# RF08ind.net
KiCad netlist of a schematic drawn in EAGLE
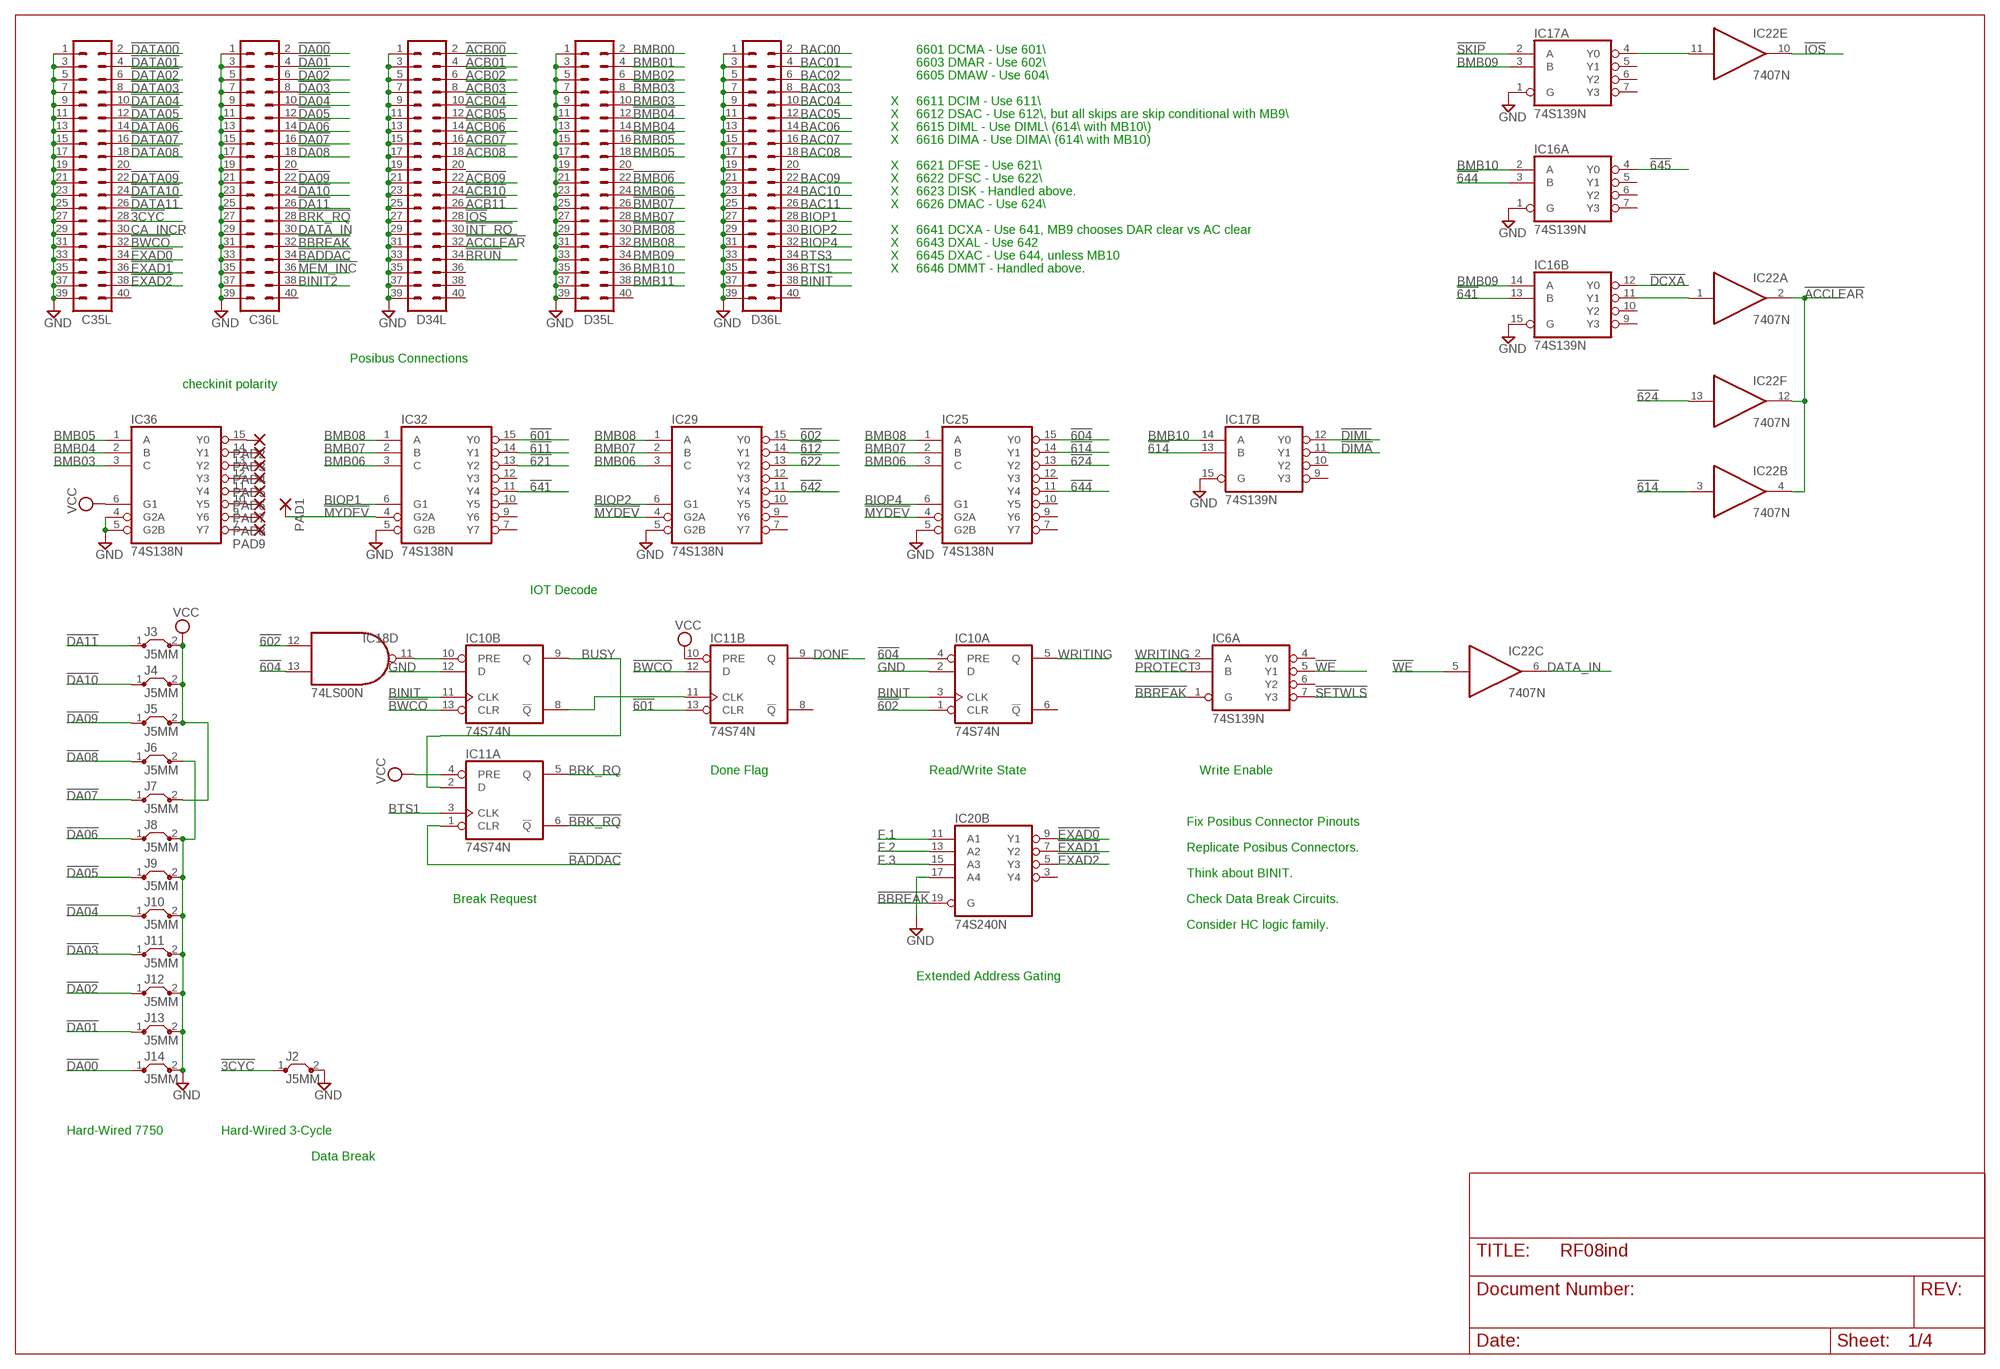
[diagram p0: schematic, sheet 1]
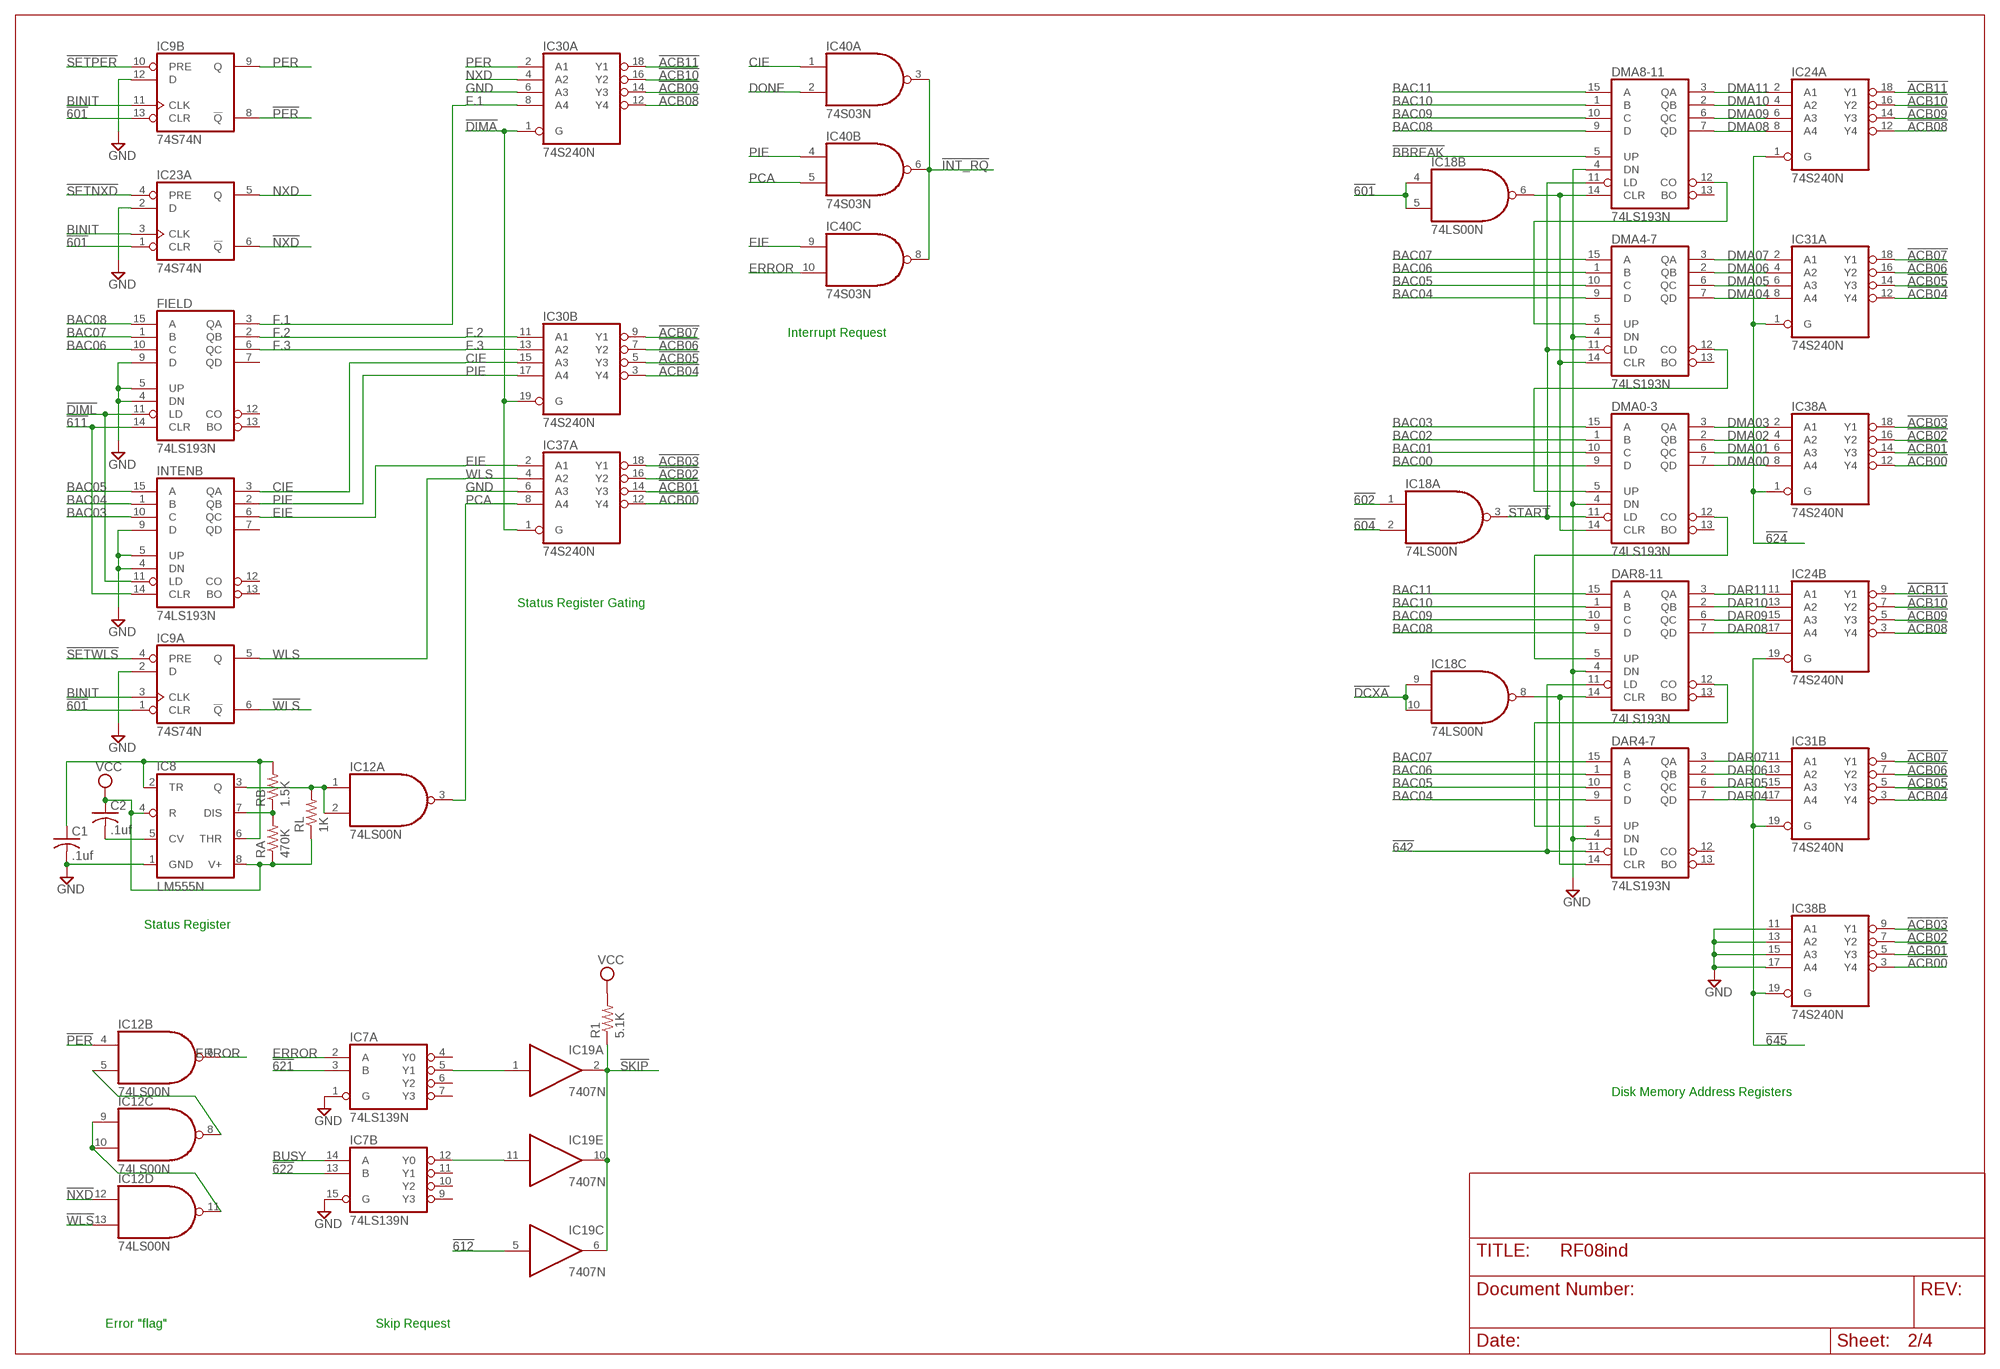
[diagram p1: schematic, sheet 2]
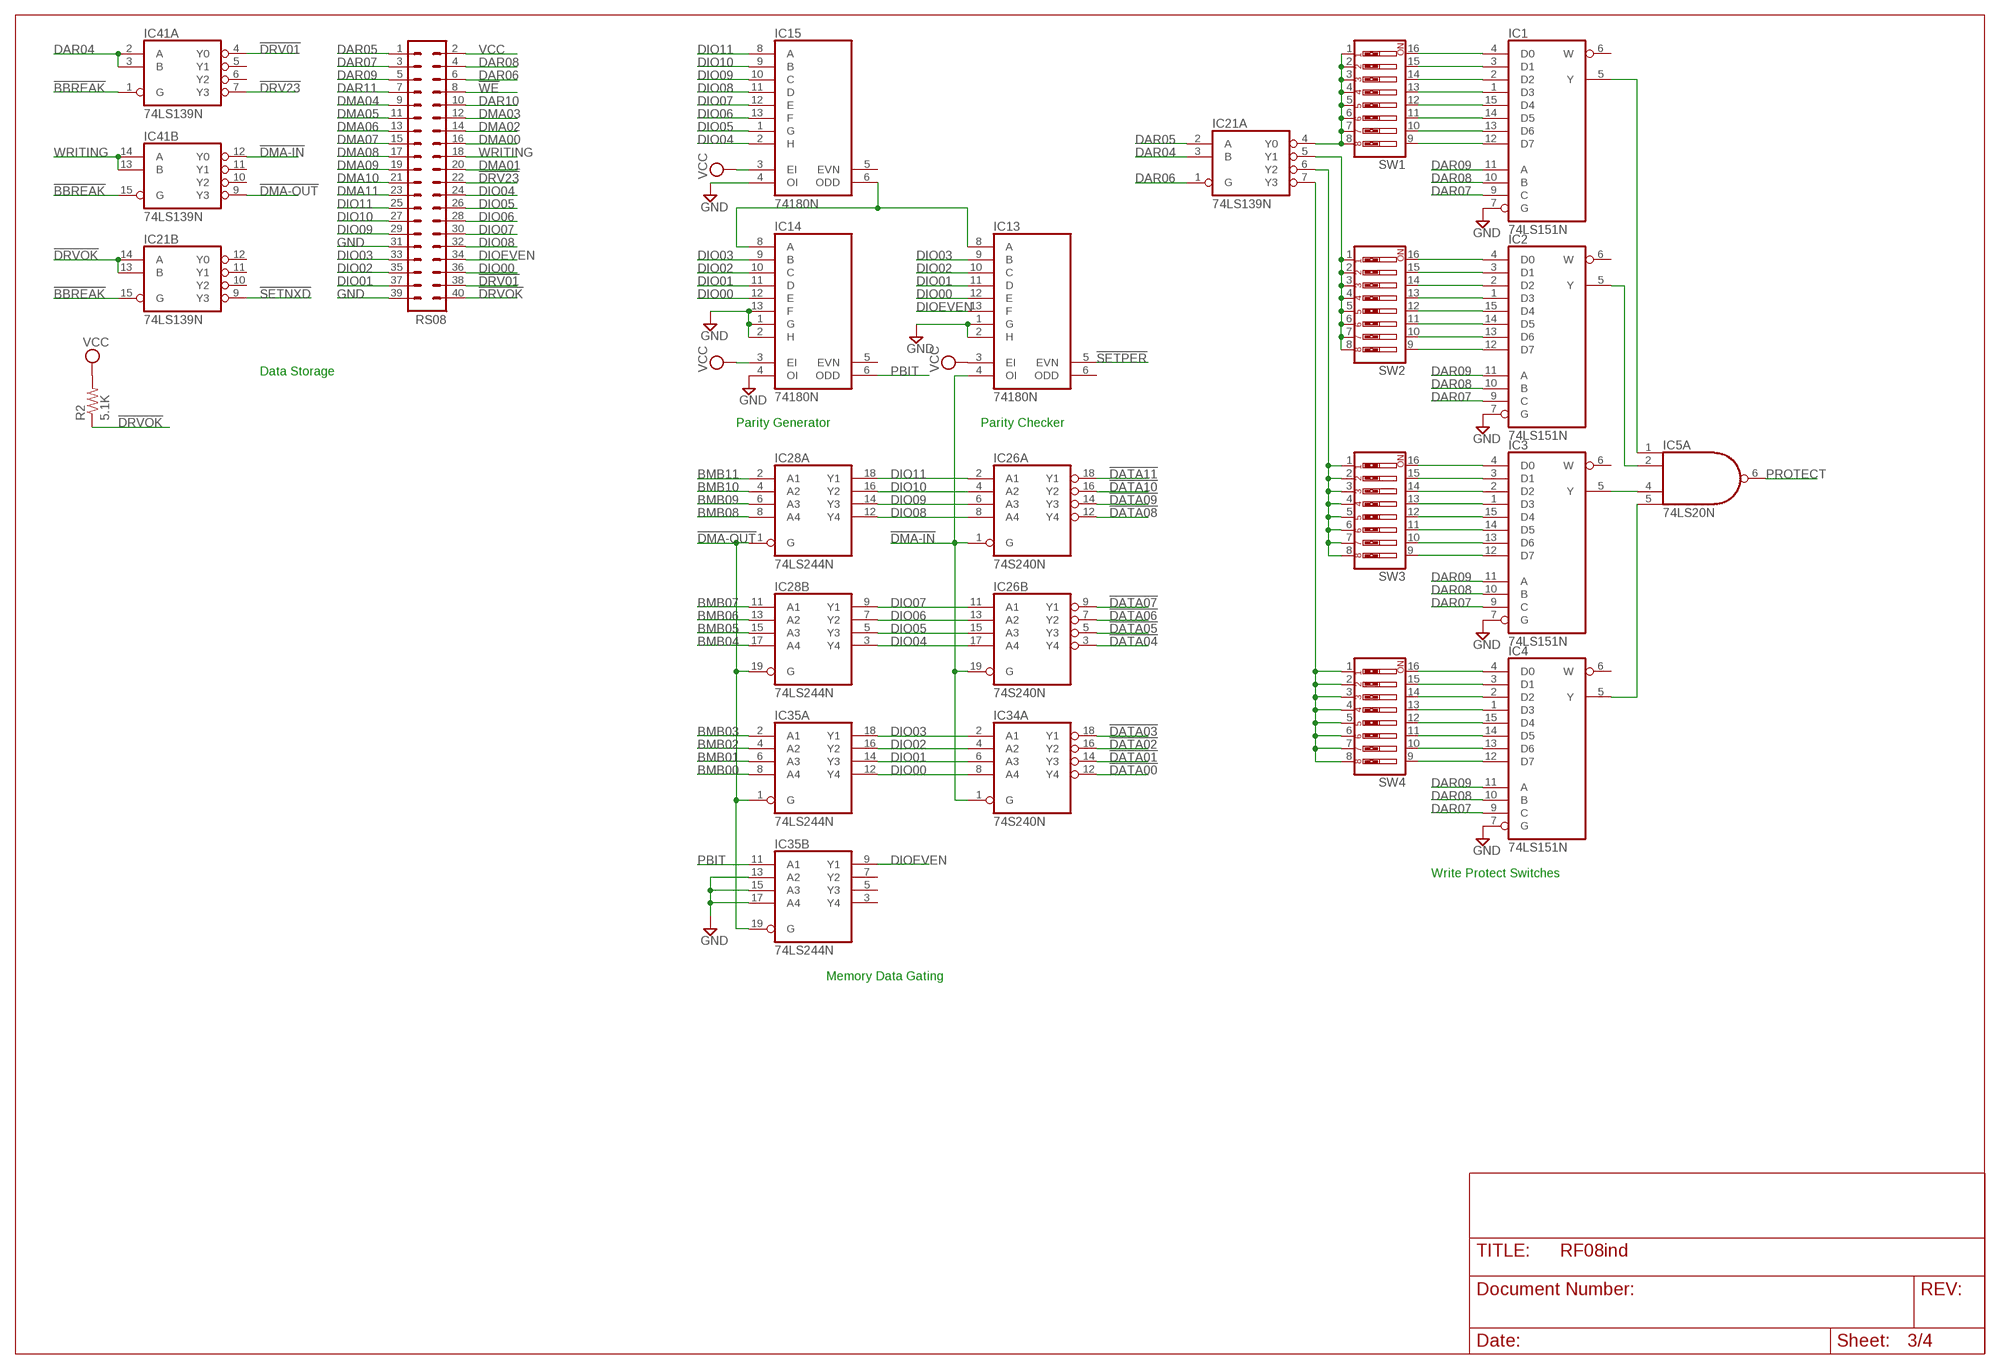
[diagram p2: schematic, sheet 3]
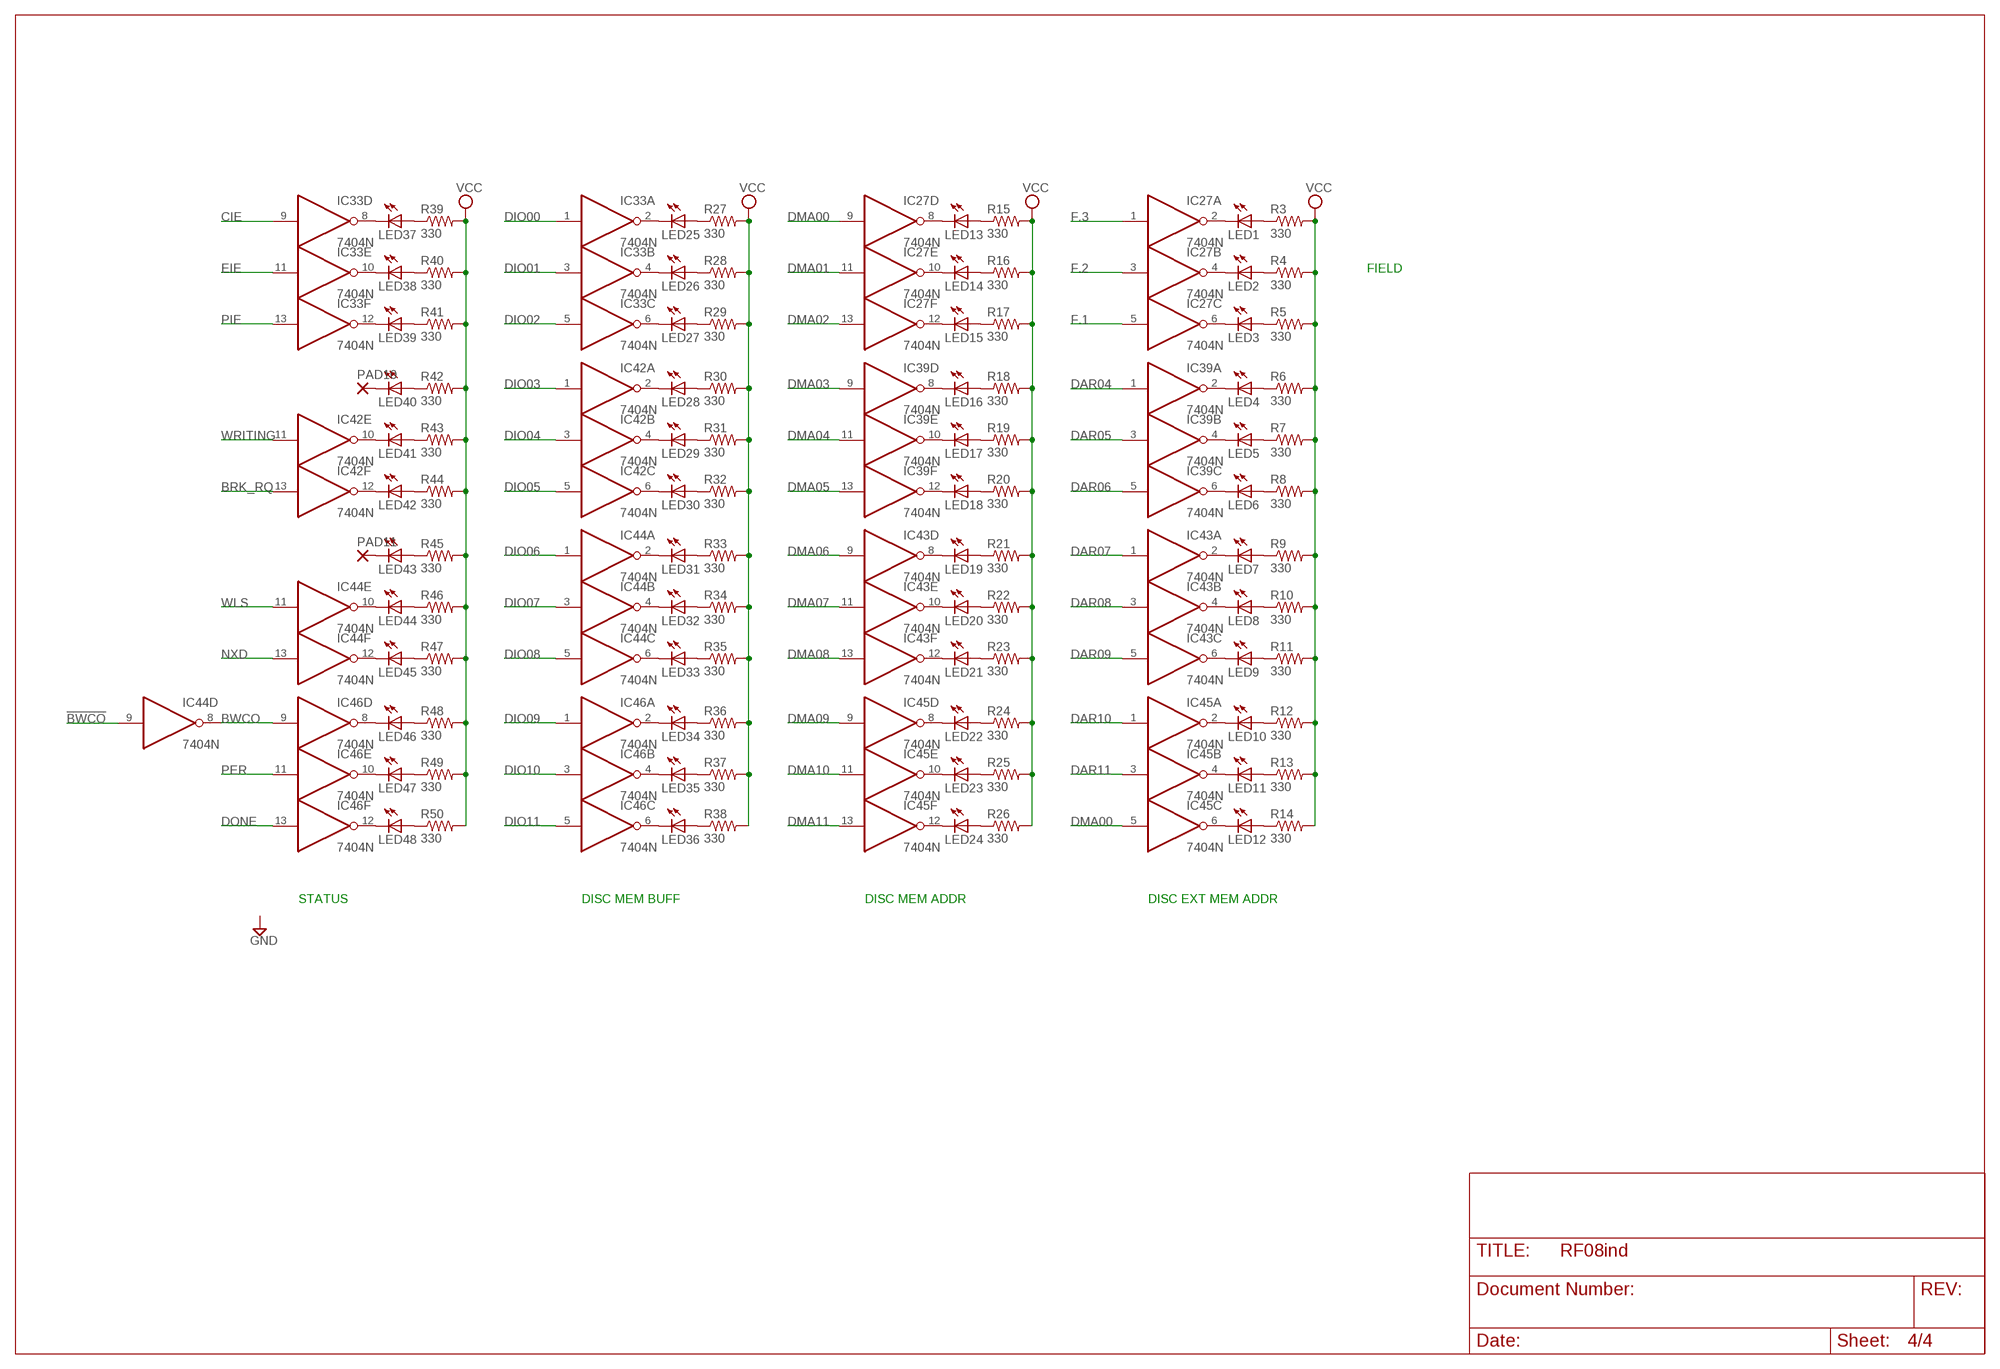
[diagram p3: schematic, sheet 4]

(export (version "E")
  (design (tool "Eeschema 10.0.6"))
  (components
    (comp (ref "IC27")
      (value "7404N")
      (footprint "eagle-import:DIL14")
      (libsource (lib "eagle-import") (part "7404N"))
    )
    (comp (ref "IC33")
      (value "7404N")
      (footprint "eagle-import:DIL14")
      (libsource (lib "eagle-import") (part "7404N"))
    )
    (comp (ref "IC39")
      (value "7404N")
      (footprint "eagle-import:DIL14")
      (libsource (lib "eagle-import") (part "7404N"))
    )
    (comp (ref "IC42")
      (value "7404N")
      (footprint "eagle-import:DIL14")
      (libsource (lib "eagle-import") (part "7404N"))
    )
    (comp (ref "IC43")
      (value "7404N")
      (footprint "eagle-import:DIL14")
      (libsource (lib "eagle-import") (part "7404N"))
    )
    (comp (ref "IC44")
      (value "7404N")
      (footprint "eagle-import:DIL14")
      (libsource (lib "eagle-import") (part "7404N"))
    )
    (comp (ref "IC45")
      (value "7404N")
      (footprint "eagle-import:DIL14")
      (libsource (lib "eagle-import") (part "7404N"))
    )
    (comp (ref "IC46")
      (value "7404N")
      (footprint "eagle-import:DIL14")
      (libsource (lib "eagle-import") (part "7404N"))
    )
    (comp (ref "LED1")
      (value "LED5MM")
      (footprint "eagle-import:LED5MM")
      (libsource (lib "eagle-import") (part "LED5MM"))
    )
    (comp (ref "LED2")
      (value "LED5MM")
      (footprint "eagle-import:LED5MM")
      (libsource (lib "eagle-import") (part "LED5MM"))
    )
    (comp (ref "LED3")
      (value "LED5MM")
      (footprint "eagle-import:LED5MM")
      (libsource (lib "eagle-import") (part "LED5MM"))
    )
    (comp (ref "LED4")
      (value "LED5MM")
      (footprint "eagle-import:LED5MM")
      (libsource (lib "eagle-import") (part "LED5MM"))
    )
    (comp (ref "LED5")
      (value "LED5MM")
      (footprint "eagle-import:LED5MM")
      (libsource (lib "eagle-import") (part "LED5MM"))
    )
    (comp (ref "LED6")
      (value "LED5MM")
      (footprint "eagle-import:LED5MM")
      (libsource (lib "eagle-import") (part "LED5MM"))
    )
    (comp (ref "LED7")
      (value "LED5MM")
      (footprint "eagle-import:LED5MM")
      (libsource (lib "eagle-import") (part "LED5MM"))
    )
    (comp (ref "LED8")
      (value "LED5MM")
      (footprint "eagle-import:LED5MM")
      (libsource (lib "eagle-import") (part "LED5MM"))
    )
    (comp (ref "LED9")
      (value "LED5MM")
      (footprint "eagle-import:LED5MM")
      (libsource (lib "eagle-import") (part "LED5MM"))
    )
    (comp (ref "LED10")
      (value "LED5MM")
      (footprint "eagle-import:LED5MM")
      (libsource (lib "eagle-import") (part "LED5MM"))
    )
    (comp (ref "LED11")
      (value "LED5MM")
      (footprint "eagle-import:LED5MM")
      (libsource (lib "eagle-import") (part "LED5MM"))
    )
    (comp (ref "LED12")
      (value "LED5MM")
      (footprint "eagle-import:LED5MM")
      (libsource (lib "eagle-import") (part "LED5MM"))
    )
    (comp (ref "LED13")
      (value "LED5MM")
      (footprint "eagle-import:LED5MM")
      (libsource (lib "eagle-import") (part "LED5MM"))
    )
    (comp (ref "LED14")
      (value "LED5MM")
      (footprint "eagle-import:LED5MM")
      (libsource (lib "eagle-import") (part "LED5MM"))
    )
    (comp (ref "LED15")
      (value "LED5MM")
      (footprint "eagle-import:LED5MM")
      (libsource (lib "eagle-import") (part "LED5MM"))
    )
    (comp (ref "LED16")
      (value "LED5MM")
      (footprint "eagle-import:LED5MM")
      (libsource (lib "eagle-import") (part "LED5MM"))
    )
    (comp (ref "LED17")
      (value "LED5MM")
      (footprint "eagle-import:LED5MM")
      (libsource (lib "eagle-import") (part "LED5MM"))
    )
    (comp (ref "LED18")
      (value "LED5MM")
      (footprint "eagle-import:LED5MM")
      (libsource (lib "eagle-import") (part "LED5MM"))
    )
    (comp (ref "LED19")
      (value "LED5MM")
      (footprint "eagle-import:LED5MM")
      (libsource (lib "eagle-import") (part "LED5MM"))
    )
    (comp (ref "LED20")
      (value "LED5MM")
      (footprint "eagle-import:LED5MM")
      (libsource (lib "eagle-import") (part "LED5MM"))
    )
    (comp (ref "LED21")
      (value "LED5MM")
      (footprint "eagle-import:LED5MM")
      (libsource (lib "eagle-import") (part "LED5MM"))
    )
    (comp (ref "LED22")
      (value "LED5MM")
      (footprint "eagle-import:LED5MM")
      (libsource (lib "eagle-import") (part "LED5MM"))
    )
    (comp (ref "LED23")
      (value "LED5MM")
      (footprint "eagle-import:LED5MM")
      (libsource (lib "eagle-import") (part "LED5MM"))
    )
    (comp (ref "LED24")
      (value "LED5MM")
      (footprint "eagle-import:LED5MM")
      (libsource (lib "eagle-import") (part "LED5MM"))
    )
    (comp (ref "LED25")
      (value "LED5MM")
      (footprint "eagle-import:LED5MM")
      (libsource (lib "eagle-import") (part "LED5MM"))
    )
    (comp (ref "LED26")
      (value "LED5MM")
      (footprint "eagle-import:LED5MM")
      (libsource (lib "eagle-import") (part "LED5MM"))
    )
    (comp (ref "LED27")
      (value "LED5MM")
      (footprint "eagle-import:LED5MM")
      (libsource (lib "eagle-import") (part "LED5MM"))
    )
    (comp (ref "LED28")
      (value "LED5MM")
      (footprint "eagle-import:LED5MM")
      (libsource (lib "eagle-import") (part "LED5MM"))
    )
    (comp (ref "LED29")
      (value "LED5MM")
      (footprint "eagle-import:LED5MM")
      (libsource (lib "eagle-import") (part "LED5MM"))
    )
    (comp (ref "LED30")
      (value "LED5MM")
      (footprint "eagle-import:LED5MM")
      (libsource (lib "eagle-import") (part "LED5MM"))
    )
    (comp (ref "LED31")
      (value "LED5MM")
      (footprint "eagle-import:LED5MM")
      (libsource (lib "eagle-import") (part "LED5MM"))
    )
    (comp (ref "LED32")
      (value "LED5MM")
      (footprint "eagle-import:LED5MM")
      (libsource (lib "eagle-import") (part "LED5MM"))
    )
    (comp (ref "LED33")
      (value "LED5MM")
      (footprint "eagle-import:LED5MM")
      (libsource (lib "eagle-import") (part "LED5MM"))
    )
    (comp (ref "LED34")
      (value "LED5MM")
      (footprint "eagle-import:LED5MM")
      (libsource (lib "eagle-import") (part "LED5MM"))
    )
    (comp (ref "LED35")
      (value "LED5MM")
      (footprint "eagle-import:LED5MM")
      (libsource (lib "eagle-import") (part "LED5MM"))
    )
    (comp (ref "LED36")
      (value "LED5MM")
      (footprint "eagle-import:LED5MM")
      (libsource (lib "eagle-import") (part "LED5MM"))
    )
    (comp (ref "LED37")
      (value "LED5MM")
      (footprint "eagle-import:LED5MM")
      (libsource (lib "eagle-import") (part "LED5MM"))
    )
    (comp (ref "LED38")
      (value "LED5MM")
      (footprint "eagle-import:LED5MM")
      (libsource (lib "eagle-import") (part "LED5MM"))
    )
    (comp (ref "LED39")
      (value "LED5MM")
      (footprint "eagle-import:LED5MM")
      (libsource (lib "eagle-import") (part "LED5MM"))
    )
    (comp (ref "LED40")
      (value "LED5MM")
      (footprint "eagle-import:LED5MM")
      (libsource (lib "eagle-import") (part "LED5MM"))
    )
    (comp (ref "LED41")
      (value "LED5MM")
      (footprint "eagle-import:LED5MM")
      (libsource (lib "eagle-import") (part "LED5MM"))
    )
    (comp (ref "LED42")
      (value "LED5MM")
      (footprint "eagle-import:LED5MM")
      (libsource (lib "eagle-import") (part "LED5MM"))
    )
    (comp (ref "LED43")
      (value "LED5MM")
      (footprint "eagle-import:LED5MM")
      (libsource (lib "eagle-import") (part "LED5MM"))
    )
    (comp (ref "LED44")
      (value "LED5MM")
      (footprint "eagle-import:LED5MM")
      (libsource (lib "eagle-import") (part "LED5MM"))
    )
    (comp (ref "LED45")
      (value "LED5MM")
      (footprint "eagle-import:LED5MM")
      (libsource (lib "eagle-import") (part "LED5MM"))
    )
    (comp (ref "LED46")
      (value "LED5MM")
      (footprint "eagle-import:LED5MM")
      (libsource (lib "eagle-import") (part "LED5MM"))
    )
    (comp (ref "LED47")
      (value "LED5MM")
      (footprint "eagle-import:LED5MM")
      (libsource (lib "eagle-import") (part "LED5MM"))
    )
    (comp (ref "LED48")
      (value "LED5MM")
      (footprint "eagle-import:LED5MM")
      (libsource (lib "eagle-import") (part "LED5MM"))
    )
    (comp (ref "PAD10")
      (value "1,6/0,8")
      (footprint "eagle-import:1,6_0,8")
      (libsource (lib "eagle-import") (part "1,6/0,8"))
    )
    (comp (ref "PAD11")
      (value "1,6/0,8")
      (footprint "eagle-import:1,6_0,8")
      (libsource (lib "eagle-import") (part "1,6/0,8"))
    )
    (comp (ref "R3")
      (value "330")
      (footprint "eagle-import:0207_10")
      (libsource (lib "eagle-import") (part "R-US_0207/10"))
    )
    (comp (ref "R4")
      (value "330")
      (footprint "eagle-import:0207_10")
      (libsource (lib "eagle-import") (part "R-US_0207/10"))
    )
    (comp (ref "R5")
      (value "330")
      (footprint "eagle-import:0207_10")
      (libsource (lib "eagle-import") (part "R-US_0207/10"))
    )
    (comp (ref "R6")
      (value "330")
      (footprint "eagle-import:0207_10")
      (libsource (lib "eagle-import") (part "R-US_0207/10"))
    )
    (comp (ref "R7")
      (value "330")
      (footprint "eagle-import:0207_10")
      (libsource (lib "eagle-import") (part "R-US_0207/10"))
    )
    (comp (ref "R8")
      (value "330")
      (footprint "eagle-import:0207_10")
      (libsource (lib "eagle-import") (part "R-US_0207/10"))
    )
    (comp (ref "R9")
      (value "330")
      (footprint "eagle-import:0207_10")
      (libsource (lib "eagle-import") (part "R-US_0207/10"))
    )
    (comp (ref "R10")
      (value "330")
      (footprint "eagle-import:0207_10")
      (libsource (lib "eagle-import") (part "R-US_0207/10"))
    )
    (comp (ref "R11")
      (value "330")
      (footprint "eagle-import:0207_10")
      (libsource (lib "eagle-import") (part "R-US_0207/10"))
    )
    (comp (ref "R12")
      (value "330")
      (footprint "eagle-import:0207_10")
      (libsource (lib "eagle-import") (part "R-US_0207/10"))
    )
    (comp (ref "R13")
      (value "330")
      (footprint "eagle-import:0207_10")
      (libsource (lib "eagle-import") (part "R-US_0207/10"))
    )
    (comp (ref "R14")
      (value "330")
      (footprint "eagle-import:0207_10")
      (libsource (lib "eagle-import") (part "R-US_0207/10"))
    )
    (comp (ref "R15")
      (value "330")
      (footprint "eagle-import:0207_10")
      (libsource (lib "eagle-import") (part "R-US_0207/10"))
    )
    (comp (ref "R16")
      (value "330")
      (footprint "eagle-import:0207_10")
      (libsource (lib "eagle-import") (part "R-US_0207/10"))
    )
    (comp (ref "R17")
      (value "330")
      (footprint "eagle-import:0207_10")
      (libsource (lib "eagle-import") (part "R-US_0207/10"))
    )
    (comp (ref "R18")
      (value "330")
      (footprint "eagle-import:0207_10")
      (libsource (lib "eagle-import") (part "R-US_0207/10"))
    )
    (comp (ref "R19")
      (value "330")
      (footprint "eagle-import:0207_10")
      (libsource (lib "eagle-import") (part "R-US_0207/10"))
    )
    (comp (ref "R20")
      (value "330")
      (footprint "eagle-import:0207_10")
      (libsource (lib "eagle-import") (part "R-US_0207/10"))
    )
    (comp (ref "R21")
      (value "330")
      (footprint "eagle-import:0207_10")
      (libsource (lib "eagle-import") (part "R-US_0207/10"))
    )
    (comp (ref "R22")
      (value "330")
      (footprint "eagle-import:0207_10")
      (libsource (lib "eagle-import") (part "R-US_0207/10"))
    )
    (comp (ref "R23")
      (value "330")
      (footprint "eagle-import:0207_10")
      (libsource (lib "eagle-import") (part "R-US_0207/10"))
    )
    (comp (ref "R24")
      (value "330")
      (footprint "eagle-import:0207_10")
      (libsource (lib "eagle-import") (part "R-US_0207/10"))
    )
    (comp (ref "R25")
      (value "330")
      (footprint "eagle-import:0207_10")
      (libsource (lib "eagle-import") (part "R-US_0207/10"))
    )
    (comp (ref "R26")
      (value "330")
      (footprint "eagle-import:0207_10")
      (libsource (lib "eagle-import") (part "R-US_0207/10"))
    )
    (comp (ref "R27")
      (value "330")
      (footprint "eagle-import:0207_10")
      (libsource (lib "eagle-import") (part "R-US_0207/10"))
    )
    (comp (ref "R28")
      (value "330")
      (footprint "eagle-import:0207_10")
      (libsource (lib "eagle-import") (part "R-US_0207/10"))
    )
    (comp (ref "R29")
      (value "330")
      (footprint "eagle-import:0207_10")
      (libsource (lib "eagle-import") (part "R-US_0207/10"))
    )
    (comp (ref "R30")
      (value "330")
      (footprint "eagle-import:0207_10")
      (libsource (lib "eagle-import") (part "R-US_0207/10"))
    )
    (comp (ref "R31")
      (value "330")
      (footprint "eagle-import:0207_10")
      (libsource (lib "eagle-import") (part "R-US_0207/10"))
    )
    (comp (ref "R32")
      (value "330")
      (footprint "eagle-import:0207_10")
      (libsource (lib "eagle-import") (part "R-US_0207/10"))
    )
    (comp (ref "R33")
      (value "330")
      (footprint "eagle-import:0207_10")
      (libsource (lib "eagle-import") (part "R-US_0207/10"))
    )
    (comp (ref "R34")
      (value "330")
      (footprint "eagle-import:0207_10")
      (libsource (lib "eagle-import") (part "R-US_0207/10"))
    )
    (comp (ref "R35")
      (value "330")
      (footprint "eagle-import:0207_10")
      (libsource (lib "eagle-import") (part "R-US_0207/10"))
    )
    (comp (ref "R36")
      (value "330")
      (footprint "eagle-import:0207_10")
      (libsource (lib "eagle-import") (part "R-US_0207/10"))
    )
    (comp (ref "R37")
      (value "330")
      (footprint "eagle-import:0207_10")
      (libsource (lib "eagle-import") (part "R-US_0207/10"))
    )
    (comp (ref "R38")
      (value "330")
      (footprint "eagle-import:0207_10")
      (libsource (lib "eagle-import") (part "R-US_0207/10"))
    )
    (comp (ref "R39")
      (value "330")
      (footprint "eagle-import:0207_10")
      (libsource (lib "eagle-import") (part "R-US_0207/10"))
    )
    (comp (ref "R40")
      (value "330")
      (footprint "eagle-import:0207_10")
      (libsource (lib "eagle-import") (part "R-US_0207/10"))
    )
    (comp (ref "R41")
      (value "330")
      (footprint "eagle-import:0207_10")
      (libsource (lib "eagle-import") (part "R-US_0207/10"))
    )
    (comp (ref "R42")
      (value "330")
      (footprint "eagle-import:0207_10")
      (libsource (lib "eagle-import") (part "R-US_0207/10"))
    )
    (comp (ref "R43")
      (value "330")
      (footprint "eagle-import:0207_10")
      (libsource (lib "eagle-import") (part "R-US_0207/10"))
    )
    (comp (ref "R44")
      (value "330")
      (footprint "eagle-import:0207_10")
      (libsource (lib "eagle-import") (part "R-US_0207/10"))
    )
    (comp (ref "R45")
      (value "330")
      (footprint "eagle-import:0207_10")
      (libsource (lib "eagle-import") (part "R-US_0207/10"))
    )
    (comp (ref "R46")
      (value "330")
      (footprint "eagle-import:0207_10")
      (libsource (lib "eagle-import") (part "R-US_0207/10"))
    )
    (comp (ref "R47")
      (value "330")
      (footprint "eagle-import:0207_10")
      (libsource (lib "eagle-import") (part "R-US_0207/10"))
    )
    (comp (ref "R48")
      (value "330")
      (footprint "eagle-import:0207_10")
      (libsource (lib "eagle-import") (part "R-US_0207/10"))
    )
    (comp (ref "R49")
      (value "330")
      (footprint "eagle-import:0207_10")
      (libsource (lib "eagle-import") (part "R-US_0207/10"))
    )
    (comp (ref "R50")
      (value "330")
      (footprint "eagle-import:0207_10")
      (libsource (lib "eagle-import") (part "R-US_0207/10"))
    )
    (comp (ref "IC1")
      (value "74LS151N")
      (footprint "eagle-import:DIL16")
      (libsource (lib "eagle-import") (part "74151NLS"))
    )
    (comp (ref "IC2")
      (value "74LS151N")
      (footprint "eagle-import:DIL16")
      (libsource (lib "eagle-import") (part "74151NLS"))
    )
    (comp (ref "IC3")
      (value "74LS151N")
      (footprint "eagle-import:DIL16")
      (libsource (lib "eagle-import") (part "74151NLS"))
    )
    (comp (ref "IC4")
      (value "74LS151N")
      (footprint "eagle-import:DIL16")
      (libsource (lib "eagle-import") (part "74151NLS"))
    )
    (comp (ref "IC5")
      (value "74LS20N")
      (footprint "eagle-import:DIL14")
      (libsource (lib "eagle-import") (part "7420NLS"))
    )
    (comp (ref "IC13")
      (value "74180N")
      (footprint "eagle-import:DIL14")
      (libsource (lib "eagle-import") (part "74180N"))
    )
    (comp (ref "IC14")
      (value "74180N")
      (footprint "eagle-import:DIL14")
      (libsource (lib "eagle-import") (part "74180N"))
    )
    (comp (ref "IC15")
      (value "74180N")
      (footprint "eagle-import:DIL14")
      (libsource (lib "eagle-import") (part "74180N"))
    )
    (comp (ref "IC21")
      (value "74LS139N")
      (footprint "eagle-import:DIL16")
      (libsource (lib "eagle-import") (part "74139NLS"))
    )
    (comp (ref "IC26")
      (value "74S240N")
      (footprint "eagle-import:DIL20")
      (libsource (lib "eagle-import") (part "74240NS"))
    )
    (comp (ref "IC28")
      (value "74LS244N")
      (footprint "eagle-import:DIL20")
      (libsource (lib "eagle-import") (part "74244NLS"))
    )
    (comp (ref "IC34")
      (value "74S240N")
      (footprint "eagle-import:DIL20")
      (libsource (lib "eagle-import") (part "74240NS"))
    )
    (comp (ref "IC35")
      (value "74LS244N")
      (footprint "eagle-import:DIL20")
      (libsource (lib "eagle-import") (part "74244NLS"))
    )
    (comp (ref "IC41")
      (value "74LS139N")
      (footprint "eagle-import:DIL16")
      (libsource (lib "eagle-import") (part "74139NLS"))
    )
    (comp (ref "R2")
      (value "5.1K")
      (footprint "eagle-import:0207_10")
      (libsource (lib "eagle-import") (part "R-US_0207/10"))
    )
    (comp (ref "RS08")
      (value "MA20-2")
      (footprint "eagle-import:MA20-2")
      (libsource (lib "eagle-import") (part "MA20-2"))
    )
    (comp (ref "SW1")
      (value "SW_DIP-8")
      (footprint "eagle-import:EDG-08")
      (libsource (lib "eagle-import") (part "SW_DIP-8"))
    )
    (comp (ref "SW2")
      (value "SW_DIP-8")
      (footprint "eagle-import:EDG-08")
      (libsource (lib "eagle-import") (part "SW_DIP-8"))
    )
    (comp (ref "SW3")
      (value "SW_DIP-8")
      (footprint "eagle-import:EDG-08")
      (libsource (lib "eagle-import") (part "SW_DIP-8"))
    )
    (comp (ref "SW4")
      (value "SW_DIP-8")
      (footprint "eagle-import:EDG-08")
      (libsource (lib "eagle-import") (part "SW_DIP-8"))
    )
    (comp (ref "C35L")
      (value "MA20-2")
      (footprint "eagle-import:MA20-2")
      (libsource (lib "eagle-import") (part "MA20-2"))
    )
    (comp (ref "C36L")
      (value "MA20-2")
      (footprint "eagle-import:MA20-2")
      (libsource (lib "eagle-import") (part "MA20-2"))
    )
    (comp (ref "D34L")
      (value "MA20-2")
      (footprint "eagle-import:MA20-2")
      (libsource (lib "eagle-import") (part "MA20-2"))
    )
    (comp (ref "D35L")
      (value "MA20-2")
      (footprint "eagle-import:MA20-2")
      (libsource (lib "eagle-import") (part "MA20-2"))
    )
    (comp (ref "D36L")
      (value "MA20-2")
      (footprint "eagle-import:MA20-2")
      (libsource (lib "eagle-import") (part "MA20-2"))
    )
    (comp (ref "IC6")
      (value "74S139N")
      (footprint "eagle-import:DIL16")
      (libsource (lib "eagle-import") (part "74139NS"))
    )
    (comp (ref "IC10")
      (value "74S74N")
      (footprint "eagle-import:DIL14")
      (libsource (lib "eagle-import") (part "7474NS"))
    )
    (comp (ref "IC11")
      (value "74S74N")
      (footprint "eagle-import:DIL14")
      (libsource (lib "eagle-import") (part "7474NS"))
    )
    (comp (ref "IC16")
      (value "74S139N")
      (footprint "eagle-import:DIL16")
      (libsource (lib "eagle-import") (part "74139NS"))
    )
    (comp (ref "IC17")
      (value "74S139N")
      (footprint "eagle-import:DIL16")
      (libsource (lib "eagle-import") (part "74139NS"))
    )
    (comp (ref "IC18")
      (value "74LS00N")
      (footprint "eagle-import:DIL14")
      (libsource (lib "eagle-import") (part "7400NLS"))
    )
    (comp (ref "IC20")
      (value "74S240N")
      (footprint "eagle-import:DIL20")
      (libsource (lib "eagle-import") (part "74240NS"))
    )
    (comp (ref "IC22")
      (value "7407N")
      (footprint "eagle-import:DIL14")
      (libsource (lib "eagle-import") (part "7407N"))
    )
    (comp (ref "IC25")
      (value "74S138N")
      (footprint "eagle-import:DIL16")
      (libsource (lib "eagle-import") (part "74138NS"))
    )
    (comp (ref "IC29")
      (value "74S138N")
      (footprint "eagle-import:DIL16")
      (libsource (lib "eagle-import") (part "74138NS"))
    )
    (comp (ref "IC32")
      (value "74S138N")
      (footprint "eagle-import:DIL16")
      (libsource (lib "eagle-import") (part "74138NS"))
    )
    (comp (ref "IC36")
      (value "74S138N")
      (footprint "eagle-import:DIL16")
      (libsource (lib "eagle-import") (part "74138NS"))
    )
    (comp (ref "J2")
      (value "J5MM")
      (footprint "eagle-import:05")
      (libsource (lib "eagle-import") (part "J5MM"))
    )
    (comp (ref "J3")
      (value "J5MM")
      (footprint "eagle-import:05")
      (libsource (lib "eagle-import") (part "J5MM"))
    )
    (comp (ref "J4")
      (value "J5MM")
      (footprint "eagle-import:05")
      (libsource (lib "eagle-import") (part "J5MM"))
    )
    (comp (ref "J5")
      (value "J5MM")
      (footprint "eagle-import:05")
      (libsource (lib "eagle-import") (part "J5MM"))
    )
    (comp (ref "J6")
      (value "J5MM")
      (footprint "eagle-import:05")
      (libsource (lib "eagle-import") (part "J5MM"))
    )
    (comp (ref "J7")
      (value "J5MM")
      (footprint "eagle-import:05")
      (libsource (lib "eagle-import") (part "J5MM"))
    )
    (comp (ref "J8")
      (value "J5MM")
      (footprint "eagle-import:05")
      (libsource (lib "eagle-import") (part "J5MM"))
    )
    (comp (ref "J9")
      (value "J5MM")
      (footprint "eagle-import:05")
      (libsource (lib "eagle-import") (part "J5MM"))
    )
    (comp (ref "J10")
      (value "J5MM")
      (footprint "eagle-import:05")
      (libsource (lib "eagle-import") (part "J5MM"))
    )
    (comp (ref "J11")
      (value "J5MM")
      (footprint "eagle-import:05")
      (libsource (lib "eagle-import") (part "J5MM"))
    )
    (comp (ref "J12")
      (value "J5MM")
      (footprint "eagle-import:05")
      (libsource (lib "eagle-import") (part "J5MM"))
    )
    (comp (ref "J13")
      (value "J5MM")
      (footprint "eagle-import:05")
      (libsource (lib "eagle-import") (part "J5MM"))
    )
    (comp (ref "J14")
      (value "J5MM")
      (footprint "eagle-import:05")
      (libsource (lib "eagle-import") (part "J5MM"))
    )
    (comp (ref "PAD1")
      (value "1,6/0,8")
      (footprint "eagle-import:1,6_0,8")
      (libsource (lib "eagle-import") (part "1,6/0,8"))
    )
    (comp (ref "PAD2")
      (value "1,6/0,8")
      (footprint "eagle-import:1,6_0,8")
      (libsource (lib "eagle-import") (part "1,6/0,8"))
    )
    (comp (ref "PAD3")
      (value "1,6/0,8")
      (footprint "eagle-import:1,6_0,8")
      (libsource (lib "eagle-import") (part "1,6/0,8"))
    )
    (comp (ref "PAD4")
      (value "1,6/0,8")
      (footprint "eagle-import:1,6_0,8")
      (libsource (lib "eagle-import") (part "1,6/0,8"))
    )
    (comp (ref "PAD5")
      (value "1,6/0,8")
      (footprint "eagle-import:1,6_0,8")
      (libsource (lib "eagle-import") (part "1,6/0,8"))
    )
    (comp (ref "PAD6")
      (value "1,6/0,8")
      (footprint "eagle-import:1,6_0,8")
      (libsource (lib "eagle-import") (part "1,6/0,8"))
    )
    (comp (ref "PAD7")
      (value "1,6/0,8")
      (footprint "eagle-import:1,6_0,8")
      (libsource (lib "eagle-import") (part "1,6/0,8"))
    )
    (comp (ref "PAD8")
      (value "1,6/0,8")
      (footprint "eagle-import:1,6_0,8")
      (libsource (lib "eagle-import") (part "1,6/0,8"))
    )
    (comp (ref "PAD9")
      (value "1,6/0,8")
      (footprint "eagle-import:1,6_0,8")
      (libsource (lib "eagle-import") (part "1,6/0,8"))
    )
    (comp (ref "C1")
      (value ".1uf")
      (footprint "eagle-import:C050-025X075")
      (libsource (lib "eagle-import") (part "C-US050-025X075"))
    )
    (comp (ref "C2")
      (value ".1uf")
      (footprint "eagle-import:C050-025X075")
      (libsource (lib "eagle-import") (part "C-US050-025X075"))
    )
    (comp (ref "DAR4-7")
      (value "74LS193N")
      (footprint "eagle-import:DIL16")
      (libsource (lib "eagle-import") (part "74192NLS"))
    )
    (comp (ref "DAR8-11")
      (value "74LS193N")
      (footprint "eagle-import:DIL16")
      (libsource (lib "eagle-import") (part "74192NLS"))
    )
    (comp (ref "DMA0-3")
      (value "74LS193N")
      (footprint "eagle-import:DIL16")
      (libsource (lib "eagle-import") (part "74192NLS"))
    )
    (comp (ref "DMA4-7")
      (value "74LS193N")
      (footprint "eagle-import:DIL16")
      (libsource (lib "eagle-import") (part "74192NLS"))
    )
    (comp (ref "DMA8-11")
      (value "74LS193N")
      (footprint "eagle-import:DIL16")
      (libsource (lib "eagle-import") (part "74192NLS"))
    )
    (comp (ref "FIELD")
      (value "74LS193N")
      (footprint "eagle-import:DIL16")
      (libsource (lib "eagle-import") (part "74192NLS"))
    )
    (comp (ref "IC7")
      (value "74LS139N")
      (footprint "eagle-import:DIL16")
      (libsource (lib "eagle-import") (part "74139NLS"))
    )
    (comp (ref "IC8")
      (value "LM555N")
      (footprint "eagle-import:DIL08")
      (libsource (lib "eagle-import") (part "555NLM"))
    )
    (comp (ref "IC9")
      (value "74S74N")
      (footprint "eagle-import:DIL14")
      (libsource (lib "eagle-import") (part "7474NS"))
    )
    (comp (ref "IC12")
      (value "74LS00N")
      (footprint "eagle-import:DIL14")
      (libsource (lib "eagle-import") (part "7400NLS"))
    )
    (comp (ref "IC19")
      (value "7407N")
      (footprint "eagle-import:DIL14")
      (libsource (lib "eagle-import") (part "7407N"))
    )
    (comp (ref "IC23")
      (value "74S74N")
      (footprint "eagle-import:DIL14")
      (libsource (lib "eagle-import") (part "7474NS"))
    )
    (comp (ref "IC24")
      (value "74S240N")
      (footprint "eagle-import:DIL20")
      (libsource (lib "eagle-import") (part "74240NS"))
    )
    (comp (ref "IC30")
      (value "74S240N")
      (footprint "eagle-import:DIL20")
      (libsource (lib "eagle-import") (part "74240NS"))
    )
    (comp (ref "IC31")
      (value "74S240N")
      (footprint "eagle-import:DIL20")
      (libsource (lib "eagle-import") (part "74240NS"))
    )
    (comp (ref "IC37")
      (value "74S240N")
      (footprint "eagle-import:DIL20")
      (libsource (lib "eagle-import") (part "74240NS"))
    )
    (comp (ref "IC38")
      (value "74S240N")
      (footprint "eagle-import:DIL20")
      (libsource (lib "eagle-import") (part "74240NS"))
    )
    (comp (ref "IC40")
      (value "74S03N")
      (footprint "eagle-import:DIL14")
      (libsource (lib "eagle-import") (part "7403NS"))
    )
    (comp (ref "INTENB")
      (value "74LS193N")
      (footprint "eagle-import:DIL16")
      (libsource (lib "eagle-import") (part "74192NLS"))
    )
    (comp (ref "R1")
      (value "5.1K")
      (footprint "eagle-import:0207_10")
      (libsource (lib "eagle-import") (part "R-US_0207/10"))
    )
    (comp (ref "RA")
      (value "470K")
      (footprint "eagle-import:0207_10")
      (libsource (lib "eagle-import") (part "R-US_0207/10"))
    )
    (comp (ref "RB")
      (value "1.5K")
      (footprint "eagle-import:0207_10")
      (libsource (lib "eagle-import") (part "R-US_0207/10"))
    )
    (comp (ref "RL")
      (value "1K")
      (footprint "eagle-import:0207_10")
      (libsource (lib "eagle-import") (part "R-US_0207/10"))
    )
  )
  (nets
    (net (code "1") (name "BAC00") (class "Default")
      (node (ref "D36L") (pin "2") (pinfunction "2_2") (pintype "passive"))
      (node (ref "DMA0-3") (pin "9") (pinfunction "D_9") (pintype "input"))
    )
    (net (code "2") (name "BAC01") (class "Default")
      (node (ref "D36L") (pin "4") (pinfunction "4_4") (pintype "passive"))
      (node (ref "DMA0-3") (pin "10") (pinfunction "C_10") (pintype "input"))
    )
    (net (code "3") (name "BAC02") (class "Default")
      (node (ref "D36L") (pin "6") (pinfunction "6_6") (pintype "passive"))
      (node (ref "DMA0-3") (pin "1") (pinfunction "B_1") (pintype "input"))
    )
    (net (code "4") (name "BAC03") (class "Default")
      (node (ref "D36L") (pin "8") (pinfunction "8_8") (pintype "passive"))
      (node (ref "DMA0-3") (pin "15") (pinfunction "A_15") (pintype "input"))
      (node (ref "INTENB") (pin "10") (pinfunction "C_10") (pintype "input"))
    )
    (net (code "5") (name "BAC04") (class "Default")
      (node (ref "D36L") (pin "10") (pinfunction "10_10") (pintype "passive"))
      (node (ref "DAR4-7") (pin "9") (pinfunction "D_9") (pintype "input"))
      (node (ref "DMA4-7") (pin "9") (pinfunction "D_9") (pintype "input"))
      (node (ref "INTENB") (pin "1") (pinfunction "B_1") (pintype "input"))
    )
    (net (code "6") (name "BAC05") (class "Default")
      (node (ref "D36L") (pin "12") (pinfunction "12_12") (pintype "passive"))
      (node (ref "DAR4-7") (pin "10") (pinfunction "C_10") (pintype "input"))
      (node (ref "DMA4-7") (pin "10") (pinfunction "C_10") (pintype "input"))
      (node (ref "INTENB") (pin "15") (pinfunction "A_15") (pintype "input"))
    )
    (net (code "7") (name "BAC06") (class "Default")
      (node (ref "D36L") (pin "14") (pinfunction "14_14") (pintype "passive"))
      (node (ref "DAR4-7") (pin "1") (pinfunction "B_1") (pintype "input"))
      (node (ref "DMA4-7") (pin "1") (pinfunction "B_1") (pintype "input"))
      (node (ref "FIELD") (pin "10") (pinfunction "C_10") (pintype "input"))
    )
    (net (code "8") (name "BAC07") (class "Default")
      (node (ref "D36L") (pin "16") (pinfunction "16_16") (pintype "passive"))
      (node (ref "DAR4-7") (pin "15") (pinfunction "A_15") (pintype "input"))
      (node (ref "DMA4-7") (pin "15") (pinfunction "A_15") (pintype "input"))
      (node (ref "FIELD") (pin "1") (pinfunction "B_1") (pintype "input"))
    )
    (net (code "9") (name "BAC08") (class "Default")
      (node (ref "D36L") (pin "18") (pinfunction "18_18") (pintype "passive"))
      (node (ref "DAR8-11") (pin "9") (pinfunction "D_9") (pintype "input"))
      (node (ref "DMA8-11") (pin "9") (pinfunction "D_9") (pintype "input"))
      (node (ref "FIELD") (pin "15") (pinfunction "A_15") (pintype "input"))
    )
    (net (code "10") (name "BAC09") (class "Default")
      (node (ref "D36L") (pin "22") (pinfunction "22_22") (pintype "passive"))
      (node (ref "DAR8-11") (pin "10") (pinfunction "C_10") (pintype "input"))
      (node (ref "DMA8-11") (pin "10") (pinfunction "C_10") (pintype "input"))
    )
    (net (code "11") (name "BAC10") (class "Default")
      (node (ref "D36L") (pin "24") (pinfunction "24_24") (pintype "passive"))
      (node (ref "DAR8-11") (pin "1") (pinfunction "B_1") (pintype "input"))
      (node (ref "DMA8-11") (pin "1") (pinfunction "B_1") (pintype "input"))
    )
    (net (code "12") (name "BAC11") (class "Default")
      (node (ref "D36L") (pin "26") (pinfunction "26_26") (pintype "passive"))
      (node (ref "DAR8-11") (pin "15") (pinfunction "A_15") (pintype "input"))
      (node (ref "DMA8-11") (pin "15") (pinfunction "A_15") (pintype "input"))
    )
    (net (code "13") (name "BINIT") (class "Default")
      (node (ref "D36L") (pin "38") (pinfunction "38_38") (pintype "passive"))
      (node (ref "IC10") (pin "11") (pinfunction "CLK_11") (pintype "input"))
      (node (ref "IC10") (pin "3") (pinfunction "CLK_3") (pintype "input"))
      (node (ref "IC23") (pin "3") (pinfunction "CLK_3") (pintype "input"))
      (node (ref "IC9") (pin "11") (pinfunction "CLK_11") (pintype "input"))
      (node (ref "IC9") (pin "3") (pinfunction "CLK_3") (pintype "input"))
    )
    (net (code "14") (name "BINIT2") (class "Default")
      (node (ref "C36L") (pin "38") (pinfunction "38_38") (pintype "passive"))
    )
    (net (code "15") (name "BIOP1") (class "Default")
      (node (ref "D36L") (pin "28") (pinfunction "28_28") (pintype "passive"))
      (node (ref "IC32") (pin "6") (pinfunction "G1_6") (pintype "input"))
    )
    (net (code "16") (name "BIOP2") (class "Default")
      (node (ref "D36L") (pin "30") (pinfunction "30_30") (pintype "passive"))
      (node (ref "IC29") (pin "6") (pinfunction "G1_6") (pintype "input"))
    )
    (net (code "17") (name "BIOP4") (class "Default")
      (node (ref "D36L") (pin "32") (pinfunction "32_32") (pintype "passive"))
      (node (ref "IC25") (pin "6") (pinfunction "G1_6") (pintype "input"))
    )
    (net (code "18") (name "BMB00") (class "Default")
      (node (ref "D35L") (pin "2") (pinfunction "2_2") (pintype "passive"))
      (node (ref "IC35") (pin "8") (pinfunction "A4_8") (pintype "input"))
    )
    (net (code "19") (name "BMB01") (class "Default")
      (node (ref "D35L") (pin "4") (pinfunction "4_4") (pintype "passive"))
      (node (ref "IC35") (pin "6") (pinfunction "A3_6") (pintype "input"))
    )
    (net (code "20") (name "BMB02") (class "Default")
      (node (ref "D35L") (pin "6") (pinfunction "6_6") (pintype "passive"))
      (node (ref "IC35") (pin "4") (pinfunction "A2_4") (pintype "input"))
    )
    (net (code "21") (name "BMB03") (class "Default")
      (node (ref "D35L") (pin "10") (pinfunction "10_10") (pintype "passive"))
      (node (ref "IC35") (pin "2") (pinfunction "A1_2") (pintype "input"))
      (node (ref "IC36") (pin "3") (pinfunction "C_3") (pintype "input"))
    )
    (net (code "22") (name "BMB04") (class "Default")
      (node (ref "D35L") (pin "14") (pinfunction "14_14") (pintype "passive"))
      (node (ref "IC28") (pin "17") (pinfunction "A4_17") (pintype "input"))
      (node (ref "IC36") (pin "2") (pinfunction "B_2") (pintype "input"))
    )
    (net (code "23") (name "BMB05") (class "Default")
      (node (ref "D35L") (pin "18") (pinfunction "18_18") (pintype "passive"))
      (node (ref "IC28") (pin "15") (pinfunction "A3_15") (pintype "input"))
      (node (ref "IC36") (pin "1") (pinfunction "A_1") (pintype "input"))
    )
    (net (code "24") (name "BMB06") (class "Default")
      (node (ref "D35L") (pin "24") (pinfunction "24_24") (pintype "passive"))
      (node (ref "IC25") (pin "3") (pinfunction "C_3") (pintype "input"))
      (node (ref "IC28") (pin "13") (pinfunction "A2_13") (pintype "input"))
      (node (ref "IC29") (pin "3") (pinfunction "C_3") (pintype "input"))
      (node (ref "IC32") (pin "3") (pinfunction "C_3") (pintype "input"))
    )
    (net (code "25") (name "BMB07") (class "Default")
      (node (ref "D35L") (pin "28") (pinfunction "28_28") (pintype "passive"))
      (node (ref "IC25") (pin "2") (pinfunction "B_2") (pintype "input"))
      (node (ref "IC28") (pin "11") (pinfunction "A1_11") (pintype "input"))
      (node (ref "IC29") (pin "2") (pinfunction "B_2") (pintype "input"))
      (node (ref "IC32") (pin "2") (pinfunction "B_2") (pintype "input"))
    )
    (net (code "26") (name "BMB08") (class "Default")
      (node (ref "D35L") (pin "32") (pinfunction "32_32") (pintype "passive"))
      (node (ref "IC25") (pin "1") (pinfunction "A_1") (pintype "input"))
      (node (ref "IC28") (pin "8") (pinfunction "A4_8") (pintype "input"))
      (node (ref "IC29") (pin "1") (pinfunction "A_1") (pintype "input"))
      (node (ref "IC32") (pin "1") (pinfunction "A_1") (pintype "input"))
    )
    (net (code "27") (name "BMB09") (class "Default")
      (node (ref "D35L") (pin "34") (pinfunction "34_34") (pintype "passive"))
      (node (ref "IC16") (pin "14") (pinfunction "A_14") (pintype "input"))
      (node (ref "IC17") (pin "3") (pinfunction "B_3") (pintype "input"))
      (node (ref "IC28") (pin "6") (pinfunction "A3_6") (pintype "input"))
    )
    (net (code "28") (name "BMB10") (class "Default")
      (node (ref "D35L") (pin "36") (pinfunction "36_36") (pintype "passive"))
      (node (ref "IC16") (pin "2") (pinfunction "A_2") (pintype "input"))
      (node (ref "IC17") (pin "14") (pinfunction "A_14") (pintype "input"))
      (node (ref "IC28") (pin "4") (pinfunction "A2_4") (pintype "input"))
    )
    (net (code "29") (name "BMB11") (class "Default")
      (node (ref "D35L") (pin "38") (pinfunction "38_38") (pintype "passive"))
      (node (ref "IC28") (pin "2") (pinfunction "A1_2") (pintype "input"))
    )
    (net (code "30") (name "BRK_RQ") (class "Default")
      (node (ref "IC11") (pin "5") (pinfunction "Q_5") (pintype "output"))
      (node (ref "IC42") (pin "13") (pinfunction "I_13") (pintype "input"))
    )
    (net (code "31") (name "BTS1") (class "Default")
      (node (ref "D36L") (pin "36") (pinfunction "36_36") (pintype "passive"))
      (node (ref "IC11") (pin "3") (pinfunction "CLK_3") (pintype "input"))
    )
    (net (code "32") (name "BTS3") (class "Default")
      (node (ref "D36L") (pin "34") (pinfunction "34_34") (pintype "passive"))
    )
    (net (code "33") (name "BUSY") (class "Default")
      (node (ref "IC10") (pin "9") (pinfunction "Q_9") (pintype "output"))
      (node (ref "IC11") (pin "2") (pinfunction "D_2") (pintype "input"))
      (node (ref "IC7") (pin "14") (pinfunction "A_14") (pintype "input"))
    )
    (net (code "34") (name "BWCO") (class "Default")
      (node (ref "IC44") (pin "8") (pinfunction "O_8") (pintype "output"))
      (node (ref "IC46") (pin "9") (pinfunction "I_9") (pintype "input"))
    )
    (net (code "35") (name "CA_INCR") (class "Default")
      (node (ref "C35L") (pin "30") (pinfunction "30_30") (pintype "passive"))
    )
    (net (code "36") (name "CIE") (class "Default")
      (node (ref "IC30") (pin "15") (pinfunction "A3_15") (pintype "input"))
      (node (ref "IC33") (pin "9") (pinfunction "I_9") (pintype "input"))
      (node (ref "IC40") (pin "1") (pinfunction "I0_1") (pintype "input"))
      (node (ref "INTENB") (pin "3") (pinfunction "QA_3") (pintype "output"))
    )
    (net (code "37") (name "DAR04") (class "Default")
      (node (ref "DAR4-7") (pin "7") (pinfunction "QD_7") (pintype "output"))
      (node (ref "IC21") (pin "3") (pinfunction "B_3") (pintype "input"))
      (node (ref "IC31") (pin "17") (pinfunction "A4_17") (pintype "input"))
      (node (ref "IC39") (pin "1") (pinfunction "I_1") (pintype "input"))
      (node (ref "IC41") (pin "2") (pinfunction "A_2") (pintype "input"))
      (node (ref "IC41") (pin "3") (pinfunction "B_3") (pintype "input"))
    )
    (net (code "38") (name "DAR05") (class "Default")
      (node (ref "DAR4-7") (pin "6") (pinfunction "QC_6") (pintype "output"))
      (node (ref "IC21") (pin "2") (pinfunction "A_2") (pintype "input"))
      (node (ref "IC31") (pin "15") (pinfunction "A3_15") (pintype "input"))
      (node (ref "IC39") (pin "3") (pinfunction "I_3") (pintype "input"))
      (node (ref "RS08") (pin "1") (pinfunction "1_1") (pintype "passive"))
    )
    (net (code "39") (name "DAR06") (class "Default")
      (node (ref "DAR4-7") (pin "2") (pinfunction "QB_2") (pintype "output"))
      (node (ref "IC21") (pin "1") (pinfunction "G_1") (pintype "input"))
      (node (ref "IC31") (pin "13") (pinfunction "A2_13") (pintype "input"))
      (node (ref "IC39") (pin "5") (pinfunction "I_5") (pintype "input"))
      (node (ref "RS08") (pin "6") (pinfunction "6_6") (pintype "passive"))
    )
    (net (code "40") (name "DAR07") (class "Default")
      (node (ref "DAR4-7") (pin "3") (pinfunction "QA_3") (pintype "output"))
      (node (ref "IC1") (pin "9") (pinfunction "C_9") (pintype "input"))
      (node (ref "IC2") (pin "9") (pinfunction "C_9") (pintype "input"))
      (node (ref "IC3") (pin "9") (pinfunction "C_9") (pintype "input"))
      (node (ref "IC31") (pin "11") (pinfunction "A1_11") (pintype "input"))
      (node (ref "IC4") (pin "9") (pinfunction "C_9") (pintype "input"))
      (node (ref "IC43") (pin "1") (pinfunction "I_1") (pintype "input"))
      (node (ref "RS08") (pin "3") (pinfunction "3_3") (pintype "passive"))
    )
    (net (code "41") (name "DAR08") (class "Default")
      (node (ref "DAR8-11") (pin "7") (pinfunction "QD_7") (pintype "output"))
      (node (ref "IC1") (pin "10") (pinfunction "B_10") (pintype "input"))
      (node (ref "IC2") (pin "10") (pinfunction "B_10") (pintype "input"))
      (node (ref "IC24") (pin "17") (pinfunction "A4_17") (pintype "input"))
      (node (ref "IC3") (pin "10") (pinfunction "B_10") (pintype "input"))
      (node (ref "IC4") (pin "10") (pinfunction "B_10") (pintype "input"))
      (node (ref "IC43") (pin "3") (pinfunction "I_3") (pintype "input"))
      (node (ref "RS08") (pin "4") (pinfunction "4_4") (pintype "passive"))
    )
    (net (code "42") (name "DAR09") (class "Default")
      (node (ref "DAR8-11") (pin "6") (pinfunction "QC_6") (pintype "output"))
      (node (ref "IC1") (pin "11") (pinfunction "A_11") (pintype "input"))
      (node (ref "IC2") (pin "11") (pinfunction "A_11") (pintype "input"))
      (node (ref "IC24") (pin "15") (pinfunction "A3_15") (pintype "input"))
      (node (ref "IC3") (pin "11") (pinfunction "A_11") (pintype "input"))
      (node (ref "IC4") (pin "11") (pinfunction "A_11") (pintype "input"))
      (node (ref "IC43") (pin "5") (pinfunction "I_5") (pintype "input"))
      (node (ref "RS08") (pin "5") (pinfunction "5_5") (pintype "passive"))
    )
    (net (code "43") (name "DAR10") (class "Default")
      (node (ref "DAR8-11") (pin "2") (pinfunction "QB_2") (pintype "output"))
      (node (ref "IC24") (pin "13") (pinfunction "A2_13") (pintype "input"))
      (node (ref "IC45") (pin "1") (pinfunction "I_1") (pintype "input"))
      (node (ref "RS08") (pin "10") (pinfunction "10_10") (pintype "passive"))
    )
    (net (code "44") (name "DAR11") (class "Default")
      (node (ref "DAR8-11") (pin "3") (pinfunction "QA_3") (pintype "output"))
      (node (ref "IC24") (pin "11") (pinfunction "A1_11") (pintype "input"))
      (node (ref "IC45") (pin "3") (pinfunction "I_3") (pintype "input"))
      (node (ref "RS08") (pin "7") (pinfunction "7_7") (pintype "passive"))
    )
    (net (code "45") (name "DATA_IN") (class "Default")
      (node (ref "C36L") (pin "30") (pinfunction "30_30") (pintype "passive"))
      (node (ref "IC22") (pin "6") (pinfunction "O_6") (pintype "open_collector"))
    )
    (net (code "46") (name "DIO00") (class "Default")
      (node (ref "IC13") (pin "12") (pinfunction "E_12") (pintype "input"))
      (node (ref "IC14") (pin "12") (pinfunction "E_12") (pintype "input"))
      (node (ref "IC33") (pin "1") (pinfunction "I_1") (pintype "input"))
      (node (ref "IC34") (pin "8") (pinfunction "A4_8") (pintype "input"))
      (node (ref "IC35") (pin "12") (pinfunction "Y4_12") (pintype "tri_state"))
      (node (ref "RS08") (pin "36") (pinfunction "36_36") (pintype "passive"))
    )
    (net (code "47") (name "DIO01") (class "Default")
      (node (ref "IC13") (pin "11") (pinfunction "D_11") (pintype "input"))
      (node (ref "IC14") (pin "11") (pinfunction "D_11") (pintype "input"))
      (node (ref "IC33") (pin "3") (pinfunction "I_3") (pintype "input"))
      (node (ref "IC34") (pin "6") (pinfunction "A3_6") (pintype "input"))
      (node (ref "IC35") (pin "14") (pinfunction "Y3_14") (pintype "tri_state"))
      (node (ref "RS08") (pin "37") (pinfunction "37_37") (pintype "passive"))
    )
    (net (code "48") (name "DIO02") (class "Default")
      (node (ref "IC13") (pin "10") (pinfunction "C_10") (pintype "input"))
      (node (ref "IC14") (pin "10") (pinfunction "C_10") (pintype "input"))
      (node (ref "IC33") (pin "5") (pinfunction "I_5") (pintype "input"))
      (node (ref "IC34") (pin "4") (pinfunction "A2_4") (pintype "input"))
      (node (ref "IC35") (pin "16") (pinfunction "Y2_16") (pintype "tri_state"))
      (node (ref "RS08") (pin "35") (pinfunction "35_35") (pintype "passive"))
    )
    (net (code "49") (name "DIO03") (class "Default")
      (node (ref "IC13") (pin "9") (pinfunction "B_9") (pintype "input"))
      (node (ref "IC14") (pin "9") (pinfunction "B_9") (pintype "input"))
      (node (ref "IC34") (pin "2") (pinfunction "A1_2") (pintype "input"))
      (node (ref "IC35") (pin "18") (pinfunction "Y1_18") (pintype "tri_state"))
      (node (ref "IC42") (pin "1") (pinfunction "I_1") (pintype "input"))
      (node (ref "RS08") (pin "33") (pinfunction "33_33") (pintype "passive"))
    )
    (net (code "50") (name "DIO04") (class "Default")
      (node (ref "IC15") (pin "2") (pinfunction "H_2") (pintype "input"))
      (node (ref "IC26") (pin "17") (pinfunction "A4_17") (pintype "input"))
      (node (ref "IC28") (pin "3") (pinfunction "Y4_3") (pintype "tri_state"))
      (node (ref "IC42") (pin "3") (pinfunction "I_3") (pintype "input"))
      (node (ref "RS08") (pin "24") (pinfunction "24_24") (pintype "passive"))
    )
    (net (code "51") (name "DIO05") (class "Default")
      (node (ref "IC15") (pin "1") (pinfunction "G_1") (pintype "input"))
      (node (ref "IC26") (pin "15") (pinfunction "A3_15") (pintype "input"))
      (node (ref "IC28") (pin "5") (pinfunction "Y3_5") (pintype "tri_state"))
      (node (ref "IC42") (pin "5") (pinfunction "I_5") (pintype "input"))
      (node (ref "RS08") (pin "26") (pinfunction "26_26") (pintype "passive"))
    )
    (net (code "52") (name "DIO06") (class "Default")
      (node (ref "IC15") (pin "13") (pinfunction "F_13") (pintype "input"))
      (node (ref "IC26") (pin "13") (pinfunction "A2_13") (pintype "input"))
      (node (ref "IC28") (pin "7") (pinfunction "Y2_7") (pintype "tri_state"))
      (node (ref "IC44") (pin "1") (pinfunction "I_1") (pintype "input"))
      (node (ref "RS08") (pin "28") (pinfunction "28_28") (pintype "passive"))
    )
    (net (code "53") (name "DIO07") (class "Default")
      (node (ref "IC15") (pin "12") (pinfunction "E_12") (pintype "input"))
      (node (ref "IC26") (pin "11") (pinfunction "A1_11") (pintype "input"))
      (node (ref "IC28") (pin "9") (pinfunction "Y1_9") (pintype "tri_state"))
      (node (ref "IC44") (pin "3") (pinfunction "I_3") (pintype "input"))
      (node (ref "RS08") (pin "30") (pinfunction "30_30") (pintype "passive"))
    )
    (net (code "54") (name "DIO08") (class "Default")
      (node (ref "IC15") (pin "11") (pinfunction "D_11") (pintype "input"))
      (node (ref "IC26") (pin "8") (pinfunction "A4_8") (pintype "input"))
      (node (ref "IC28") (pin "12") (pinfunction "Y4_12") (pintype "tri_state"))
      (node (ref "IC44") (pin "5") (pinfunction "I_5") (pintype "input"))
      (node (ref "RS08") (pin "32") (pinfunction "32_32") (pintype "passive"))
    )
    (net (code "55") (name "DIO09") (class "Default")
      (node (ref "IC15") (pin "10") (pinfunction "C_10") (pintype "input"))
      (node (ref "IC26") (pin "6") (pinfunction "A3_6") (pintype "input"))
      (node (ref "IC28") (pin "14") (pinfunction "Y3_14") (pintype "tri_state"))
      (node (ref "IC46") (pin "1") (pinfunction "I_1") (pintype "input"))
      (node (ref "RS08") (pin "29") (pinfunction "29_29") (pintype "passive"))
    )
    (net (code "56") (name "DIO10") (class "Default")
      (node (ref "IC15") (pin "9") (pinfunction "B_9") (pintype "input"))
      (node (ref "IC26") (pin "4") (pinfunction "A2_4") (pintype "input"))
      (node (ref "IC28") (pin "16") (pinfunction "Y2_16") (pintype "tri_state"))
      (node (ref "IC46") (pin "3") (pinfunction "I_3") (pintype "input"))
      (node (ref "RS08") (pin "27") (pinfunction "27_27") (pintype "passive"))
    )
    (net (code "57") (name "DIO11") (class "Default")
      (node (ref "IC15") (pin "8") (pinfunction "A_8") (pintype "input"))
      (node (ref "IC26") (pin "2") (pinfunction "A1_2") (pintype "input"))
      (node (ref "IC28") (pin "18") (pinfunction "Y1_18") (pintype "tri_state"))
      (node (ref "IC46") (pin "5") (pinfunction "I_5") (pintype "input"))
      (node (ref "RS08") (pin "25") (pinfunction "25_25") (pintype "passive"))
    )
    (net (code "58") (name "DIOEVEN") (class "Default")
      (node (ref "IC13") (pin "13") (pinfunction "F_13") (pintype "input"))
      (node (ref "IC35") (pin "9") (pinfunction "Y1_9") (pintype "tri_state"))
      (node (ref "RS08") (pin "34") (pinfunction "34_34") (pintype "passive"))
    )
    (net (code "59") (name "DMA00") (class "Default")
      (node (ref "DMA0-3") (pin "7") (pinfunction "QD_7") (pintype "output"))
      (node (ref "IC27") (pin "9") (pinfunction "I_9") (pintype "input"))
      (node (ref "IC38") (pin "8") (pinfunction "A4_8") (pintype "input"))
      (node (ref "IC45") (pin "5") (pinfunction "I_5") (pintype "input"))
      (node (ref "RS08") (pin "16") (pinfunction "16_16") (pintype "passive"))
    )
    (net (code "60") (name "DMA01") (class "Default")
      (node (ref "DMA0-3") (pin "6") (pinfunction "QC_6") (pintype "output"))
      (node (ref "IC27") (pin "11") (pinfunction "I_11") (pintype "input"))
      (node (ref "IC38") (pin "6") (pinfunction "A3_6") (pintype "input"))
      (node (ref "RS08") (pin "20") (pinfunction "20_20") (pintype "passive"))
    )
    (net (code "61") (name "DMA02") (class "Default")
      (node (ref "DMA0-3") (pin "2") (pinfunction "QB_2") (pintype "output"))
      (node (ref "IC27") (pin "13") (pinfunction "I_13") (pintype "input"))
      (node (ref "IC38") (pin "4") (pinfunction "A2_4") (pintype "input"))
      (node (ref "RS08") (pin "14") (pinfunction "14_14") (pintype "passive"))
    )
    (net (code "62") (name "DMA03") (class "Default")
      (node (ref "DMA0-3") (pin "3") (pinfunction "QA_3") (pintype "output"))
      (node (ref "IC38") (pin "2") (pinfunction "A1_2") (pintype "input"))
      (node (ref "IC39") (pin "9") (pinfunction "I_9") (pintype "input"))
      (node (ref "RS08") (pin "12") (pinfunction "12_12") (pintype "passive"))
    )
    (net (code "63") (name "DMA04") (class "Default")
      (node (ref "DMA4-7") (pin "7") (pinfunction "QD_7") (pintype "output"))
      (node (ref "IC31") (pin "8") (pinfunction "A4_8") (pintype "input"))
      (node (ref "IC39") (pin "11") (pinfunction "I_11") (pintype "input"))
      (node (ref "RS08") (pin "9") (pinfunction "9_9") (pintype "passive"))
    )
    (net (code "64") (name "DMA05") (class "Default")
      (node (ref "DMA4-7") (pin "6") (pinfunction "QC_6") (pintype "output"))
      (node (ref "IC31") (pin "6") (pinfunction "A3_6") (pintype "input"))
      (node (ref "IC39") (pin "13") (pinfunction "I_13") (pintype "input"))
      (node (ref "RS08") (pin "11") (pinfunction "11_11") (pintype "passive"))
    )
    (net (code "65") (name "DMA06") (class "Default")
      (node (ref "DMA4-7") (pin "2") (pinfunction "QB_2") (pintype "output"))
      (node (ref "IC31") (pin "4") (pinfunction "A2_4") (pintype "input"))
      (node (ref "IC43") (pin "9") (pinfunction "I_9") (pintype "input"))
      (node (ref "RS08") (pin "13") (pinfunction "13_13") (pintype "passive"))
    )
    (net (code "66") (name "DMA07") (class "Default")
      (node (ref "DMA4-7") (pin "3") (pinfunction "QA_3") (pintype "output"))
      (node (ref "IC31") (pin "2") (pinfunction "A1_2") (pintype "input"))
      (node (ref "IC43") (pin "11") (pinfunction "I_11") (pintype "input"))
      (node (ref "RS08") (pin "15") (pinfunction "15_15") (pintype "passive"))
    )
    (net (code "67") (name "DMA08") (class "Default")
      (node (ref "DMA8-11") (pin "7") (pinfunction "QD_7") (pintype "output"))
      (node (ref "IC24") (pin "8") (pinfunction "A4_8") (pintype "input"))
      (node (ref "IC43") (pin "13") (pinfunction "I_13") (pintype "input"))
      (node (ref "RS08") (pin "17") (pinfunction "17_17") (pintype "passive"))
    )
    (net (code "68") (name "DMA09") (class "Default")
      (node (ref "DMA8-11") (pin "6") (pinfunction "QC_6") (pintype "output"))
      (node (ref "IC24") (pin "6") (pinfunction "A3_6") (pintype "input"))
      (node (ref "IC45") (pin "9") (pinfunction "I_9") (pintype "input"))
      (node (ref "RS08") (pin "19") (pinfunction "19_19") (pintype "passive"))
    )
    (net (code "69") (name "DMA10") (class "Default")
      (node (ref "DMA8-11") (pin "2") (pinfunction "QB_2") (pintype "output"))
      (node (ref "IC24") (pin "4") (pinfunction "A2_4") (pintype "input"))
      (node (ref "IC45") (pin "11") (pinfunction "I_11") (pintype "input"))
      (node (ref "RS08") (pin "21") (pinfunction "21_21") (pintype "passive"))
    )
    (net (code "70") (name "DMA11") (class "Default")
      (node (ref "DMA8-11") (pin "3") (pinfunction "QA_3") (pintype "output"))
      (node (ref "IC24") (pin "2") (pinfunction "A1_2") (pintype "input"))
      (node (ref "IC45") (pin "13") (pinfunction "I_13") (pintype "input"))
      (node (ref "RS08") (pin "23") (pinfunction "23_23") (pintype "passive"))
    )
    (net (code "71") (name "DONE") (class "Default")
      (node (ref "IC11") (pin "9") (pinfunction "Q_9") (pintype "output"))
      (node (ref "IC40") (pin "2") (pinfunction "I1_2") (pintype "input"))
      (node (ref "IC46") (pin "13") (pinfunction "I_13") (pintype "input"))
    )
    (net (code "72") (name "EIE") (class "Default")
      (node (ref "IC33") (pin "11") (pinfunction "I_11") (pintype "input"))
      (node (ref "IC37") (pin "2") (pinfunction "A1_2") (pintype "input"))
      (node (ref "IC40") (pin "9") (pinfunction "I0_9") (pintype "input"))
      (node (ref "INTENB") (pin "6") (pinfunction "QC_6") (pintype "output"))
    )
    (net (code "73") (name "ERROR") (class "Default")
      (node (ref "IC12") (pin "6") (pinfunction "O_6") (pintype "output"))
      (node (ref "IC40") (pin "10") (pinfunction "I1_10") (pintype "input"))
      (node (ref "IC7") (pin "2") (pinfunction "A_2") (pintype "input"))
    )
    (net (code "74") (name "F.1") (class "Default")
      (node (ref "FIELD") (pin "3") (pinfunction "QA_3") (pintype "output"))
      (node (ref "IC20") (pin "11") (pinfunction "A1_11") (pintype "input"))
      (node (ref "IC27") (pin "5") (pinfunction "I_5") (pintype "input"))
      (node (ref "IC30") (pin "8") (pinfunction "A4_8") (pintype "input"))
    )
    (net (code "75") (name "F.2") (class "Default")
      (node (ref "FIELD") (pin "2") (pinfunction "QB_2") (pintype "output"))
      (node (ref "IC20") (pin "13") (pinfunction "A2_13") (pintype "input"))
      (node (ref "IC27") (pin "3") (pinfunction "I_3") (pintype "input"))
      (node (ref "IC30") (pin "11") (pinfunction "A1_11") (pintype "input"))
    )
    (net (code "76") (name "F.3") (class "Default")
      (node (ref "FIELD") (pin "6") (pinfunction "QC_6") (pintype "output"))
      (node (ref "IC20") (pin "15") (pinfunction "A3_15") (pintype "input"))
      (node (ref "IC27") (pin "1") (pinfunction "I_1") (pintype "input"))
      (node (ref "IC30") (pin "13") (pinfunction "A2_13") (pintype "input"))
    )
    (net (code "77") (name "GND") (class "Default")
      (node (ref "C1") (pin "2") (pinfunction "2_2") (pintype "passive"))
      (node (ref "C35L") (pin "1") (pinfunction "1_1") (pintype "passive"))
      (node (ref "C35L") (pin "11") (pinfunction "11_11") (pintype "passive"))
      (node (ref "C35L") (pin "13") (pinfunction "13_13") (pintype "passive"))
      (node (ref "C35L") (pin "15") (pinfunction "15_15") (pintype "passive"))
      (node (ref "C35L") (pin "17") (pinfunction "17_17") (pintype "passive"))
      (node (ref "C35L") (pin "19") (pinfunction "19_19") (pintype "passive"))
      (node (ref "C35L") (pin "21") (pinfunction "21_21") (pintype "passive"))
      (node (ref "C35L") (pin "23") (pinfunction "23_23") (pintype "passive"))
      (node (ref "C35L") (pin "25") (pinfunction "25_25") (pintype "passive"))
      (node (ref "C35L") (pin "27") (pinfunction "27_27") (pintype "passive"))
      (node (ref "C35L") (pin "29") (pinfunction "29_29") (pintype "passive"))
      (node (ref "C35L") (pin "3") (pinfunction "3_3") (pintype "passive"))
      (node (ref "C35L") (pin "31") (pinfunction "31_31") (pintype "passive"))
      (node (ref "C35L") (pin "33") (pinfunction "33_33") (pintype "passive"))
      (node (ref "C35L") (pin "35") (pinfunction "35_35") (pintype "passive"))
      (node (ref "C35L") (pin "37") (pinfunction "37_37") (pintype "passive"))
      (node (ref "C35L") (pin "39") (pinfunction "39_39") (pintype "passive"))
      (node (ref "C35L") (pin "5") (pinfunction "5_5") (pintype "passive"))
      (node (ref "C35L") (pin "7") (pinfunction "7_7") (pintype "passive"))
      (node (ref "C35L") (pin "9") (pinfunction "9_9") (pintype "passive"))
      (node (ref "C36L") (pin "1") (pinfunction "1_1") (pintype "passive"))
      (node (ref "C36L") (pin "11") (pinfunction "11_11") (pintype "passive"))
      (node (ref "C36L") (pin "13") (pinfunction "13_13") (pintype "passive"))
      (node (ref "C36L") (pin "15") (pinfunction "15_15") (pintype "passive"))
      (node (ref "C36L") (pin "17") (pinfunction "17_17") (pintype "passive"))
      (node (ref "C36L") (pin "19") (pinfunction "19_19") (pintype "passive"))
      (node (ref "C36L") (pin "21") (pinfunction "21_21") (pintype "passive"))
      (node (ref "C36L") (pin "23") (pinfunction "23_23") (pintype "passive"))
      (node (ref "C36L") (pin "25") (pinfunction "25_25") (pintype "passive"))
      (node (ref "C36L") (pin "27") (pinfunction "27_27") (pintype "passive"))
      (node (ref "C36L") (pin "29") (pinfunction "29_29") (pintype "passive"))
      (node (ref "C36L") (pin "3") (pinfunction "3_3") (pintype "passive"))
      (node (ref "C36L") (pin "31") (pinfunction "31_31") (pintype "passive"))
      (node (ref "C36L") (pin "33") (pinfunction "33_33") (pintype "passive"))
      (node (ref "C36L") (pin "35") (pinfunction "35_35") (pintype "passive"))
      (node (ref "C36L") (pin "37") (pinfunction "37_37") (pintype "passive"))
      (node (ref "C36L") (pin "39") (pinfunction "39_39") (pintype "passive"))
      (node (ref "C36L") (pin "5") (pinfunction "5_5") (pintype "passive"))
      (node (ref "C36L") (pin "7") (pinfunction "7_7") (pintype "passive"))
      (node (ref "C36L") (pin "9") (pinfunction "9_9") (pintype "passive"))
      (node (ref "D34L") (pin "1") (pinfunction "1_1") (pintype "passive"))
      (node (ref "D34L") (pin "11") (pinfunction "11_11") (pintype "passive"))
      (node (ref "D34L") (pin "13") (pinfunction "13_13") (pintype "passive"))
      (node (ref "D34L") (pin "15") (pinfunction "15_15") (pintype "passive"))
      (node (ref "D34L") (pin "17") (pinfunction "17_17") (pintype "passive"))
      (node (ref "D34L") (pin "19") (pinfunction "19_19") (pintype "passive"))
      (node (ref "D34L") (pin "21") (pinfunction "21_21") (pintype "passive"))
      (node (ref "D34L") (pin "23") (pinfunction "23_23") (pintype "passive"))
      (node (ref "D34L") (pin "25") (pinfunction "25_25") (pintype "passive"))
      (node (ref "D34L") (pin "27") (pinfunction "27_27") (pintype "passive"))
      (node (ref "D34L") (pin "29") (pinfunction "29_29") (pintype "passive"))
      (node (ref "D34L") (pin "3") (pinfunction "3_3") (pintype "passive"))
      (node (ref "D34L") (pin "31") (pinfunction "31_31") (pintype "passive"))
      (node (ref "D34L") (pin "33") (pinfunction "33_33") (pintype "passive"))
      (node (ref "D34L") (pin "35") (pinfunction "35_35") (pintype "passive"))
      (node (ref "D34L") (pin "37") (pinfunction "37_37") (pintype "passive"))
      (node (ref "D34L") (pin "39") (pinfunction "39_39") (pintype "passive"))
      (node (ref "D34L") (pin "5") (pinfunction "5_5") (pintype "passive"))
      (node (ref "D34L") (pin "7") (pinfunction "7_7") (pintype "passive"))
      (node (ref "D34L") (pin "9") (pinfunction "9_9") (pintype "passive"))
      (node (ref "D35L") (pin "1") (pinfunction "1_1") (pintype "passive"))
      (node (ref "D35L") (pin "11") (pinfunction "11_11") (pintype "passive"))
      (node (ref "D35L") (pin "13") (pinfunction "13_13") (pintype "passive"))
      (node (ref "D35L") (pin "15") (pinfunction "15_15") (pintype "passive"))
      (node (ref "D35L") (pin "17") (pinfunction "17_17") (pintype "passive"))
      (node (ref "D35L") (pin "19") (pinfunction "19_19") (pintype "passive"))
      (node (ref "D35L") (pin "21") (pinfunction "21_21") (pintype "passive"))
      (node (ref "D35L") (pin "23") (pinfunction "23_23") (pintype "passive"))
      (node (ref "D35L") (pin "25") (pinfunction "25_25") (pintype "passive"))
      (node (ref "D35L") (pin "27") (pinfunction "27_27") (pintype "passive"))
      (node (ref "D35L") (pin "29") (pinfunction "29_29") (pintype "passive"))
      (node (ref "D35L") (pin "3") (pinfunction "3_3") (pintype "passive"))
      (node (ref "D35L") (pin "31") (pinfunction "31_31") (pintype "passive"))
      (node (ref "D35L") (pin "33") (pinfunction "33_33") (pintype "passive"))
      (node (ref "D35L") (pin "35") (pinfunction "35_35") (pintype "passive"))
      (node (ref "D35L") (pin "37") (pinfunction "37_37") (pintype "passive"))
      (node (ref "D35L") (pin "39") (pinfunction "39_39") (pintype "passive"))
      (node (ref "D35L") (pin "5") (pinfunction "5_5") (pintype "passive"))
      (node (ref "D35L") (pin "7") (pinfunction "7_7") (pintype "passive"))
      (node (ref "D35L") (pin "9") (pinfunction "9_9") (pintype "passive"))
      (node (ref "D36L") (pin "1") (pinfunction "1_1") (pintype "passive"))
      (node (ref "D36L") (pin "11") (pinfunction "11_11") (pintype "passive"))
      (node (ref "D36L") (pin "13") (pinfunction "13_13") (pintype "passive"))
      (node (ref "D36L") (pin "15") (pinfunction "15_15") (pintype "passive"))
      (node (ref "D36L") (pin "17") (pinfunction "17_17") (pintype "passive"))
      (node (ref "D36L") (pin "19") (pinfunction "19_19") (pintype "passive"))
      (node (ref "D36L") (pin "21") (pinfunction "21_21") (pintype "passive"))
      (node (ref "D36L") (pin "23") (pinfunction "23_23") (pintype "passive"))
      (node (ref "D36L") (pin "25") (pinfunction "25_25") (pintype "passive"))
      (node (ref "D36L") (pin "27") (pinfunction "27_27") (pintype "passive"))
      (node (ref "D36L") (pin "29") (pinfunction "29_29") (pintype "passive"))
      (node (ref "D36L") (pin "3") (pinfunction "3_3") (pintype "passive"))
      (node (ref "D36L") (pin "31") (pinfunction "31_31") (pintype "passive"))
      (node (ref "D36L") (pin "33") (pinfunction "33_33") (pintype "passive"))
      (node (ref "D36L") (pin "35") (pinfunction "35_35") (pintype "passive"))
      (node (ref "D36L") (pin "37") (pinfunction "37_37") (pintype "passive"))
      (node (ref "D36L") (pin "39") (pinfunction "39_39") (pintype "passive"))
      (node (ref "D36L") (pin "5") (pinfunction "5_5") (pintype "passive"))
      (node (ref "D36L") (pin "7") (pinfunction "7_7") (pintype "passive"))
      (node (ref "D36L") (pin "9") (pinfunction "9_9") (pintype "passive"))
      (node (ref "DAR4-7") (pin "4") (pinfunction "DN_4") (pintype "input"))
      (node (ref "DAR8-11") (pin "4") (pinfunction "DN_4") (pintype "input"))
      (node (ref "DMA0-3") (pin "4") (pinfunction "DN_4") (pintype "input"))
      (node (ref "DMA4-7") (pin "4") (pinfunction "DN_4") (pintype "input"))
      (node (ref "DMA8-11") (pin "4") (pinfunction "DN_4") (pintype "input"))
      (node (ref "FIELD") (pin "4") (pinfunction "DN_4") (pintype "input"))
      (node (ref "FIELD") (pin "5") (pinfunction "UP_5") (pintype "input"))
      (node (ref "FIELD") (pin "9") (pinfunction "D_9") (pintype "input"))
      (node (ref "IC1") (pin "7") (pinfunction "G_7") (pintype "input"))
      (node (ref "IC10") (pin "12") (pinfunction "D_12") (pintype "input"))
      (node (ref "IC10") (pin "2") (pinfunction "D_2") (pintype "input"))
      (node (ref "IC13") (pin "1") (pinfunction "G_1") (pintype "input"))
      (node (ref "IC13") (pin "2") (pinfunction "H_2") (pintype "input"))
      (node (ref "IC14") (pin "1") (pinfunction "G_1") (pintype "input"))
      (node (ref "IC14") (pin "13") (pinfunction "F_13") (pintype "input"))
      (node (ref "IC14") (pin "2") (pinfunction "H_2") (pintype "input"))
      (node (ref "IC14") (pin "4") (pinfunction "OI_4") (pintype "input"))
      (node (ref "IC15") (pin "4") (pinfunction "OI_4") (pintype "input"))
      (node (ref "IC16") (pin "1") (pinfunction "G_1") (pintype "input"))
      (node (ref "IC16") (pin "15") (pinfunction "G_15") (pintype "input"))
      (node (ref "IC17") (pin "1") (pinfunction "G_1") (pintype "input"))
      (node (ref "IC17") (pin "15") (pinfunction "G_15") (pintype "input"))
      (node (ref "IC2") (pin "7") (pinfunction "G_7") (pintype "input"))
      (node (ref "IC20") (pin "17") (pinfunction "A4_17") (pintype "input"))
      (node (ref "IC23") (pin "2") (pinfunction "D_2") (pintype "input"))
      (node (ref "IC25") (pin "5") (pinfunction "G2B_5") (pintype "input"))
      (node (ref "IC29") (pin "5") (pinfunction "G2B_5") (pintype "input"))
      (node (ref "IC3") (pin "7") (pinfunction "G_7") (pintype "input"))
      (node (ref "IC30") (pin "6") (pinfunction "A3_6") (pintype "input"))
      (node (ref "IC32") (pin "5") (pinfunction "G2B_5") (pintype "input"))
      (node (ref "IC35") (pin "13") (pinfunction "A2_13") (pintype "input"))
      (node (ref "IC35") (pin "15") (pinfunction "A3_15") (pintype "input"))
      (node (ref "IC35") (pin "17") (pinfunction "A4_17") (pintype "input"))
      (node (ref "IC36") (pin "4") (pinfunction "G2A_4") (pintype "input"))
      (node (ref "IC36") (pin "5") (pinfunction "G2B_5") (pintype "input"))
      (node (ref "IC37") (pin "6") (pinfunction "A3_6") (pintype "input"))
      (node (ref "IC38") (pin "11") (pinfunction "A1_11") (pintype "input"))
      (node (ref "IC38") (pin "13") (pinfunction "A2_13") (pintype "input"))
      (node (ref "IC38") (pin "15") (pinfunction "A3_15") (pintype "input"))
      (node (ref "IC38") (pin "17") (pinfunction "A4_17") (pintype "input"))
      (node (ref "IC4") (pin "7") (pinfunction "G_7") (pintype "input"))
      (node (ref "IC7") (pin "1") (pinfunction "G_1") (pintype "input"))
      (node (ref "IC7") (pin "15") (pinfunction "G_15") (pintype "input"))
      (node (ref "IC8") (pin "1") (pinfunction "GND_1") (pintype "power_in"))
      (node (ref "IC9") (pin "12") (pinfunction "D_12") (pintype "input"))
      (node (ref "IC9") (pin "2") (pinfunction "D_2") (pintype "input"))
      (node (ref "INTENB") (pin "4") (pinfunction "DN_4") (pintype "input"))
      (node (ref "INTENB") (pin "5") (pinfunction "UP_5") (pintype "input"))
      (node (ref "INTENB") (pin "9") (pinfunction "D_9") (pintype "input"))
      (node (ref "J10") (pin "2") (pinfunction "2_2") (pintype "passive"))
      (node (ref "J11") (pin "2") (pinfunction "2_2") (pintype "passive"))
      (node (ref "J12") (pin "2") (pinfunction "2_2") (pintype "passive"))
      (node (ref "J13") (pin "2") (pinfunction "2_2") (pintype "passive"))
      (node (ref "J14") (pin "2") (pinfunction "2_2") (pintype "passive"))
      (node (ref "J2") (pin "2") (pinfunction "2_2") (pintype "passive"))
      (node (ref "J6") (pin "2") (pinfunction "2_2") (pintype "passive"))
      (node (ref "J8") (pin "2") (pinfunction "2_2") (pintype "passive"))
      (node (ref "J9") (pin "2") (pinfunction "2_2") (pintype "passive"))
      (node (ref "RS08") (pin "31") (pinfunction "31_31") (pintype "passive"))
      (node (ref "RS08") (pin "39") (pinfunction "39_39") (pintype "passive"))
    )
    (net (code "78") (name "NXD") (class "Default")
      (node (ref "IC23") (pin "5") (pinfunction "Q_5") (pintype "output"))
      (node (ref "IC30") (pin "4") (pinfunction "A2_4") (pintype "input"))
      (node (ref "IC44") (pin "13") (pinfunction "I_13") (pintype "input"))
    )
    (net (code "79") (name "Net-(DAR4-7A-CLR)") (class "Default")
      (node (ref "DAR4-7") (pin "14") (pinfunction "CLR_14") (pintype "input"))
      (node (ref "DAR8-11") (pin "14") (pinfunction "CLR_14") (pintype "input"))
      (node (ref "IC18") (pin "8") (pinfunction "O_8") (pintype "output"))
    )
    (net (code "80") (name "Net-(DAR4-7A-UP)") (class "Default")
      (node (ref "DAR4-7") (pin "5") (pinfunction "UP_5") (pintype "input"))
      (node (ref "DAR8-11") (pin "12") (pinfunction "CO_12") (pintype "output"))
    )
    (net (code "81") (name "Net-(DAR8-11A-UP)") (class "Default")
      (node (ref "DAR8-11") (pin "5") (pinfunction "UP_5") (pintype "input"))
      (node (ref "DMA0-3") (pin "12") (pinfunction "CO_12") (pintype "output"))
    )
    (net (code "82") (name "Net-(DMA0-3A-CLR)") (class "Default")
      (node (ref "DMA0-3") (pin "14") (pinfunction "CLR_14") (pintype "input"))
      (node (ref "DMA4-7") (pin "14") (pinfunction "CLR_14") (pintype "input"))
      (node (ref "DMA8-11") (pin "14") (pinfunction "CLR_14") (pintype "input"))
      (node (ref "IC18") (pin "6") (pinfunction "O_6") (pintype "output"))
    )
    (net (code "83") (name "Net-(DMA0-3A-UP)") (class "Default")
      (node (ref "DMA0-3") (pin "5") (pinfunction "UP_5") (pintype "input"))
      (node (ref "DMA4-7") (pin "12") (pinfunction "CO_12") (pintype "output"))
    )
    (net (code "84") (name "Net-(DMA4-7A-UP)") (class "Default")
      (node (ref "DMA4-7") (pin "5") (pinfunction "UP_5") (pintype "input"))
      (node (ref "DMA8-11") (pin "12") (pinfunction "CO_12") (pintype "output"))
    )
    (net (code "85") (name "Net-(IC1A-D0)") (class "Default")
      (node (ref "IC1") (pin "4") (pinfunction "D0_4") (pintype "input"))
      (node (ref "SW1") (pin "16") (pinfunction "16_16") (pintype "passive"))
    )
    (net (code "86") (name "Net-(IC1A-D1)") (class "Default")
      (node (ref "IC1") (pin "3") (pinfunction "D1_3") (pintype "input"))
      (node (ref "SW1") (pin "15") (pinfunction "15_15") (pintype "passive"))
    )
    (net (code "87") (name "Net-(IC1A-D2)") (class "Default")
      (node (ref "IC1") (pin "2") (pinfunction "D2_2") (pintype "input"))
      (node (ref "SW1") (pin "14") (pinfunction "14_14") (pintype "passive"))
    )
    (net (code "88") (name "Net-(IC1A-D3)") (class "Default")
      (node (ref "IC1") (pin "1") (pinfunction "D3_1") (pintype "input"))
      (node (ref "SW1") (pin "13") (pinfunction "13_13") (pintype "passive"))
    )
    (net (code "89") (name "Net-(IC1A-D4)") (class "Default")
      (node (ref "IC1") (pin "15") (pinfunction "D4_15") (pintype "input"))
      (node (ref "SW1") (pin "12") (pinfunction "12_12") (pintype "passive"))
    )
    (net (code "90") (name "Net-(IC1A-D5)") (class "Default")
      (node (ref "IC1") (pin "14") (pinfunction "D5_14") (pintype "input"))
      (node (ref "SW1") (pin "11") (pinfunction "11_11") (pintype "passive"))
    )
    (net (code "91") (name "Net-(IC1A-D6)") (class "Default")
      (node (ref "IC1") (pin "13") (pinfunction "D6_13") (pintype "input"))
      (node (ref "SW1") (pin "10") (pinfunction "10_10") (pintype "passive"))
    )
    (net (code "92") (name "Net-(IC1A-D7)") (class "Default")
      (node (ref "IC1") (pin "12") (pinfunction "D7_12") (pintype "input"))
      (node (ref "SW1") (pin "9") (pinfunction "9_9") (pintype "passive"))
    )
    (net (code "93") (name "Net-(IC1A-Y)") (class "Default")
      (node (ref "IC1") (pin "5") (pinfunction "Y_5") (pintype "output"))
      (node (ref "IC5") (pin "1") (pinfunction "I0_1") (pintype "input"))
    )
    (net (code "94") (name "Net-(IC2A-D0)") (class "Default")
      (node (ref "IC2") (pin "4") (pinfunction "D0_4") (pintype "input"))
      (node (ref "SW2") (pin "16") (pinfunction "16_16") (pintype "passive"))
    )
    (net (code "95") (name "Net-(IC2A-D1)") (class "Default")
      (node (ref "IC2") (pin "3") (pinfunction "D1_3") (pintype "input"))
      (node (ref "SW2") (pin "15") (pinfunction "15_15") (pintype "passive"))
    )
    (net (code "96") (name "Net-(IC2A-D2)") (class "Default")
      (node (ref "IC2") (pin "2") (pinfunction "D2_2") (pintype "input"))
      (node (ref "SW2") (pin "14") (pinfunction "14_14") (pintype "passive"))
    )
    (net (code "97") (name "Net-(IC2A-D3)") (class "Default")
      (node (ref "IC2") (pin "1") (pinfunction "D3_1") (pintype "input"))
      (node (ref "SW2") (pin "13") (pinfunction "13_13") (pintype "passive"))
    )
    (net (code "98") (name "Net-(IC2A-D4)") (class "Default")
      (node (ref "IC2") (pin "15") (pinfunction "D4_15") (pintype "input"))
      (node (ref "SW2") (pin "12") (pinfunction "12_12") (pintype "passive"))
    )
    (net (code "99") (name "Net-(IC2A-D5)") (class "Default")
      (node (ref "IC2") (pin "14") (pinfunction "D5_14") (pintype "input"))
      (node (ref "SW2") (pin "11") (pinfunction "11_11") (pintype "passive"))
    )
    (net (code "100") (name "Net-(IC2A-D6)") (class "Default")
      (node (ref "IC2") (pin "13") (pinfunction "D6_13") (pintype "input"))
      (node (ref "SW2") (pin "10") (pinfunction "10_10") (pintype "passive"))
    )
    (net (code "101") (name "Net-(IC2A-D7)") (class "Default")
      (node (ref "IC2") (pin "12") (pinfunction "D7_12") (pintype "input"))
      (node (ref "SW2") (pin "9") (pinfunction "9_9") (pintype "passive"))
    )
    (net (code "102") (name "Net-(IC2A-Y)") (class "Default")
      (node (ref "IC2") (pin "5") (pinfunction "Y_5") (pintype "output"))
      (node (ref "IC5") (pin "2") (pinfunction "I1_2") (pintype "input"))
    )
    (net (code "103") (name "Net-(IC3A-D0)") (class "Default")
      (node (ref "IC3") (pin "4") (pinfunction "D0_4") (pintype "input"))
      (node (ref "SW3") (pin "16") (pinfunction "16_16") (pintype "passive"))
    )
    (net (code "104") (name "Net-(IC3A-D1)") (class "Default")
      (node (ref "IC3") (pin "3") (pinfunction "D1_3") (pintype "input"))
      (node (ref "SW3") (pin "15") (pinfunction "15_15") (pintype "passive"))
    )
    (net (code "105") (name "Net-(IC3A-D2)") (class "Default")
      (node (ref "IC3") (pin "2") (pinfunction "D2_2") (pintype "input"))
      (node (ref "SW3") (pin "14") (pinfunction "14_14") (pintype "passive"))
    )
    (net (code "106") (name "Net-(IC3A-D3)") (class "Default")
      (node (ref "IC3") (pin "1") (pinfunction "D3_1") (pintype "input"))
      (node (ref "SW3") (pin "13") (pinfunction "13_13") (pintype "passive"))
    )
    (net (code "107") (name "Net-(IC3A-D4)") (class "Default")
      (node (ref "IC3") (pin "15") (pinfunction "D4_15") (pintype "input"))
      (node (ref "SW3") (pin "12") (pinfunction "12_12") (pintype "passive"))
    )
    (net (code "108") (name "Net-(IC3A-D5)") (class "Default")
      (node (ref "IC3") (pin "14") (pinfunction "D5_14") (pintype "input"))
      (node (ref "SW3") (pin "11") (pinfunction "11_11") (pintype "passive"))
    )
    (net (code "109") (name "Net-(IC3A-D6)") (class "Default")
      (node (ref "IC3") (pin "13") (pinfunction "D6_13") (pintype "input"))
      (node (ref "SW3") (pin "10") (pinfunction "10_10") (pintype "passive"))
    )
    (net (code "110") (name "Net-(IC3A-D7)") (class "Default")
      (node (ref "IC3") (pin "12") (pinfunction "D7_12") (pintype "input"))
      (node (ref "SW3") (pin "9") (pinfunction "9_9") (pintype "passive"))
    )
    (net (code "111") (name "Net-(IC3A-Y)") (class "Default")
      (node (ref "IC3") (pin "5") (pinfunction "Y_5") (pintype "output"))
      (node (ref "IC5") (pin "4") (pinfunction "I2_4") (pintype "input"))
    )
    (net (code "112") (name "Net-(IC4A-D0)") (class "Default")
      (node (ref "IC4") (pin "4") (pinfunction "D0_4") (pintype "input"))
      (node (ref "SW4") (pin "16") (pinfunction "16_16") (pintype "passive"))
    )
    (net (code "113") (name "Net-(IC4A-D1)") (class "Default")
      (node (ref "IC4") (pin "3") (pinfunction "D1_3") (pintype "input"))
      (node (ref "SW4") (pin "15") (pinfunction "15_15") (pintype "passive"))
    )
    (net (code "114") (name "Net-(IC4A-D2)") (class "Default")
      (node (ref "IC4") (pin "2") (pinfunction "D2_2") (pintype "input"))
      (node (ref "SW4") (pin "14") (pinfunction "14_14") (pintype "passive"))
    )
    (net (code "115") (name "Net-(IC4A-D3)") (class "Default")
      (node (ref "IC4") (pin "1") (pinfunction "D3_1") (pintype "input"))
      (node (ref "SW4") (pin "13") (pinfunction "13_13") (pintype "passive"))
    )
    (net (code "116") (name "Net-(IC4A-D4)") (class "Default")
      (node (ref "IC4") (pin "15") (pinfunction "D4_15") (pintype "input"))
      (node (ref "SW4") (pin "12") (pinfunction "12_12") (pintype "passive"))
    )
    (net (code "117") (name "Net-(IC4A-D5)") (class "Default")
      (node (ref "IC4") (pin "14") (pinfunction "D5_14") (pintype "input"))
      (node (ref "SW4") (pin "11") (pinfunction "11_11") (pintype "passive"))
    )
    (net (code "118") (name "Net-(IC4A-D6)") (class "Default")
      (node (ref "IC4") (pin "13") (pinfunction "D6_13") (pintype "input"))
      (node (ref "SW4") (pin "10") (pinfunction "10_10") (pintype "passive"))
    )
    (net (code "119") (name "Net-(IC4A-D7)") (class "Default")
      (node (ref "IC4") (pin "12") (pinfunction "D7_12") (pintype "input"))
      (node (ref "SW4") (pin "9") (pinfunction "9_9") (pintype "passive"))
    )
    (net (code "120") (name "Net-(IC4A-Y)") (class "Default")
      (node (ref "IC4") (pin "5") (pinfunction "Y_5") (pintype "output"))
      (node (ref "IC5") (pin "5") (pinfunction "I3_5") (pintype "input"))
    )
    (net (code "121") (name "Net-(IC8-CV)") (class "Default")
      (node (ref "C2") (pin "2") (pinfunction "2_2") (pintype "passive"))
      (node (ref "IC8") (pin "5") (pinfunction "CV_5") (pintype "input"))
    )
    (net (code "122") (name "Net-(IC8-DIS)") (class "Default")
      (node (ref "IC8") (pin "7") (pinfunction "DIS_7") (pintype "input"))
      (node (ref "RA") (pin "2") (pinfunction "2_2") (pintype "passive"))
      (node (ref "RB") (pin "1") (pinfunction "1_1") (pintype "passive"))
    )
    (net (code "123") (name "Net-(IC8-THR)") (class "Default")
      (node (ref "C1") (pin "1") (pinfunction "1_1") (pintype "passive"))
      (node (ref "IC8") (pin "2") (pinfunction "TR_2") (pintype "input"))
      (node (ref "IC8") (pin "6") (pinfunction "THR_6") (pintype "input"))
      (node (ref "RB") (pin "2") (pinfunction "2_2") (pintype "passive"))
    )
    (net (code "124") (name "Net-(IC10B-PRE)") (class "Default")
      (node (ref "IC10") (pin "10") (pinfunction "PRE_10") (pintype "input"))
      (node (ref "IC18") (pin "11") (pinfunction "O_11") (pintype "output"))
    )
    (net (code "125") (name "Net-(IC10B-~{Q})") (class "Default")
      (node (ref "IC10") (pin "8") (pinfunction "~{Q}_8") (pintype "output"))
      (node (ref "IC11") (pin "11") (pinfunction "CLK_11") (pintype "input"))
    )
    (net (code "126") (name "Net-(IC12A-I0)") (class "Default")
      (node (ref "IC12") (pin "1") (pinfunction "I0_1") (pintype "input"))
      (node (ref "IC12") (pin "2") (pinfunction "I1_2") (pintype "input"))
      (node (ref "IC8") (pin "3") (pinfunction "Q_3") (pintype "output"))
      (node (ref "RL") (pin "2") (pinfunction "2_2") (pintype "passive"))
    )
    (net (code "127") (name "Net-(IC12B-I1)") (class "Default")
      (node (ref "IC12") (pin "5") (pinfunction "I1_5") (pintype "input"))
      (node (ref "IC12") (pin "8") (pinfunction "O_8") (pintype "output"))
    )
    (net (code "128") (name "Net-(IC12C-I0)") (class "Default")
      (node (ref "IC12") (pin "10") (pinfunction "I1_10") (pintype "input"))
      (node (ref "IC12") (pin "11") (pinfunction "O_11") (pintype "output"))
      (node (ref "IC12") (pin "9") (pinfunction "I0_9") (pintype "input"))
    )
    (net (code "129") (name "Net-(IC13A-A)") (class "Default")
      (node (ref "IC13") (pin "8") (pinfunction "A_8") (pintype "input"))
      (node (ref "IC14") (pin "8") (pinfunction "A_8") (pintype "input"))
      (node (ref "IC15") (pin "6") (pinfunction "ODD_6") (pintype "output"))
    )
    (net (code "130") (name "Net-(IC16B-Y1)") (class "Default")
      (node (ref "IC16") (pin "11") (pinfunction "Y1_11") (pintype "output"))
      (node (ref "IC22") (pin "1") (pinfunction "I_1") (pintype "input"))
    )
    (net (code "131") (name "Net-(IC17A-Y0)") (class "Default")
      (node (ref "IC17") (pin "4") (pinfunction "Y0_4") (pintype "output"))
      (node (ref "IC22") (pin "11") (pinfunction "I_11") (pintype "input"))
    )
    (net (code "132") (name "Net-(IC19A-I)") (class "Default")
      (node (ref "IC19") (pin "1") (pinfunction "I_1") (pintype "input"))
      (node (ref "IC7") (pin "5") (pinfunction "Y1_5") (pintype "output"))
    )
    (net (code "133") (name "Net-(IC19E-I)") (class "Default")
      (node (ref "IC19") (pin "11") (pinfunction "I_11") (pintype "input"))
      (node (ref "IC7") (pin "12") (pinfunction "Y0_12") (pintype "output"))
    )
    (net (code "134") (name "Net-(IC21A-Y0)") (class "Default")
      (node (ref "IC21") (pin "4") (pinfunction "Y0_4") (pintype "output"))
      (node (ref "SW1") (pin "1") (pinfunction "1_1") (pintype "passive"))
      (node (ref "SW1") (pin "2") (pinfunction "2_2") (pintype "passive"))
      (node (ref "SW1") (pin "3") (pinfunction "3_3") (pintype "passive"))
      (node (ref "SW1") (pin "4") (pinfunction "4_4") (pintype "passive"))
      (node (ref "SW1") (pin "5") (pinfunction "5_5") (pintype "passive"))
      (node (ref "SW1") (pin "6") (pinfunction "6_6") (pintype "passive"))
      (node (ref "SW1") (pin "7") (pinfunction "7_7") (pintype "passive"))
      (node (ref "SW1") (pin "8") (pinfunction "8_8") (pintype "passive"))
    )
    (net (code "135") (name "Net-(IC21A-Y1)") (class "Default")
      (node (ref "IC21") (pin "5") (pinfunction "Y1_5") (pintype "output"))
      (node (ref "SW2") (pin "1") (pinfunction "1_1") (pintype "passive"))
      (node (ref "SW2") (pin "2") (pinfunction "2_2") (pintype "passive"))
      (node (ref "SW2") (pin "3") (pinfunction "3_3") (pintype "passive"))
      (node (ref "SW2") (pin "4") (pinfunction "4_4") (pintype "passive"))
      (node (ref "SW2") (pin "5") (pinfunction "5_5") (pintype "passive"))
      (node (ref "SW2") (pin "6") (pinfunction "6_6") (pintype "passive"))
      (node (ref "SW2") (pin "7") (pinfunction "7_7") (pintype "passive"))
      (node (ref "SW2") (pin "8") (pinfunction "8_8") (pintype "passive"))
    )
    (net (code "136") (name "Net-(IC21A-Y2)") (class "Default")
      (node (ref "IC21") (pin "6") (pinfunction "Y2_6") (pintype "output"))
      (node (ref "SW3") (pin "1") (pinfunction "1_1") (pintype "passive"))
      (node (ref "SW3") (pin "2") (pinfunction "2_2") (pintype "passive"))
      (node (ref "SW3") (pin "3") (pinfunction "3_3") (pintype "passive"))
      (node (ref "SW3") (pin "4") (pinfunction "4_4") (pintype "passive"))
      (node (ref "SW3") (pin "5") (pinfunction "5_5") (pintype "passive"))
      (node (ref "SW3") (pin "6") (pinfunction "6_6") (pintype "passive"))
      (node (ref "SW3") (pin "7") (pinfunction "7_7") (pintype "passive"))
      (node (ref "SW3") (pin "8") (pinfunction "8_8") (pintype "passive"))
    )
    (net (code "137") (name "Net-(IC21A-Y3)") (class "Default")
      (node (ref "IC21") (pin "7") (pinfunction "Y3_7") (pintype "output"))
      (node (ref "SW4") (pin "1") (pinfunction "1_1") (pintype "passive"))
      (node (ref "SW4") (pin "2") (pinfunction "2_2") (pintype "passive"))
      (node (ref "SW4") (pin "3") (pinfunction "3_3") (pintype "passive"))
      (node (ref "SW4") (pin "4") (pinfunction "4_4") (pintype "passive"))
      (node (ref "SW4") (pin "5") (pinfunction "5_5") (pintype "passive"))
      (node (ref "SW4") (pin "6") (pinfunction "6_6") (pintype "passive"))
      (node (ref "SW4") (pin "7") (pinfunction "7_7") (pintype "passive"))
      (node (ref "SW4") (pin "8") (pinfunction "8_8") (pintype "passive"))
    )
    (net (code "138") (name "Net-(IC27A-O)") (class "Default")
      (node (ref "IC27") (pin "2") (pinfunction "O_2") (pintype "output"))
      (node (ref "LED1") (pin "K") (pinfunction "C_K") (pintype "passive"))
    )
    (net (code "139") (name "Net-(IC27B-O)") (class "Default")
      (node (ref "IC27") (pin "4") (pinfunction "O_4") (pintype "output"))
      (node (ref "LED2") (pin "K") (pinfunction "C_K") (pintype "passive"))
    )
    (net (code "140") (name "Net-(IC27C-O)") (class "Default")
      (node (ref "IC27") (pin "6") (pinfunction "O_6") (pintype "output"))
      (node (ref "LED3") (pin "K") (pinfunction "C_K") (pintype "passive"))
    )
    (net (code "141") (name "Net-(IC27D-O)") (class "Default")
      (node (ref "IC27") (pin "8") (pinfunction "O_8") (pintype "output"))
      (node (ref "LED13") (pin "K") (pinfunction "C_K") (pintype "passive"))
    )
    (net (code "142") (name "Net-(IC27E-O)") (class "Default")
      (node (ref "IC27") (pin "10") (pinfunction "O_10") (pintype "output"))
      (node (ref "LED14") (pin "K") (pinfunction "C_K") (pintype "passive"))
    )
    (net (code "143") (name "Net-(IC27F-O)") (class "Default")
      (node (ref "IC27") (pin "12") (pinfunction "O_12") (pintype "output"))
      (node (ref "LED15") (pin "K") (pinfunction "C_K") (pintype "passive"))
    )
    (net (code "144") (name "Net-(IC33A-O)") (class "Default")
      (node (ref "IC33") (pin "2") (pinfunction "O_2") (pintype "output"))
      (node (ref "LED25") (pin "K") (pinfunction "C_K") (pintype "passive"))
    )
    (net (code "145") (name "Net-(IC33B-O)") (class "Default")
      (node (ref "IC33") (pin "4") (pinfunction "O_4") (pintype "output"))
      (node (ref "LED26") (pin "K") (pinfunction "C_K") (pintype "passive"))
    )
    (net (code "146") (name "Net-(IC33C-O)") (class "Default")
      (node (ref "IC33") (pin "6") (pinfunction "O_6") (pintype "output"))
      (node (ref "LED27") (pin "K") (pinfunction "C_K") (pintype "passive"))
    )
    (net (code "147") (name "Net-(IC33D-O)") (class "Default")
      (node (ref "IC33") (pin "8") (pinfunction "O_8") (pintype "output"))
      (node (ref "LED37") (pin "K") (pinfunction "C_K") (pintype "passive"))
    )
    (net (code "148") (name "Net-(IC33E-O)") (class "Default")
      (node (ref "IC33") (pin "10") (pinfunction "O_10") (pintype "output"))
      (node (ref "LED38") (pin "K") (pinfunction "C_K") (pintype "passive"))
    )
    (net (code "149") (name "Net-(IC33F-O)") (class "Default")
      (node (ref "IC33") (pin "12") (pinfunction "O_12") (pintype "output"))
      (node (ref "LED39") (pin "K") (pinfunction "C_K") (pintype "passive"))
    )
    (net (code "150") (name "Net-(IC36A-Y0)") (class "Default")
      (node (ref "IC36") (pin "15") (pinfunction "Y0_15") (pintype "output"))
      (node (ref "PAD2") (pin "1") (pinfunction "P_1") (pintype "passive"))
    )
    (net (code "151") (name "Net-(IC36A-Y1)") (class "Default")
      (node (ref "IC36") (pin "14") (pinfunction "Y1_14") (pintype "output"))
      (node (ref "PAD3") (pin "1") (pinfunction "P_1") (pintype "passive"))
    )
    (net (code "152") (name "Net-(IC36A-Y2)") (class "Default")
      (node (ref "IC36") (pin "13") (pinfunction "Y2_13") (pintype "output"))
      (node (ref "PAD4") (pin "1") (pinfunction "P_1") (pintype "passive"))
    )
    (net (code "153") (name "Net-(IC36A-Y3)") (class "Default")
      (node (ref "IC36") (pin "12") (pinfunction "Y3_12") (pintype "output"))
      (node (ref "PAD5") (pin "1") (pinfunction "P_1") (pintype "passive"))
    )
    (net (code "154") (name "Net-(IC36A-Y4)") (class "Default")
      (node (ref "IC36") (pin "11") (pinfunction "Y4_11") (pintype "output"))
      (node (ref "PAD6") (pin "1") (pinfunction "P_1") (pintype "passive"))
    )
    (net (code "155") (name "Net-(IC36A-Y5)") (class "Default")
      (node (ref "IC36") (pin "10") (pinfunction "Y5_10") (pintype "output"))
      (node (ref "PAD7") (pin "1") (pinfunction "P_1") (pintype "passive"))
    )
    (net (code "156") (name "Net-(IC36A-Y6)") (class "Default")
      (node (ref "IC36") (pin "9") (pinfunction "Y6_9") (pintype "output"))
      (node (ref "PAD8") (pin "1") (pinfunction "P_1") (pintype "passive"))
    )
    (net (code "157") (name "Net-(IC36A-Y7)") (class "Default")
      (node (ref "IC36") (pin "7") (pinfunction "Y7_7") (pintype "output"))
      (node (ref "PAD9") (pin "1") (pinfunction "P_1") (pintype "passive"))
    )
    (net (code "158") (name "Net-(IC39A-O)") (class "Default")
      (node (ref "IC39") (pin "2") (pinfunction "O_2") (pintype "output"))
      (node (ref "LED4") (pin "K") (pinfunction "C_K") (pintype "passive"))
    )
    (net (code "159") (name "Net-(IC39B-O)") (class "Default")
      (node (ref "IC39") (pin "4") (pinfunction "O_4") (pintype "output"))
      (node (ref "LED5") (pin "K") (pinfunction "C_K") (pintype "passive"))
    )
    (net (code "160") (name "Net-(IC39C-O)") (class "Default")
      (node (ref "IC39") (pin "6") (pinfunction "O_6") (pintype "output"))
      (node (ref "LED6") (pin "K") (pinfunction "C_K") (pintype "passive"))
    )
    (net (code "161") (name "Net-(IC39D-O)") (class "Default")
      (node (ref "IC39") (pin "8") (pinfunction "O_8") (pintype "output"))
      (node (ref "LED16") (pin "K") (pinfunction "C_K") (pintype "passive"))
    )
    (net (code "162") (name "Net-(IC39E-O)") (class "Default")
      (node (ref "IC39") (pin "10") (pinfunction "O_10") (pintype "output"))
      (node (ref "LED17") (pin "K") (pinfunction "C_K") (pintype "passive"))
    )
    (net (code "163") (name "Net-(IC39F-O)") (class "Default")
      (node (ref "IC39") (pin "12") (pinfunction "O_12") (pintype "output"))
      (node (ref "LED18") (pin "K") (pinfunction "C_K") (pintype "passive"))
    )
    (net (code "164") (name "Net-(IC42A-O)") (class "Default")
      (node (ref "IC42") (pin "2") (pinfunction "O_2") (pintype "output"))
      (node (ref "LED28") (pin "K") (pinfunction "C_K") (pintype "passive"))
    )
    (net (code "165") (name "Net-(IC42B-O)") (class "Default")
      (node (ref "IC42") (pin "4") (pinfunction "O_4") (pintype "output"))
      (node (ref "LED29") (pin "K") (pinfunction "C_K") (pintype "passive"))
    )
    (net (code "166") (name "Net-(IC42C-O)") (class "Default")
      (node (ref "IC42") (pin "6") (pinfunction "O_6") (pintype "output"))
      (node (ref "LED30") (pin "K") (pinfunction "C_K") (pintype "passive"))
    )
    (net (code "167") (name "Net-(IC42E-O)") (class "Default")
      (node (ref "IC42") (pin "10") (pinfunction "O_10") (pintype "output"))
      (node (ref "LED41") (pin "K") (pinfunction "C_K") (pintype "passive"))
    )
    (net (code "168") (name "Net-(IC42F-O)") (class "Default")
      (node (ref "IC42") (pin "12") (pinfunction "O_12") (pintype "output"))
      (node (ref "LED42") (pin "K") (pinfunction "C_K") (pintype "passive"))
    )
    (net (code "169") (name "Net-(IC43A-O)") (class "Default")
      (node (ref "IC43") (pin "2") (pinfunction "O_2") (pintype "output"))
      (node (ref "LED7") (pin "K") (pinfunction "C_K") (pintype "passive"))
    )
    (net (code "170") (name "Net-(IC43B-O)") (class "Default")
      (node (ref "IC43") (pin "4") (pinfunction "O_4") (pintype "output"))
      (node (ref "LED8") (pin "K") (pinfunction "C_K") (pintype "passive"))
    )
    (net (code "171") (name "Net-(IC43C-O)") (class "Default")
      (node (ref "IC43") (pin "6") (pinfunction "O_6") (pintype "output"))
      (node (ref "LED9") (pin "K") (pinfunction "C_K") (pintype "passive"))
    )
    (net (code "172") (name "Net-(IC43D-O)") (class "Default")
      (node (ref "IC43") (pin "8") (pinfunction "O_8") (pintype "output"))
      (node (ref "LED19") (pin "K") (pinfunction "C_K") (pintype "passive"))
    )
    (net (code "173") (name "Net-(IC43E-O)") (class "Default")
      (node (ref "IC43") (pin "10") (pinfunction "O_10") (pintype "output"))
      (node (ref "LED20") (pin "K") (pinfunction "C_K") (pintype "passive"))
    )
    (net (code "174") (name "Net-(IC43F-O)") (class "Default")
      (node (ref "IC43") (pin "12") (pinfunction "O_12") (pintype "output"))
      (node (ref "LED21") (pin "K") (pinfunction "C_K") (pintype "passive"))
    )
    (net (code "175") (name "Net-(IC44A-O)") (class "Default")
      (node (ref "IC44") (pin "2") (pinfunction "O_2") (pintype "output"))
      (node (ref "LED31") (pin "K") (pinfunction "C_K") (pintype "passive"))
    )
    (net (code "176") (name "Net-(IC44B-O)") (class "Default")
      (node (ref "IC44") (pin "4") (pinfunction "O_4") (pintype "output"))
      (node (ref "LED32") (pin "K") (pinfunction "C_K") (pintype "passive"))
    )
    (net (code "177") (name "Net-(IC44C-O)") (class "Default")
      (node (ref "IC44") (pin "6") (pinfunction "O_6") (pintype "output"))
      (node (ref "LED33") (pin "K") (pinfunction "C_K") (pintype "passive"))
    )
    (net (code "178") (name "Net-(IC44E-O)") (class "Default")
      (node (ref "IC44") (pin "10") (pinfunction "O_10") (pintype "output"))
      (node (ref "LED44") (pin "K") (pinfunction "C_K") (pintype "passive"))
    )
    (net (code "179") (name "Net-(IC44F-O)") (class "Default")
      (node (ref "IC44") (pin "12") (pinfunction "O_12") (pintype "output"))
      (node (ref "LED45") (pin "K") (pinfunction "C_K") (pintype "passive"))
    )
    (net (code "180") (name "Net-(IC45A-O)") (class "Default")
      (node (ref "IC45") (pin "2") (pinfunction "O_2") (pintype "output"))
      (node (ref "LED10") (pin "K") (pinfunction "C_K") (pintype "passive"))
    )
    (net (code "181") (name "Net-(IC45B-O)") (class "Default")
      (node (ref "IC45") (pin "4") (pinfunction "O_4") (pintype "output"))
      (node (ref "LED11") (pin "K") (pinfunction "C_K") (pintype "passive"))
    )
    (net (code "182") (name "Net-(IC45C-O)") (class "Default")
      (node (ref "IC45") (pin "6") (pinfunction "O_6") (pintype "output"))
      (node (ref "LED12") (pin "K") (pinfunction "C_K") (pintype "passive"))
    )
    (net (code "183") (name "Net-(IC45D-O)") (class "Default")
      (node (ref "IC45") (pin "8") (pinfunction "O_8") (pintype "output"))
      (node (ref "LED22") (pin "K") (pinfunction "C_K") (pintype "passive"))
    )
    (net (code "184") (name "Net-(IC45E-O)") (class "Default")
      (node (ref "IC45") (pin "10") (pinfunction "O_10") (pintype "output"))
      (node (ref "LED23") (pin "K") (pinfunction "C_K") (pintype "passive"))
    )
    (net (code "185") (name "Net-(IC45F-O)") (class "Default")
      (node (ref "IC45") (pin "12") (pinfunction "O_12") (pintype "output"))
      (node (ref "LED24") (pin "K") (pinfunction "C_K") (pintype "passive"))
    )
    (net (code "186") (name "Net-(IC46A-O)") (class "Default")
      (node (ref "IC46") (pin "2") (pinfunction "O_2") (pintype "output"))
      (node (ref "LED34") (pin "K") (pinfunction "C_K") (pintype "passive"))
    )
    (net (code "187") (name "Net-(IC46B-O)") (class "Default")
      (node (ref "IC46") (pin "4") (pinfunction "O_4") (pintype "output"))
      (node (ref "LED35") (pin "K") (pinfunction "C_K") (pintype "passive"))
    )
    (net (code "188") (name "Net-(IC46C-O)") (class "Default")
      (node (ref "IC46") (pin "6") (pinfunction "O_6") (pintype "output"))
      (node (ref "LED36") (pin "K") (pinfunction "C_K") (pintype "passive"))
    )
    (net (code "189") (name "Net-(IC46D-O)") (class "Default")
      (node (ref "IC46") (pin "8") (pinfunction "O_8") (pintype "output"))
      (node (ref "LED46") (pin "K") (pinfunction "C_K") (pintype "passive"))
    )
    (net (code "190") (name "Net-(IC46E-O)") (class "Default")
      (node (ref "IC46") (pin "10") (pinfunction "O_10") (pintype "output"))
      (node (ref "LED47") (pin "K") (pinfunction "C_K") (pintype "passive"))
    )
    (net (code "191") (name "Net-(IC46F-O)") (class "Default")
      (node (ref "IC46") (pin "12") (pinfunction "O_12") (pintype "output"))
      (node (ref "LED48") (pin "K") (pinfunction "C_K") (pintype "passive"))
    )
    (net (code "192") (name "Net-(LED1-PadA)") (class "Default")
      (node (ref "LED1") (pin "A") (pinfunction "A_A") (pintype "passive"))
      (node (ref "R3") (pin "1") (pinfunction "1_1") (pintype "passive"))
    )
    (net (code "193") (name "Net-(LED2-PadA)") (class "Default")
      (node (ref "LED2") (pin "A") (pinfunction "A_A") (pintype "passive"))
      (node (ref "R4") (pin "1") (pinfunction "1_1") (pintype "passive"))
    )
    (net (code "194") (name "Net-(LED3-PadA)") (class "Default")
      (node (ref "LED3") (pin "A") (pinfunction "A_A") (pintype "passive"))
      (node (ref "R5") (pin "1") (pinfunction "1_1") (pintype "passive"))
    )
    (net (code "195") (name "Net-(LED4-PadA)") (class "Default")
      (node (ref "LED4") (pin "A") (pinfunction "A_A") (pintype "passive"))
      (node (ref "R6") (pin "1") (pinfunction "1_1") (pintype "passive"))
    )
    (net (code "196") (name "Net-(LED5-PadA)") (class "Default")
      (node (ref "LED5") (pin "A") (pinfunction "A_A") (pintype "passive"))
      (node (ref "R7") (pin "1") (pinfunction "1_1") (pintype "passive"))
    )
    (net (code "197") (name "Net-(LED6-PadA)") (class "Default")
      (node (ref "LED6") (pin "A") (pinfunction "A_A") (pintype "passive"))
      (node (ref "R8") (pin "1") (pinfunction "1_1") (pintype "passive"))
    )
    (net (code "198") (name "Net-(LED7-PadA)") (class "Default")
      (node (ref "LED7") (pin "A") (pinfunction "A_A") (pintype "passive"))
      (node (ref "R9") (pin "1") (pinfunction "1_1") (pintype "passive"))
    )
    (net (code "199") (name "Net-(LED8-PadA)") (class "Default")
      (node (ref "LED8") (pin "A") (pinfunction "A_A") (pintype "passive"))
      (node (ref "R10") (pin "1") (pinfunction "1_1") (pintype "passive"))
    )
    (net (code "200") (name "Net-(LED9-PadA)") (class "Default")
      (node (ref "LED9") (pin "A") (pinfunction "A_A") (pintype "passive"))
      (node (ref "R11") (pin "1") (pinfunction "1_1") (pintype "passive"))
    )
    (net (code "201") (name "Net-(LED10-PadA)") (class "Default")
      (node (ref "LED10") (pin "A") (pinfunction "A_A") (pintype "passive"))
      (node (ref "R12") (pin "1") (pinfunction "1_1") (pintype "passive"))
    )
    (net (code "202") (name "Net-(LED11-PadA)") (class "Default")
      (node (ref "LED11") (pin "A") (pinfunction "A_A") (pintype "passive"))
      (node (ref "R13") (pin "1") (pinfunction "1_1") (pintype "passive"))
    )
    (net (code "203") (name "Net-(LED12-PadA)") (class "Default")
      (node (ref "LED12") (pin "A") (pinfunction "A_A") (pintype "passive"))
      (node (ref "R14") (pin "1") (pinfunction "1_1") (pintype "passive"))
    )
    (net (code "204") (name "Net-(LED13-PadA)") (class "Default")
      (node (ref "LED13") (pin "A") (pinfunction "A_A") (pintype "passive"))
      (node (ref "R15") (pin "1") (pinfunction "1_1") (pintype "passive"))
    )
    (net (code "205") (name "Net-(LED14-PadA)") (class "Default")
      (node (ref "LED14") (pin "A") (pinfunction "A_A") (pintype "passive"))
      (node (ref "R16") (pin "1") (pinfunction "1_1") (pintype "passive"))
    )
    (net (code "206") (name "Net-(LED15-PadA)") (class "Default")
      (node (ref "LED15") (pin "A") (pinfunction "A_A") (pintype "passive"))
      (node (ref "R17") (pin "1") (pinfunction "1_1") (pintype "passive"))
    )
    (net (code "207") (name "Net-(LED16-PadA)") (class "Default")
      (node (ref "LED16") (pin "A") (pinfunction "A_A") (pintype "passive"))
      (node (ref "R18") (pin "1") (pinfunction "1_1") (pintype "passive"))
    )
    (net (code "208") (name "Net-(LED17-PadA)") (class "Default")
      (node (ref "LED17") (pin "A") (pinfunction "A_A") (pintype "passive"))
      (node (ref "R19") (pin "1") (pinfunction "1_1") (pintype "passive"))
    )
    (net (code "209") (name "Net-(LED18-PadA)") (class "Default")
      (node (ref "LED18") (pin "A") (pinfunction "A_A") (pintype "passive"))
      (node (ref "R20") (pin "1") (pinfunction "1_1") (pintype "passive"))
    )
    (net (code "210") (name "Net-(LED19-PadA)") (class "Default")
      (node (ref "LED19") (pin "A") (pinfunction "A_A") (pintype "passive"))
      (node (ref "R21") (pin "1") (pinfunction "1_1") (pintype "passive"))
    )
    (net (code "211") (name "Net-(LED20-PadA)") (class "Default")
      (node (ref "LED20") (pin "A") (pinfunction "A_A") (pintype "passive"))
      (node (ref "R22") (pin "1") (pinfunction "1_1") (pintype "passive"))
    )
    (net (code "212") (name "Net-(LED21-PadA)") (class "Default")
      (node (ref "LED21") (pin "A") (pinfunction "A_A") (pintype "passive"))
      (node (ref "R23") (pin "1") (pinfunction "1_1") (pintype "passive"))
    )
    (net (code "213") (name "Net-(LED22-PadA)") (class "Default")
      (node (ref "LED22") (pin "A") (pinfunction "A_A") (pintype "passive"))
      (node (ref "R24") (pin "1") (pinfunction "1_1") (pintype "passive"))
    )
    (net (code "214") (name "Net-(LED23-PadA)") (class "Default")
      (node (ref "LED23") (pin "A") (pinfunction "A_A") (pintype "passive"))
      (node (ref "R25") (pin "1") (pinfunction "1_1") (pintype "passive"))
    )
    (net (code "215") (name "Net-(LED24-PadA)") (class "Default")
      (node (ref "LED24") (pin "A") (pinfunction "A_A") (pintype "passive"))
      (node (ref "R26") (pin "1") (pinfunction "1_1") (pintype "passive"))
    )
    (net (code "216") (name "Net-(LED25-PadA)") (class "Default")
      (node (ref "LED25") (pin "A") (pinfunction "A_A") (pintype "passive"))
      (node (ref "R27") (pin "1") (pinfunction "1_1") (pintype "passive"))
    )
    (net (code "217") (name "Net-(LED26-PadA)") (class "Default")
      (node (ref "LED26") (pin "A") (pinfunction "A_A") (pintype "passive"))
      (node (ref "R28") (pin "1") (pinfunction "1_1") (pintype "passive"))
    )
    (net (code "218") (name "Net-(LED27-PadA)") (class "Default")
      (node (ref "LED27") (pin "A") (pinfunction "A_A") (pintype "passive"))
      (node (ref "R29") (pin "1") (pinfunction "1_1") (pintype "passive"))
    )
    (net (code "219") (name "Net-(LED28-PadA)") (class "Default")
      (node (ref "LED28") (pin "A") (pinfunction "A_A") (pintype "passive"))
      (node (ref "R30") (pin "1") (pinfunction "1_1") (pintype "passive"))
    )
    (net (code "220") (name "Net-(LED29-PadA)") (class "Default")
      (node (ref "LED29") (pin "A") (pinfunction "A_A") (pintype "passive"))
      (node (ref "R31") (pin "1") (pinfunction "1_1") (pintype "passive"))
    )
    (net (code "221") (name "Net-(LED30-PadA)") (class "Default")
      (node (ref "LED30") (pin "A") (pinfunction "A_A") (pintype "passive"))
      (node (ref "R32") (pin "1") (pinfunction "1_1") (pintype "passive"))
    )
    (net (code "222") (name "Net-(LED31-PadA)") (class "Default")
      (node (ref "LED31") (pin "A") (pinfunction "A_A") (pintype "passive"))
      (node (ref "R33") (pin "1") (pinfunction "1_1") (pintype "passive"))
    )
    (net (code "223") (name "Net-(LED32-PadA)") (class "Default")
      (node (ref "LED32") (pin "A") (pinfunction "A_A") (pintype "passive"))
      (node (ref "R34") (pin "1") (pinfunction "1_1") (pintype "passive"))
    )
    (net (code "224") (name "Net-(LED33-PadA)") (class "Default")
      (node (ref "LED33") (pin "A") (pinfunction "A_A") (pintype "passive"))
      (node (ref "R35") (pin "1") (pinfunction "1_1") (pintype "passive"))
    )
    (net (code "225") (name "Net-(LED34-PadA)") (class "Default")
      (node (ref "LED34") (pin "A") (pinfunction "A_A") (pintype "passive"))
      (node (ref "R36") (pin "1") (pinfunction "1_1") (pintype "passive"))
    )
    (net (code "226") (name "Net-(LED35-PadA)") (class "Default")
      (node (ref "LED35") (pin "A") (pinfunction "A_A") (pintype "passive"))
      (node (ref "R37") (pin "1") (pinfunction "1_1") (pintype "passive"))
    )
    (net (code "227") (name "Net-(LED36-PadA)") (class "Default")
      (node (ref "LED36") (pin "A") (pinfunction "A_A") (pintype "passive"))
      (node (ref "R38") (pin "1") (pinfunction "1_1") (pintype "passive"))
    )
    (net (code "228") (name "Net-(LED37-PadA)") (class "Default")
      (node (ref "LED37") (pin "A") (pinfunction "A_A") (pintype "passive"))
      (node (ref "R39") (pin "1") (pinfunction "1_1") (pintype "passive"))
    )
    (net (code "229") (name "Net-(LED38-PadA)") (class "Default")
      (node (ref "LED38") (pin "A") (pinfunction "A_A") (pintype "passive"))
      (node (ref "R40") (pin "1") (pinfunction "1_1") (pintype "passive"))
    )
    (net (code "230") (name "Net-(LED39-PadA)") (class "Default")
      (node (ref "LED39") (pin "A") (pinfunction "A_A") (pintype "passive"))
      (node (ref "R41") (pin "1") (pinfunction "1_1") (pintype "passive"))
    )
    (net (code "231") (name "Net-(LED40-C)") (class "Default")
      (node (ref "LED40") (pin "K") (pinfunction "C_K") (pintype "passive"))
      (node (ref "PAD10") (pin "1") (pinfunction "P_1") (pintype "passive"))
    )
    (net (code "232") (name "Net-(LED40-PadA)") (class "Default")
      (node (ref "LED40") (pin "A") (pinfunction "A_A") (pintype "passive"))
      (node (ref "R42") (pin "1") (pinfunction "1_1") (pintype "passive"))
    )
    (net (code "233") (name "Net-(LED41-PadA)") (class "Default")
      (node (ref "LED41") (pin "A") (pinfunction "A_A") (pintype "passive"))
      (node (ref "R43") (pin "1") (pinfunction "1_1") (pintype "passive"))
    )
    (net (code "234") (name "Net-(LED42-PadA)") (class "Default")
      (node (ref "LED42") (pin "A") (pinfunction "A_A") (pintype "passive"))
      (node (ref "R44") (pin "1") (pinfunction "1_1") (pintype "passive"))
    )
    (net (code "235") (name "Net-(LED43-C)") (class "Default")
      (node (ref "LED43") (pin "K") (pinfunction "C_K") (pintype "passive"))
      (node (ref "PAD11") (pin "1") (pinfunction "P_1") (pintype "passive"))
    )
    (net (code "236") (name "Net-(LED43-PadA)") (class "Default")
      (node (ref "LED43") (pin "A") (pinfunction "A_A") (pintype "passive"))
      (node (ref "R45") (pin "1") (pinfunction "1_1") (pintype "passive"))
    )
    (net (code "237") (name "Net-(LED44-PadA)") (class "Default")
      (node (ref "LED44") (pin "A") (pinfunction "A_A") (pintype "passive"))
      (node (ref "R46") (pin "1") (pinfunction "1_1") (pintype "passive"))
    )
    (net (code "238") (name "Net-(LED45-PadA)") (class "Default")
      (node (ref "LED45") (pin "A") (pinfunction "A_A") (pintype "passive"))
      (node (ref "R47") (pin "1") (pinfunction "1_1") (pintype "passive"))
    )
    (net (code "239") (name "Net-(LED46-PadA)") (class "Default")
      (node (ref "LED46") (pin "A") (pinfunction "A_A") (pintype "passive"))
      (node (ref "R48") (pin "1") (pinfunction "1_1") (pintype "passive"))
    )
    (net (code "240") (name "Net-(LED47-PadA)") (class "Default")
      (node (ref "LED47") (pin "A") (pinfunction "A_A") (pintype "passive"))
      (node (ref "R49") (pin "1") (pinfunction "1_1") (pintype "passive"))
    )
    (net (code "241") (name "Net-(LED48-PadA)") (class "Default")
      (node (ref "LED48") (pin "A") (pinfunction "A_A") (pintype "passive"))
      (node (ref "R50") (pin "1") (pinfunction "1_1") (pintype "passive"))
    )
    (net (code "242") (name "PBIT") (class "Default")
      (node (ref "IC14") (pin "6") (pinfunction "ODD_6") (pintype "output"))
      (node (ref "IC35") (pin "11") (pinfunction "A1_11") (pintype "input"))
    )
    (net (code "243") (name "PCA") (class "Default")
      (node (ref "IC12") (pin "3") (pinfunction "O_3") (pintype "output"))
      (node (ref "IC37") (pin "8") (pinfunction "A4_8") (pintype "input"))
      (node (ref "IC40") (pin "5") (pinfunction "I1_5") (pintype "input"))
    )
    (net (code "244") (name "PER") (class "Default")
      (node (ref "IC30") (pin "2") (pinfunction "A1_2") (pintype "input"))
      (node (ref "IC46") (pin "11") (pinfunction "I_11") (pintype "input"))
      (node (ref "IC9") (pin "9") (pinfunction "Q_9") (pintype "output"))
    )
    (net (code "245") (name "PIE") (class "Default")
      (node (ref "IC30") (pin "17") (pinfunction "A4_17") (pintype "input"))
      (node (ref "IC33") (pin "13") (pinfunction "I_13") (pintype "input"))
      (node (ref "IC40") (pin "4") (pinfunction "I0_4") (pintype "input"))
      (node (ref "INTENB") (pin "2") (pinfunction "QB_2") (pintype "output"))
    )
    (net (code "246") (name "PROTECT") (class "Default")
      (node (ref "IC5") (pin "6") (pinfunction "O_6") (pintype "output"))
      (node (ref "IC6") (pin "3") (pinfunction "B_3") (pintype "input"))
    )
    (net (code "247") (name "VCC") (class "Default")
      (node (ref "C2") (pin "1") (pinfunction "1_1") (pintype "passive"))
      (node (ref "IC11") (pin "10") (pinfunction "PRE_10") (pintype "input"))
      (node (ref "IC11") (pin "4") (pinfunction "PRE_4") (pintype "input"))
      (node (ref "IC13") (pin "3") (pinfunction "EI_3") (pintype "input"))
      (node (ref "IC14") (pin "3") (pinfunction "EI_3") (pintype "input"))
      (node (ref "IC15") (pin "3") (pinfunction "EI_3") (pintype "input"))
      (node (ref "IC36") (pin "6") (pinfunction "G1_6") (pintype "input"))
      (node (ref "IC8") (pin "4") (pinfunction "R_4") (pintype "input"))
      (node (ref "IC8") (pin "8") (pinfunction "V+_8") (pintype "power_in"))
      (node (ref "J3") (pin "2") (pinfunction "2_2") (pintype "passive"))
      (node (ref "J4") (pin "2") (pinfunction "2_2") (pintype "passive"))
      (node (ref "J5") (pin "2") (pinfunction "2_2") (pintype "passive"))
      (node (ref "J7") (pin "2") (pinfunction "2_2") (pintype "passive"))
      (node (ref "R1") (pin "2") (pinfunction "2_2") (pintype "passive"))
      (node (ref "R10") (pin "2") (pinfunction "2_2") (pintype "passive"))
      (node (ref "R11") (pin "2") (pinfunction "2_2") (pintype "passive"))
      (node (ref "R12") (pin "2") (pinfunction "2_2") (pintype "passive"))
      (node (ref "R13") (pin "2") (pinfunction "2_2") (pintype "passive"))
      (node (ref "R14") (pin "2") (pinfunction "2_2") (pintype "passive"))
      (node (ref "R15") (pin "2") (pinfunction "2_2") (pintype "passive"))
      (node (ref "R16") (pin "2") (pinfunction "2_2") (pintype "passive"))
      (node (ref "R17") (pin "2") (pinfunction "2_2") (pintype "passive"))
      (node (ref "R18") (pin "2") (pinfunction "2_2") (pintype "passive"))
      (node (ref "R19") (pin "2") (pinfunction "2_2") (pintype "passive"))
      (node (ref "R2") (pin "2") (pinfunction "2_2") (pintype "passive"))
      (node (ref "R20") (pin "2") (pinfunction "2_2") (pintype "passive"))
      (node (ref "R21") (pin "2") (pinfunction "2_2") (pintype "passive"))
      (node (ref "R22") (pin "2") (pinfunction "2_2") (pintype "passive"))
      (node (ref "R23") (pin "2") (pinfunction "2_2") (pintype "passive"))
      (node (ref "R24") (pin "2") (pinfunction "2_2") (pintype "passive"))
      (node (ref "R25") (pin "2") (pinfunction "2_2") (pintype "passive"))
      (node (ref "R26") (pin "2") (pinfunction "2_2") (pintype "passive"))
      (node (ref "R27") (pin "2") (pinfunction "2_2") (pintype "passive"))
      (node (ref "R28") (pin "2") (pinfunction "2_2") (pintype "passive"))
      (node (ref "R29") (pin "2") (pinfunction "2_2") (pintype "passive"))
      (node (ref "R3") (pin "2") (pinfunction "2_2") (pintype "passive"))
      (node (ref "R30") (pin "2") (pinfunction "2_2") (pintype "passive"))
      (node (ref "R31") (pin "2") (pinfunction "2_2") (pintype "passive"))
      (node (ref "R32") (pin "2") (pinfunction "2_2") (pintype "passive"))
      (node (ref "R33") (pin "2") (pinfunction "2_2") (pintype "passive"))
      (node (ref "R34") (pin "2") (pinfunction "2_2") (pintype "passive"))
      (node (ref "R35") (pin "2") (pinfunction "2_2") (pintype "passive"))
      (node (ref "R36") (pin "2") (pinfunction "2_2") (pintype "passive"))
      (node (ref "R37") (pin "2") (pinfunction "2_2") (pintype "passive"))
      (node (ref "R38") (pin "2") (pinfunction "2_2") (pintype "passive"))
      (node (ref "R39") (pin "2") (pinfunction "2_2") (pintype "passive"))
      (node (ref "R4") (pin "2") (pinfunction "2_2") (pintype "passive"))
      (node (ref "R40") (pin "2") (pinfunction "2_2") (pintype "passive"))
      (node (ref "R41") (pin "2") (pinfunction "2_2") (pintype "passive"))
      (node (ref "R42") (pin "2") (pinfunction "2_2") (pintype "passive"))
      (node (ref "R43") (pin "2") (pinfunction "2_2") (pintype "passive"))
      (node (ref "R44") (pin "2") (pinfunction "2_2") (pintype "passive"))
      (node (ref "R45") (pin "2") (pinfunction "2_2") (pintype "passive"))
      (node (ref "R46") (pin "2") (pinfunction "2_2") (pintype "passive"))
      (node (ref "R47") (pin "2") (pinfunction "2_2") (pintype "passive"))
      (node (ref "R48") (pin "2") (pinfunction "2_2") (pintype "passive"))
      (node (ref "R49") (pin "2") (pinfunction "2_2") (pintype "passive"))
      (node (ref "R5") (pin "2") (pinfunction "2_2") (pintype "passive"))
      (node (ref "R50") (pin "2") (pinfunction "2_2") (pintype "passive"))
      (node (ref "R6") (pin "2") (pinfunction "2_2") (pintype "passive"))
      (node (ref "R7") (pin "2") (pinfunction "2_2") (pintype "passive"))
      (node (ref "R8") (pin "2") (pinfunction "2_2") (pintype "passive"))
      (node (ref "R9") (pin "2") (pinfunction "2_2") (pintype "passive"))
      (node (ref "RA") (pin "1") (pinfunction "1_1") (pintype "passive"))
      (node (ref "RL") (pin "1") (pinfunction "1_1") (pintype "passive"))
      (node (ref "RS08") (pin "2") (pinfunction "2_2") (pintype "passive"))
    )
    (net (code "248") (name "WLS") (class "Default")
      (node (ref "IC37") (pin "4") (pinfunction "A2_4") (pintype "input"))
      (node (ref "IC44") (pin "11") (pinfunction "I_11") (pintype "input"))
      (node (ref "IC9") (pin "5") (pinfunction "Q_5") (pintype "output"))
    )
    (net (code "249") (name "WRITING") (class "Default")
      (node (ref "IC10") (pin "5") (pinfunction "Q_5") (pintype "output"))
      (node (ref "IC41") (pin "13") (pinfunction "B_13") (pintype "input"))
      (node (ref "IC41") (pin "14") (pinfunction "A_14") (pintype "input"))
      (node (ref "IC42") (pin "11") (pinfunction "I_11") (pintype "input"))
      (node (ref "IC6") (pin "2") (pinfunction "A_2") (pintype "input"))
      (node (ref "RS08") (pin "18") (pinfunction "18_18") (pintype "passive"))
    )
    (net (code "250") (name "unconnected-(C35L-Pad20)") (class "Default")
      (node (ref "C35L") (pin "20") (pinfunction "20_20") (pintype "passive"))
    )
    (net (code "251") (name "unconnected-(C35L-Pad40)") (class "Default")
      (node (ref "C35L") (pin "40") (pinfunction "40_40") (pintype "passive"))
    )
    (net (code "252") (name "unconnected-(C36L-Pad20)") (class "Default")
      (node (ref "C36L") (pin "20") (pinfunction "20_20") (pintype "passive"))
    )
    (net (code "253") (name "unconnected-(C36L-Pad40)") (class "Default")
      (node (ref "C36L") (pin "40") (pinfunction "40_40") (pintype "passive"))
    )
    (net (code "254") (name "unconnected-(D34L-Pad20)") (class "Default")
      (node (ref "D34L") (pin "20") (pinfunction "20_20") (pintype "passive"))
    )
    (net (code "255") (name "unconnected-(D34L-Pad36)") (class "Default")
      (node (ref "D34L") (pin "36") (pinfunction "36_36") (pintype "passive"))
    )
    (net (code "256") (name "unconnected-(D34L-Pad38)") (class "Default")
      (node (ref "D34L") (pin "38") (pinfunction "38_38") (pintype "passive"))
    )
    (net (code "257") (name "unconnected-(D34L-Pad40)") (class "Default")
      (node (ref "D34L") (pin "40") (pinfunction "40_40") (pintype "passive"))
    )
    (net (code "258") (name "unconnected-(D35L-Pad20)") (class "Default")
      (node (ref "D35L") (pin "20") (pinfunction "20_20") (pintype "passive"))
    )
    (net (code "259") (name "unconnected-(D35L-Pad40)") (class "Default")
      (node (ref "D35L") (pin "40") (pinfunction "40_40") (pintype "passive"))
    )
    (net (code "260") (name "unconnected-(D36L-Pad20)") (class "Default")
      (node (ref "D36L") (pin "20") (pinfunction "20_20") (pintype "passive"))
    )
    (net (code "261") (name "unconnected-(D36L-Pad40)") (class "Default")
      (node (ref "D36L") (pin "40") (pinfunction "40_40") (pintype "passive"))
    )
    (net (code "262") (name "unconnected-(DAR4-7A-BO-Pad13)") (class "Default")
      (node (ref "DAR4-7") (pin "13") (pinfunction "BO_13") (pintype "output"))
    )
    (net (code "263") (name "unconnected-(DAR4-7A-CO-Pad12)") (class "Default")
      (node (ref "DAR4-7") (pin "12") (pinfunction "CO_12") (pintype "output"))
    )
    (net (code "264") (name "unconnected-(DAR8-11A-BO-Pad13)") (class "Default")
      (node (ref "DAR8-11") (pin "13") (pinfunction "BO_13") (pintype "output"))
    )
    (net (code "265") (name "unconnected-(DMA0-3A-BO-Pad13)") (class "Default")
      (node (ref "DMA0-3") (pin "13") (pinfunction "BO_13") (pintype "output"))
    )
    (net (code "266") (name "unconnected-(DMA4-7A-BO-Pad13)") (class "Default")
      (node (ref "DMA4-7") (pin "13") (pinfunction "BO_13") (pintype "output"))
    )
    (net (code "267") (name "unconnected-(DMA8-11A-BO-Pad13)") (class "Default")
      (node (ref "DMA8-11") (pin "13") (pinfunction "BO_13") (pintype "output"))
    )
    (net (code "268") (name "unconnected-(FIELDA-BO-Pad13)") (class "Default")
      (node (ref "FIELD") (pin "13") (pinfunction "BO_13") (pintype "output"))
    )
    (net (code "269") (name "unconnected-(FIELDA-CO-Pad12)") (class "Default")
      (node (ref "FIELD") (pin "12") (pinfunction "CO_12") (pintype "output"))
    )
    (net (code "270") (name "unconnected-(FIELDA-QD-Pad7)") (class "Default")
      (node (ref "FIELD") (pin "7") (pinfunction "QD_7") (pintype "output"))
    )
    (net (code "271") (name "unconnected-(IC1A-W-Pad6)") (class "Default")
      (node (ref "IC1") (pin "6") (pinfunction "W_6") (pintype "output"))
    )
    (net (code "272") (name "unconnected-(IC2A-W-Pad6)") (class "Default")
      (node (ref "IC2") (pin "6") (pinfunction "W_6") (pintype "output"))
    )
    (net (code "273") (name "unconnected-(IC3A-W-Pad6)") (class "Default")
      (node (ref "IC3") (pin "6") (pinfunction "W_6") (pintype "output"))
    )
    (net (code "274") (name "unconnected-(IC4A-W-Pad6)") (class "Default")
      (node (ref "IC4") (pin "6") (pinfunction "W_6") (pintype "output"))
    )
    (net (code "275") (name "unconnected-(IC6A-Y0-Pad4)") (class "Default")
      (node (ref "IC6") (pin "4") (pinfunction "Y0_4") (pintype "output"))
    )
    (net (code "276") (name "unconnected-(IC6A-Y2-Pad6)") (class "Default")
      (node (ref "IC6") (pin "6") (pinfunction "Y2_6") (pintype "output"))
    )
    (net (code "277") (name "unconnected-(IC7A-Y0-Pad4)") (class "Default")
      (node (ref "IC7") (pin "4") (pinfunction "Y0_4") (pintype "output"))
    )
    (net (code "278") (name "unconnected-(IC7A-Y2-Pad6)") (class "Default")
      (node (ref "IC7") (pin "6") (pinfunction "Y2_6") (pintype "output"))
    )
    (net (code "279") (name "unconnected-(IC7A-Y3-Pad7)") (class "Default")
      (node (ref "IC7") (pin "7") (pinfunction "Y3_7") (pintype "output"))
    )
    (net (code "280") (name "unconnected-(IC7B-Y1-Pad11)") (class "Default")
      (node (ref "IC7") (pin "11") (pinfunction "Y1_11") (pintype "output"))
    )
    (net (code "281") (name "unconnected-(IC7B-Y2-Pad10)") (class "Default")
      (node (ref "IC7") (pin "10") (pinfunction "Y2_10") (pintype "output"))
    )
    (net (code "282") (name "unconnected-(IC7B-Y3-Pad9)") (class "Default")
      (node (ref "IC7") (pin "9") (pinfunction "Y3_9") (pintype "output"))
    )
    (net (code "283") (name "unconnected-(IC10A-~{Q}-Pad6)") (class "Default")
      (node (ref "IC10") (pin "6") (pinfunction "~{Q}_6") (pintype "output"))
    )
    (net (code "284") (name "unconnected-(IC11B-~{Q}-Pad8)") (class "Default")
      (node (ref "IC11") (pin "8") (pinfunction "~{Q}_8") (pintype "output"))
    )
    (net (code "285") (name "unconnected-(IC13A-ODD-Pad6)") (class "Default")
      (node (ref "IC13") (pin "6") (pinfunction "ODD_6") (pintype "output"))
    )
    (net (code "286") (name "unconnected-(IC14A-EVN-Pad5)") (class "Default")
      (node (ref "IC14") (pin "5") (pinfunction "EVN_5") (pintype "output"))
    )
    (net (code "287") (name "unconnected-(IC15A-EVN-Pad5)") (class "Default")
      (node (ref "IC15") (pin "5") (pinfunction "EVN_5") (pintype "output"))
    )
    (net (code "288") (name "unconnected-(IC16A-Y1-Pad5)") (class "Default")
      (node (ref "IC16") (pin "5") (pinfunction "Y1_5") (pintype "output"))
    )
    (net (code "289") (name "unconnected-(IC16A-Y2-Pad6)") (class "Default")
      (node (ref "IC16") (pin "6") (pinfunction "Y2_6") (pintype "output"))
    )
    (net (code "290") (name "unconnected-(IC16A-Y3-Pad7)") (class "Default")
      (node (ref "IC16") (pin "7") (pinfunction "Y3_7") (pintype "output"))
    )
    (net (code "291") (name "unconnected-(IC16B-Y2-Pad10)") (class "Default")
      (node (ref "IC16") (pin "10") (pinfunction "Y2_10") (pintype "output"))
    )
    (net (code "292") (name "unconnected-(IC16B-Y3-Pad9)") (class "Default")
      (node (ref "IC16") (pin "9") (pinfunction "Y3_9") (pintype "output"))
    )
    (net (code "293") (name "unconnected-(IC17A-Y1-Pad5)") (class "Default")
      (node (ref "IC17") (pin "5") (pinfunction "Y1_5") (pintype "output"))
    )
    (net (code "294") (name "unconnected-(IC17A-Y2-Pad6)") (class "Default")
      (node (ref "IC17") (pin "6") (pinfunction "Y2_6") (pintype "output"))
    )
    (net (code "295") (name "unconnected-(IC17A-Y3-Pad7)") (class "Default")
      (node (ref "IC17") (pin "7") (pinfunction "Y3_7") (pintype "output"))
    )
    (net (code "296") (name "unconnected-(IC17B-Y2-Pad10)") (class "Default")
      (node (ref "IC17") (pin "10") (pinfunction "Y2_10") (pintype "output"))
    )
    (net (code "297") (name "unconnected-(IC17B-Y3-Pad9)") (class "Default")
      (node (ref "IC17") (pin "9") (pinfunction "Y3_9") (pintype "output"))
    )
    (net (code "298") (name "unconnected-(IC20B-Y4-Pad3)") (class "Default")
      (node (ref "IC20") (pin "3") (pinfunction "Y4_3") (pintype "tri_state"))
    )
    (net (code "299") (name "unconnected-(IC21B-Y0-Pad12)") (class "Default")
      (node (ref "IC21") (pin "12") (pinfunction "Y0_12") (pintype "output"))
    )
    (net (code "300") (name "unconnected-(IC21B-Y1-Pad11)") (class "Default")
      (node (ref "IC21") (pin "11") (pinfunction "Y1_11") (pintype "output"))
    )
    (net (code "301") (name "unconnected-(IC21B-Y2-Pad10)") (class "Default")
      (node (ref "IC21") (pin "10") (pinfunction "Y2_10") (pintype "output"))
    )
    (net (code "302") (name "unconnected-(IC25A-Y3-Pad12)") (class "Default")
      (node (ref "IC25") (pin "12") (pinfunction "Y3_12") (pintype "output"))
    )
    (net (code "303") (name "unconnected-(IC25A-Y5-Pad10)") (class "Default")
      (node (ref "IC25") (pin "10") (pinfunction "Y5_10") (pintype "output"))
    )
    (net (code "304") (name "unconnected-(IC25A-Y6-Pad9)") (class "Default")
      (node (ref "IC25") (pin "9") (pinfunction "Y6_9") (pintype "output"))
    )
    (net (code "305") (name "unconnected-(IC25A-Y7-Pad7)") (class "Default")
      (node (ref "IC25") (pin "7") (pinfunction "Y7_7") (pintype "output"))
    )
    (net (code "306") (name "unconnected-(IC29A-Y3-Pad12)") (class "Default")
      (node (ref "IC29") (pin "12") (pinfunction "Y3_12") (pintype "output"))
    )
    (net (code "307") (name "unconnected-(IC29A-Y5-Pad10)") (class "Default")
      (node (ref "IC29") (pin "10") (pinfunction "Y5_10") (pintype "output"))
    )
    (net (code "308") (name "unconnected-(IC29A-Y6-Pad9)") (class "Default")
      (node (ref "IC29") (pin "9") (pinfunction "Y6_9") (pintype "output"))
    )
    (net (code "309") (name "unconnected-(IC29A-Y7-Pad7)") (class "Default")
      (node (ref "IC29") (pin "7") (pinfunction "Y7_7") (pintype "output"))
    )
    (net (code "310") (name "unconnected-(IC32A-Y3-Pad12)") (class "Default")
      (node (ref "IC32") (pin "12") (pinfunction "Y3_12") (pintype "output"))
    )
    (net (code "311") (name "unconnected-(IC32A-Y5-Pad10)") (class "Default")
      (node (ref "IC32") (pin "10") (pinfunction "Y5_10") (pintype "output"))
    )
    (net (code "312") (name "unconnected-(IC32A-Y6-Pad9)") (class "Default")
      (node (ref "IC32") (pin "9") (pinfunction "Y6_9") (pintype "output"))
    )
    (net (code "313") (name "unconnected-(IC32A-Y7-Pad7)") (class "Default")
      (node (ref "IC32") (pin "7") (pinfunction "Y7_7") (pintype "output"))
    )
    (net (code "314") (name "unconnected-(IC35B-Y2-Pad7)") (class "Default")
      (node (ref "IC35") (pin "7") (pinfunction "Y2_7") (pintype "tri_state"))
    )
    (net (code "315") (name "unconnected-(IC35B-Y3-Pad5)") (class "Default")
      (node (ref "IC35") (pin "5") (pinfunction "Y3_5") (pintype "tri_state"))
    )
    (net (code "316") (name "unconnected-(IC35B-Y4-Pad3)") (class "Default")
      (node (ref "IC35") (pin "3") (pinfunction "Y4_3") (pintype "tri_state"))
    )
    (net (code "317") (name "unconnected-(IC41A-Y1-Pad5)") (class "Default")
      (node (ref "IC41") (pin "5") (pinfunction "Y1_5") (pintype "output"))
    )
    (net (code "318") (name "unconnected-(IC41A-Y2-Pad6)") (class "Default")
      (node (ref "IC41") (pin "6") (pinfunction "Y2_6") (pintype "output"))
    )
    (net (code "319") (name "unconnected-(IC41B-Y1-Pad11)") (class "Default")
      (node (ref "IC41") (pin "11") (pinfunction "Y1_11") (pintype "output"))
    )
    (net (code "320") (name "unconnected-(IC41B-Y2-Pad10)") (class "Default")
      (node (ref "IC41") (pin "10") (pinfunction "Y2_10") (pintype "output"))
    )
    (net (code "321") (name "unconnected-(INTENBA-BO-Pad13)") (class "Default")
      (node (ref "INTENB") (pin "13") (pinfunction "BO_13") (pintype "output"))
    )
    (net (code "322") (name "unconnected-(INTENBA-CO-Pad12)") (class "Default")
      (node (ref "INTENB") (pin "12") (pinfunction "CO_12") (pintype "output"))
    )
    (net (code "323") (name "unconnected-(INTENBA-QD-Pad7)") (class "Default")
      (node (ref "INTENB") (pin "7") (pinfunction "QD_7") (pintype "output"))
    )
    (net (code "324") (name "~{3CYC}") (class "Default")
      (node (ref "C35L") (pin "28") (pinfunction "28_28") (pintype "passive"))
      (node (ref "J2") (pin "1") (pinfunction "1_1") (pintype "passive"))
    )
    (net (code "325") (name "~{601}") (class "Default")
      (node (ref "IC11") (pin "13") (pinfunction "CLR_13") (pintype "input"))
      (node (ref "IC18") (pin "4") (pinfunction "I0_4") (pintype "input"))
      (node (ref "IC18") (pin "5") (pinfunction "I1_5") (pintype "input"))
      (node (ref "IC23") (pin "1") (pinfunction "CLR_1") (pintype "input"))
      (node (ref "IC32") (pin "15") (pinfunction "Y0_15") (pintype "output"))
      (node (ref "IC9") (pin "1") (pinfunction "CLR_1") (pintype "input"))
      (node (ref "IC9") (pin "13") (pinfunction "CLR_13") (pintype "input"))
    )
    (net (code "326") (name "~{602}") (class "Default")
      (node (ref "IC10") (pin "1") (pinfunction "CLR_1") (pintype "input"))
      (node (ref "IC18") (pin "1") (pinfunction "I0_1") (pintype "input"))
      (node (ref "IC18") (pin "12") (pinfunction "I0_12") (pintype "input"))
      (node (ref "IC29") (pin "15") (pinfunction "Y0_15") (pintype "output"))
    )
    (net (code "327") (name "~{604}") (class "Default")
      (node (ref "IC10") (pin "4") (pinfunction "PRE_4") (pintype "input"))
      (node (ref "IC18") (pin "13") (pinfunction "I1_13") (pintype "input"))
      (node (ref "IC18") (pin "2") (pinfunction "I1_2") (pintype "input"))
      (node (ref "IC25") (pin "15") (pinfunction "Y0_15") (pintype "output"))
    )
    (net (code "328") (name "~{611}") (class "Default")
      (node (ref "FIELD") (pin "14") (pinfunction "CLR_14") (pintype "input"))
      (node (ref "IC32") (pin "14") (pinfunction "Y1_14") (pintype "output"))
      (node (ref "INTENB") (pin "14") (pinfunction "CLR_14") (pintype "input"))
    )
    (net (code "329") (name "~{612}") (class "Default")
      (node (ref "IC19") (pin "5") (pinfunction "I_5") (pintype "input"))
      (node (ref "IC29") (pin "14") (pinfunction "Y1_14") (pintype "output"))
    )
    (net (code "330") (name "~{614}") (class "Default")
      (node (ref "IC17") (pin "13") (pinfunction "B_13") (pintype "input"))
      (node (ref "IC22") (pin "3") (pinfunction "I_3") (pintype "input"))
      (node (ref "IC25") (pin "14") (pinfunction "Y1_14") (pintype "output"))
    )
    (net (code "331") (name "~{621}") (class "Default")
      (node (ref "IC32") (pin "13") (pinfunction "Y2_13") (pintype "output"))
      (node (ref "IC7") (pin "3") (pinfunction "B_3") (pintype "input"))
    )
    (net (code "332") (name "~{622}") (class "Default")
      (node (ref "IC29") (pin "13") (pinfunction "Y2_13") (pintype "output"))
      (node (ref "IC7") (pin "13") (pinfunction "B_13") (pintype "input"))
    )
    (net (code "333") (name "~{624}") (class "Default")
      (node (ref "IC22") (pin "13") (pinfunction "I_13") (pintype "input"))
      (node (ref "IC24") (pin "1") (pinfunction "G_1") (pintype "input"))
      (node (ref "IC25") (pin "13") (pinfunction "Y2_13") (pintype "output"))
      (node (ref "IC31") (pin "1") (pinfunction "G_1") (pintype "input"))
      (node (ref "IC38") (pin "1") (pinfunction "G_1") (pintype "input"))
    )
    (net (code "334") (name "~{641}") (class "Default")
      (node (ref "IC16") (pin "13") (pinfunction "B_13") (pintype "input"))
      (node (ref "IC32") (pin "11") (pinfunction "Y4_11") (pintype "output"))
    )
    (net (code "335") (name "~{642}") (class "Default")
      (node (ref "DAR4-7") (pin "11") (pinfunction "LD_11") (pintype "input"))
      (node (ref "DAR8-11") (pin "11") (pinfunction "LD_11") (pintype "input"))
      (node (ref "IC29") (pin "11") (pinfunction "Y4_11") (pintype "output"))
    )
    (net (code "336") (name "~{644}") (class "Default")
      (node (ref "IC16") (pin "3") (pinfunction "B_3") (pintype "input"))
      (node (ref "IC25") (pin "11") (pinfunction "Y4_11") (pintype "output"))
    )
    (net (code "337") (name "~{645}") (class "Default")
      (node (ref "IC16") (pin "4") (pinfunction "Y0_4") (pintype "output"))
      (node (ref "IC24") (pin "19") (pinfunction "G_19") (pintype "input"))
      (node (ref "IC31") (pin "19") (pinfunction "G_19") (pintype "input"))
      (node (ref "IC38") (pin "19") (pinfunction "G_19") (pintype "input"))
    )
    (net (code "338") (name "~{ACB00}") (class "Default")
      (node (ref "D34L") (pin "2") (pinfunction "2_2") (pintype "passive"))
      (node (ref "IC37") (pin "12") (pinfunction "Y4_12") (pintype "tri_state"))
      (node (ref "IC38") (pin "12") (pinfunction "Y4_12") (pintype "tri_state"))
      (node (ref "IC38") (pin "3") (pinfunction "Y4_3") (pintype "tri_state"))
    )
    (net (code "339") (name "~{ACB01}") (class "Default")
      (node (ref "D34L") (pin "4") (pinfunction "4_4") (pintype "passive"))
      (node (ref "IC37") (pin "14") (pinfunction "Y3_14") (pintype "tri_state"))
      (node (ref "IC38") (pin "14") (pinfunction "Y3_14") (pintype "tri_state"))
      (node (ref "IC38") (pin "5") (pinfunction "Y3_5") (pintype "tri_state"))
    )
    (net (code "340") (name "~{ACB02}") (class "Default")
      (node (ref "D34L") (pin "6") (pinfunction "6_6") (pintype "passive"))
      (node (ref "IC37") (pin "16") (pinfunction "Y2_16") (pintype "tri_state"))
      (node (ref "IC38") (pin "16") (pinfunction "Y2_16") (pintype "tri_state"))
      (node (ref "IC38") (pin "7") (pinfunction "Y2_7") (pintype "tri_state"))
    )
    (net (code "341") (name "~{ACB03}") (class "Default")
      (node (ref "D34L") (pin "8") (pinfunction "8_8") (pintype "passive"))
      (node (ref "IC37") (pin "18") (pinfunction "Y1_18") (pintype "tri_state"))
      (node (ref "IC38") (pin "18") (pinfunction "Y1_18") (pintype "tri_state"))
      (node (ref "IC38") (pin "9") (pinfunction "Y1_9") (pintype "tri_state"))
    )
    (net (code "342") (name "~{ACB04}") (class "Default")
      (node (ref "D34L") (pin "10") (pinfunction "10_10") (pintype "passive"))
      (node (ref "IC30") (pin "3") (pinfunction "Y4_3") (pintype "tri_state"))
      (node (ref "IC31") (pin "12") (pinfunction "Y4_12") (pintype "tri_state"))
      (node (ref "IC31") (pin "3") (pinfunction "Y4_3") (pintype "tri_state"))
    )
    (net (code "343") (name "~{ACB05}") (class "Default")
      (node (ref "D34L") (pin "12") (pinfunction "12_12") (pintype "passive"))
      (node (ref "IC30") (pin "5") (pinfunction "Y3_5") (pintype "tri_state"))
      (node (ref "IC31") (pin "14") (pinfunction "Y3_14") (pintype "tri_state"))
      (node (ref "IC31") (pin "5") (pinfunction "Y3_5") (pintype "tri_state"))
    )
    (net (code "344") (name "~{ACB06}") (class "Default")
      (node (ref "D34L") (pin "14") (pinfunction "14_14") (pintype "passive"))
      (node (ref "IC30") (pin "7") (pinfunction "Y2_7") (pintype "tri_state"))
      (node (ref "IC31") (pin "16") (pinfunction "Y2_16") (pintype "tri_state"))
      (node (ref "IC31") (pin "7") (pinfunction "Y2_7") (pintype "tri_state"))
    )
    (net (code "345") (name "~{ACB07}") (class "Default")
      (node (ref "D34L") (pin "16") (pinfunction "16_16") (pintype "passive"))
      (node (ref "IC30") (pin "9") (pinfunction "Y1_9") (pintype "tri_state"))
      (node (ref "IC31") (pin "18") (pinfunction "Y1_18") (pintype "tri_state"))
      (node (ref "IC31") (pin "9") (pinfunction "Y1_9") (pintype "tri_state"))
    )
    (net (code "346") (name "~{ACB08}") (class "Default")
      (node (ref "D34L") (pin "18") (pinfunction "18_18") (pintype "passive"))
      (node (ref "IC24") (pin "12") (pinfunction "Y4_12") (pintype "tri_state"))
      (node (ref "IC24") (pin "3") (pinfunction "Y4_3") (pintype "tri_state"))
      (node (ref "IC30") (pin "12") (pinfunction "Y4_12") (pintype "tri_state"))
    )
    (net (code "347") (name "~{ACB09}") (class "Default")
      (node (ref "D34L") (pin "22") (pinfunction "22_22") (pintype "passive"))
      (node (ref "IC24") (pin "14") (pinfunction "Y3_14") (pintype "tri_state"))
      (node (ref "IC24") (pin "5") (pinfunction "Y3_5") (pintype "tri_state"))
      (node (ref "IC30") (pin "14") (pinfunction "Y3_14") (pintype "tri_state"))
    )
    (net (code "348") (name "~{ACB10}") (class "Default")
      (node (ref "D34L") (pin "24") (pinfunction "24_24") (pintype "passive"))
      (node (ref "IC24") (pin "16") (pinfunction "Y2_16") (pintype "tri_state"))
      (node (ref "IC24") (pin "7") (pinfunction "Y2_7") (pintype "tri_state"))
      (node (ref "IC30") (pin "16") (pinfunction "Y2_16") (pintype "tri_state"))
    )
    (net (code "349") (name "~{ACB11}") (class "Default")
      (node (ref "D34L") (pin "26") (pinfunction "26_26") (pintype "passive"))
      (node (ref "IC24") (pin "18") (pinfunction "Y1_18") (pintype "tri_state"))
      (node (ref "IC24") (pin "9") (pinfunction "Y1_9") (pintype "tri_state"))
      (node (ref "IC30") (pin "18") (pinfunction "Y1_18") (pintype "tri_state"))
    )
    (net (code "350") (name "~{ACCLEAR}") (class "Default")
      (node (ref "D34L") (pin "32") (pinfunction "32_32") (pintype "passive"))
      (node (ref "IC22") (pin "12") (pinfunction "O_12") (pintype "open_collector"))
      (node (ref "IC22") (pin "2") (pinfunction "O_2") (pintype "open_collector"))
      (node (ref "IC22") (pin "4") (pinfunction "O_4") (pintype "open_collector"))
    )
    (net (code "351") (name "~{BADDAC}") (class "Default")
      (node (ref "C36L") (pin "34") (pinfunction "34_34") (pintype "passive"))
      (node (ref "IC11") (pin "1") (pinfunction "CLR_1") (pintype "input"))
    )
    (net (code "352") (name "~{BBREAK}") (class "Default")
      (node (ref "C36L") (pin "32") (pinfunction "32_32") (pintype "passive"))
      (node (ref "DMA8-11") (pin "5") (pinfunction "UP_5") (pintype "input"))
      (node (ref "IC20") (pin "19") (pinfunction "G_19") (pintype "input"))
      (node (ref "IC21") (pin "15") (pinfunction "G_15") (pintype "input"))
      (node (ref "IC41") (pin "1") (pinfunction "G_1") (pintype "input"))
      (node (ref "IC41") (pin "15") (pinfunction "G_15") (pintype "input"))
      (node (ref "IC6") (pin "1") (pinfunction "G_1") (pintype "input"))
    )
    (net (code "353") (name "~{BMB03}") (class "Default")
      (node (ref "D35L") (pin "8") (pinfunction "8_8") (pintype "passive"))
    )
    (net (code "354") (name "~{BMB04}") (class "Default")
      (node (ref "D35L") (pin "12") (pinfunction "12_12") (pintype "passive"))
    )
    (net (code "355") (name "~{BMB05}") (class "Default")
      (node (ref "D35L") (pin "16") (pinfunction "16_16") (pintype "passive"))
    )
    (net (code "356") (name "~{BMB06}") (class "Default")
      (node (ref "D35L") (pin "22") (pinfunction "22_22") (pintype "passive"))
    )
    (net (code "357") (name "~{BMB07}") (class "Default")
      (node (ref "D35L") (pin "26") (pinfunction "26_26") (pintype "passive"))
    )
    (net (code "358") (name "~{BMB08}") (class "Default")
      (node (ref "D35L") (pin "30") (pinfunction "30_30") (pintype "passive"))
    )
    (net (code "359") (name "~{BRK_RQ}") (class "Default")
      (node (ref "C36L") (pin "28") (pinfunction "28_28") (pintype "passive"))
      (node (ref "IC11") (pin "6") (pinfunction "~{Q}_6") (pintype "output"))
    )
    (net (code "360") (name "~{BRUN}") (class "Default")
      (node (ref "D34L") (pin "34") (pinfunction "34_34") (pintype "passive"))
    )
    (net (code "361") (name "~{BWCO}") (class "Default")
      (node (ref "C35L") (pin "32") (pinfunction "32_32") (pintype "passive"))
      (node (ref "IC10") (pin "13") (pinfunction "CLR_13") (pintype "input"))
      (node (ref "IC11") (pin "12") (pinfunction "D_12") (pintype "input"))
      (node (ref "IC44") (pin "9") (pinfunction "I_9") (pintype "input"))
    )
    (net (code "362") (name "~{DA00}") (class "Default")
      (node (ref "C36L") (pin "2") (pinfunction "2_2") (pintype "passive"))
      (node (ref "J14") (pin "1") (pinfunction "1_1") (pintype "passive"))
    )
    (net (code "363") (name "~{DA01}") (class "Default")
      (node (ref "C36L") (pin "4") (pinfunction "4_4") (pintype "passive"))
      (node (ref "J13") (pin "1") (pinfunction "1_1") (pintype "passive"))
    )
    (net (code "364") (name "~{DA02}") (class "Default")
      (node (ref "C36L") (pin "6") (pinfunction "6_6") (pintype "passive"))
      (node (ref "J12") (pin "1") (pinfunction "1_1") (pintype "passive"))
    )
    (net (code "365") (name "~{DA03}") (class "Default")
      (node (ref "C36L") (pin "8") (pinfunction "8_8") (pintype "passive"))
      (node (ref "J11") (pin "1") (pinfunction "1_1") (pintype "passive"))
    )
    (net (code "366") (name "~{DA04}") (class "Default")
      (node (ref "C36L") (pin "10") (pinfunction "10_10") (pintype "passive"))
      (node (ref "J10") (pin "1") (pinfunction "1_1") (pintype "passive"))
    )
    (net (code "367") (name "~{DA05}") (class "Default")
      (node (ref "C36L") (pin "12") (pinfunction "12_12") (pintype "passive"))
      (node (ref "J9") (pin "1") (pinfunction "1_1") (pintype "passive"))
    )
    (net (code "368") (name "~{DA06}") (class "Default")
      (node (ref "C36L") (pin "14") (pinfunction "14_14") (pintype "passive"))
      (node (ref "J8") (pin "1") (pinfunction "1_1") (pintype "passive"))
    )
    (net (code "369") (name "~{DA07}") (class "Default")
      (node (ref "C36L") (pin "16") (pinfunction "16_16") (pintype "passive"))
      (node (ref "J7") (pin "1") (pinfunction "1_1") (pintype "passive"))
    )
    (net (code "370") (name "~{DA08}") (class "Default")
      (node (ref "C36L") (pin "18") (pinfunction "18_18") (pintype "passive"))
      (node (ref "J6") (pin "1") (pinfunction "1_1") (pintype "passive"))
    )
    (net (code "371") (name "~{DA09}") (class "Default")
      (node (ref "C36L") (pin "22") (pinfunction "22_22") (pintype "passive"))
      (node (ref "J5") (pin "1") (pinfunction "1_1") (pintype "passive"))
    )
    (net (code "372") (name "~{DA10}") (class "Default")
      (node (ref "C36L") (pin "24") (pinfunction "24_24") (pintype "passive"))
      (node (ref "J4") (pin "1") (pinfunction "1_1") (pintype "passive"))
    )
    (net (code "373") (name "~{DA11}") (class "Default")
      (node (ref "C36L") (pin "26") (pinfunction "26_26") (pintype "passive"))
      (node (ref "J3") (pin "1") (pinfunction "1_1") (pintype "passive"))
    )
    (net (code "374") (name "~{DATA00}") (class "Default")
      (node (ref "C35L") (pin "2") (pinfunction "2_2") (pintype "passive"))
      (node (ref "IC34") (pin "12") (pinfunction "Y4_12") (pintype "tri_state"))
    )
    (net (code "375") (name "~{DATA01}") (class "Default")
      (node (ref "C35L") (pin "4") (pinfunction "4_4") (pintype "passive"))
      (node (ref "IC34") (pin "14") (pinfunction "Y3_14") (pintype "tri_state"))
    )
    (net (code "376") (name "~{DATA02}") (class "Default")
      (node (ref "C35L") (pin "6") (pinfunction "6_6") (pintype "passive"))
      (node (ref "IC34") (pin "16") (pinfunction "Y2_16") (pintype "tri_state"))
    )
    (net (code "377") (name "~{DATA03}") (class "Default")
      (node (ref "C35L") (pin "8") (pinfunction "8_8") (pintype "passive"))
      (node (ref "IC34") (pin "18") (pinfunction "Y1_18") (pintype "tri_state"))
    )
    (net (code "378") (name "~{DATA04}") (class "Default")
      (node (ref "C35L") (pin "10") (pinfunction "10_10") (pintype "passive"))
      (node (ref "IC26") (pin "3") (pinfunction "Y4_3") (pintype "tri_state"))
    )
    (net (code "379") (name "~{DATA05}") (class "Default")
      (node (ref "C35L") (pin "12") (pinfunction "12_12") (pintype "passive"))
      (node (ref "IC26") (pin "5") (pinfunction "Y3_5") (pintype "tri_state"))
    )
    (net (code "380") (name "~{DATA06}") (class "Default")
      (node (ref "C35L") (pin "14") (pinfunction "14_14") (pintype "passive"))
      (node (ref "IC26") (pin "7") (pinfunction "Y2_7") (pintype "tri_state"))
    )
    (net (code "381") (name "~{DATA07}") (class "Default")
      (node (ref "C35L") (pin "16") (pinfunction "16_16") (pintype "passive"))
      (node (ref "IC26") (pin "9") (pinfunction "Y1_9") (pintype "tri_state"))
    )
    (net (code "382") (name "~{DATA08}") (class "Default")
      (node (ref "C35L") (pin "18") (pinfunction "18_18") (pintype "passive"))
      (node (ref "IC26") (pin "12") (pinfunction "Y4_12") (pintype "tri_state"))
    )
    (net (code "383") (name "~{DATA09}") (class "Default")
      (node (ref "C35L") (pin "22") (pinfunction "22_22") (pintype "passive"))
      (node (ref "IC26") (pin "14") (pinfunction "Y3_14") (pintype "tri_state"))
    )
    (net (code "384") (name "~{DATA10}") (class "Default")
      (node (ref "C35L") (pin "24") (pinfunction "24_24") (pintype "passive"))
      (node (ref "IC26") (pin "16") (pinfunction "Y2_16") (pintype "tri_state"))
    )
    (net (code "385") (name "~{DATA11}") (class "Default")
      (node (ref "C35L") (pin "26") (pinfunction "26_26") (pintype "passive"))
      (node (ref "IC26") (pin "18") (pinfunction "Y1_18") (pintype "tri_state"))
    )
    (net (code "386") (name "~{DCXA}") (class "Default")
      (node (ref "IC16") (pin "12") (pinfunction "Y0_12") (pintype "output"))
      (node (ref "IC18") (pin "10") (pinfunction "I1_10") (pintype "input"))
      (node (ref "IC18") (pin "9") (pinfunction "I0_9") (pintype "input"))
    )
    (net (code "387") (name "~{DIMA}") (class "Default")
      (node (ref "IC17") (pin "11") (pinfunction "Y1_11") (pintype "output"))
      (node (ref "IC30") (pin "1") (pinfunction "G_1") (pintype "input"))
      (node (ref "IC30") (pin "19") (pinfunction "G_19") (pintype "input"))
      (node (ref "IC37") (pin "1") (pinfunction "G_1") (pintype "input"))
    )
    (net (code "388") (name "~{DIML}") (class "Default")
      (node (ref "FIELD") (pin "11") (pinfunction "LD_11") (pintype "input"))
      (node (ref "IC17") (pin "12") (pinfunction "Y0_12") (pintype "output"))
      (node (ref "INTENB") (pin "11") (pinfunction "LD_11") (pintype "input"))
    )
    (net (code "389") (name "~{DMA-IN}") (class "Default")
      (node (ref "IC13") (pin "4") (pinfunction "OI_4") (pintype "input"))
      (node (ref "IC26") (pin "1") (pinfunction "G_1") (pintype "input"))
      (node (ref "IC26") (pin "19") (pinfunction "G_19") (pintype "input"))
      (node (ref "IC34") (pin "1") (pinfunction "G_1") (pintype "input"))
      (node (ref "IC41") (pin "12") (pinfunction "Y0_12") (pintype "output"))
    )
    (net (code "390") (name "~{DMA-OUT}") (class "Default")
      (node (ref "IC28") (pin "1") (pinfunction "G_1") (pintype "input"))
      (node (ref "IC28") (pin "19") (pinfunction "G_19") (pintype "input"))
      (node (ref "IC35") (pin "1") (pinfunction "G_1") (pintype "input"))
      (node (ref "IC35") (pin "19") (pinfunction "G_19") (pintype "input"))
      (node (ref "IC41") (pin "9") (pinfunction "Y3_9") (pintype "output"))
    )
    (net (code "391") (name "~{DRV01}") (class "Default")
      (node (ref "IC41") (pin "4") (pinfunction "Y0_4") (pintype "output"))
      (node (ref "RS08") (pin "38") (pinfunction "38_38") (pintype "passive"))
    )
    (net (code "392") (name "~{DRV23}") (class "Default")
      (node (ref "IC41") (pin "7") (pinfunction "Y3_7") (pintype "output"))
      (node (ref "RS08") (pin "22") (pinfunction "22_22") (pintype "passive"))
    )
    (net (code "393") (name "~{DRVOK}") (class "Default")
      (node (ref "IC21") (pin "13") (pinfunction "B_13") (pintype "input"))
      (node (ref "IC21") (pin "14") (pinfunction "A_14") (pintype "input"))
      (node (ref "R2") (pin "1") (pinfunction "1_1") (pintype "passive"))
      (node (ref "RS08") (pin "40") (pinfunction "40_40") (pintype "passive"))
    )
    (net (code "394") (name "~{EXAD0}") (class "Default")
      (node (ref "C35L") (pin "34") (pinfunction "34_34") (pintype "passive"))
      (node (ref "IC20") (pin "9") (pinfunction "Y1_9") (pintype "tri_state"))
    )
    (net (code "395") (name "~{EXAD1}") (class "Default")
      (node (ref "C35L") (pin "36") (pinfunction "36_36") (pintype "passive"))
      (node (ref "IC20") (pin "7") (pinfunction "Y2_7") (pintype "tri_state"))
    )
    (net (code "396") (name "~{EXAD2}") (class "Default")
      (node (ref "C35L") (pin "38") (pinfunction "38_38") (pintype "passive"))
      (node (ref "IC20") (pin "5") (pinfunction "Y3_5") (pintype "tri_state"))
    )
    (net (code "397") (name "~{INT_RQ}") (class "Default")
      (node (ref "D34L") (pin "30") (pinfunction "30_30") (pintype "passive"))
      (node (ref "IC40") (pin "3") (pinfunction "O_3") (pintype "open_collector"))
      (node (ref "IC40") (pin "6") (pinfunction "O_6") (pintype "open_collector"))
      (node (ref "IC40") (pin "8") (pinfunction "O_8") (pintype "open_collector"))
    )
    (net (code "398") (name "~{IOS}") (class "Default")
      (node (ref "D34L") (pin "28") (pinfunction "28_28") (pintype "passive"))
      (node (ref "IC22") (pin "10") (pinfunction "O_10") (pintype "open_collector"))
    )
    (net (code "399") (name "~{MEM_INC}") (class "Default")
      (node (ref "C36L") (pin "36") (pinfunction "36_36") (pintype "passive"))
    )
    (net (code "400") (name "~{MYDEV}") (class "Default")
      (node (ref "IC25") (pin "4") (pinfunction "G2A_4") (pintype "input"))
      (node (ref "IC29") (pin "4") (pinfunction "G2A_4") (pintype "input"))
      (node (ref "IC32") (pin "4") (pinfunction "G2A_4") (pintype "input"))
      (node (ref "PAD1") (pin "1") (pinfunction "P_1") (pintype "passive"))
    )
    (net (code "401") (name "~{NXD}") (class "Default")
      (node (ref "IC12") (pin "12") (pinfunction "I0_12") (pintype "input"))
      (node (ref "IC23") (pin "6") (pinfunction "~{Q}_6") (pintype "output"))
    )
    (net (code "402") (name "~{PER}") (class "Default")
      (node (ref "IC12") (pin "4") (pinfunction "I0_4") (pintype "input"))
      (node (ref "IC9") (pin "8") (pinfunction "~{Q}_8") (pintype "output"))
    )
    (net (code "403") (name "~{SETNXD}") (class "Default")
      (node (ref "IC21") (pin "9") (pinfunction "Y3_9") (pintype "output"))
      (node (ref "IC23") (pin "4") (pinfunction "PRE_4") (pintype "input"))
    )
    (net (code "404") (name "~{SETPER}") (class "Default")
      (node (ref "IC13") (pin "5") (pinfunction "EVN_5") (pintype "output"))
      (node (ref "IC9") (pin "10") (pinfunction "PRE_10") (pintype "input"))
    )
    (net (code "405") (name "~{SETWLS}") (class "Default")
      (node (ref "IC6") (pin "7") (pinfunction "Y3_7") (pintype "output"))
      (node (ref "IC9") (pin "4") (pinfunction "PRE_4") (pintype "input"))
    )
    (net (code "406") (name "~{SKIP}") (class "Default")
      (node (ref "IC17") (pin "2") (pinfunction "A_2") (pintype "input"))
      (node (ref "IC19") (pin "10") (pinfunction "O_10") (pintype "open_collector"))
      (node (ref "IC19") (pin "2") (pinfunction "O_2") (pintype "open_collector"))
      (node (ref "IC19") (pin "6") (pinfunction "O_6") (pintype "open_collector"))
      (node (ref "R1") (pin "1") (pinfunction "1_1") (pintype "passive"))
    )
    (net (code "407") (name "~{START}") (class "Default")
      (node (ref "DMA0-3") (pin "11") (pinfunction "LD_11") (pintype "input"))
      (node (ref "DMA4-7") (pin "11") (pinfunction "LD_11") (pintype "input"))
      (node (ref "DMA8-11") (pin "11") (pinfunction "LD_11") (pintype "input"))
      (node (ref "IC18") (pin "3") (pinfunction "O_3") (pintype "output"))
    )
    (net (code "408") (name "~{WE}") (class "Default")
      (node (ref "IC22") (pin "5") (pinfunction "I_5") (pintype "input"))
      (node (ref "IC6") (pin "5") (pinfunction "Y1_5") (pintype "output"))
      (node (ref "RS08") (pin "8") (pinfunction "8_8") (pintype "passive"))
    )
    (net (code "409") (name "~{WLS}") (class "Default")
      (node (ref "IC12") (pin "13") (pinfunction "I1_13") (pintype "input"))
      (node (ref "IC9") (pin "6") (pinfunction "~{Q}_6") (pintype "output"))
    )
  )
)
